# Top_Level.net
KiCad netlist of a schematic drawn in Altium Designer
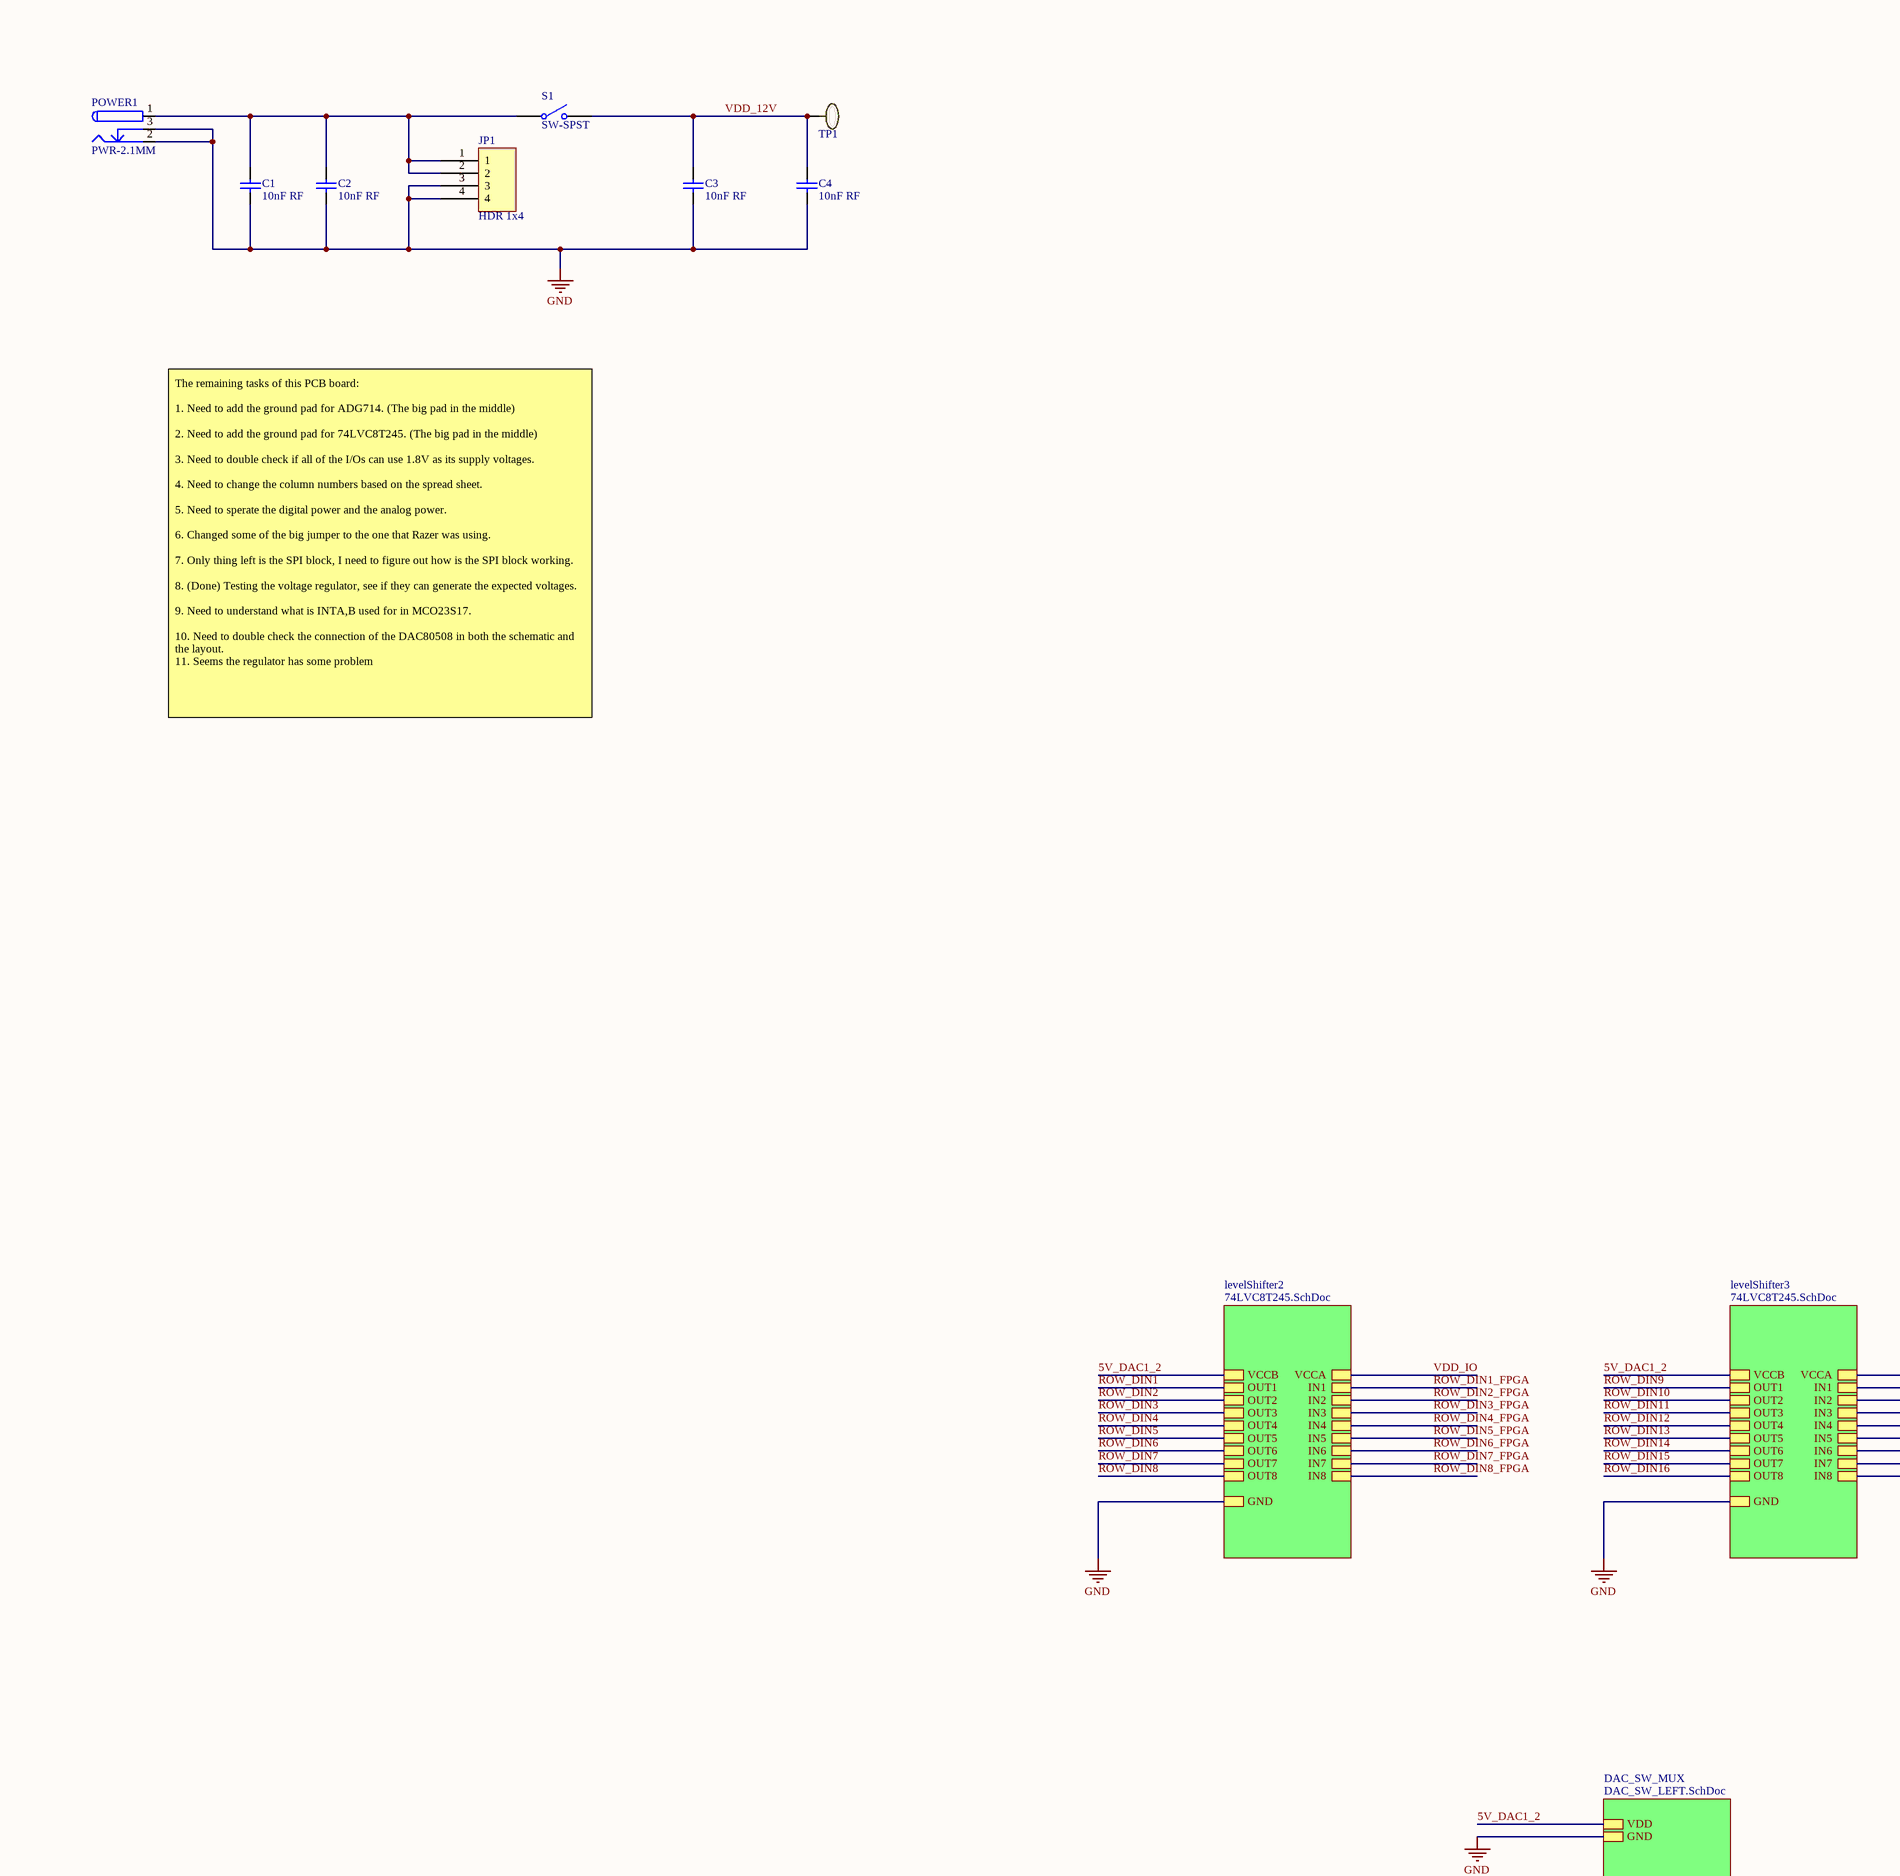
[diagram p0: Top_Level.SchDoc, top column 1 of 4]
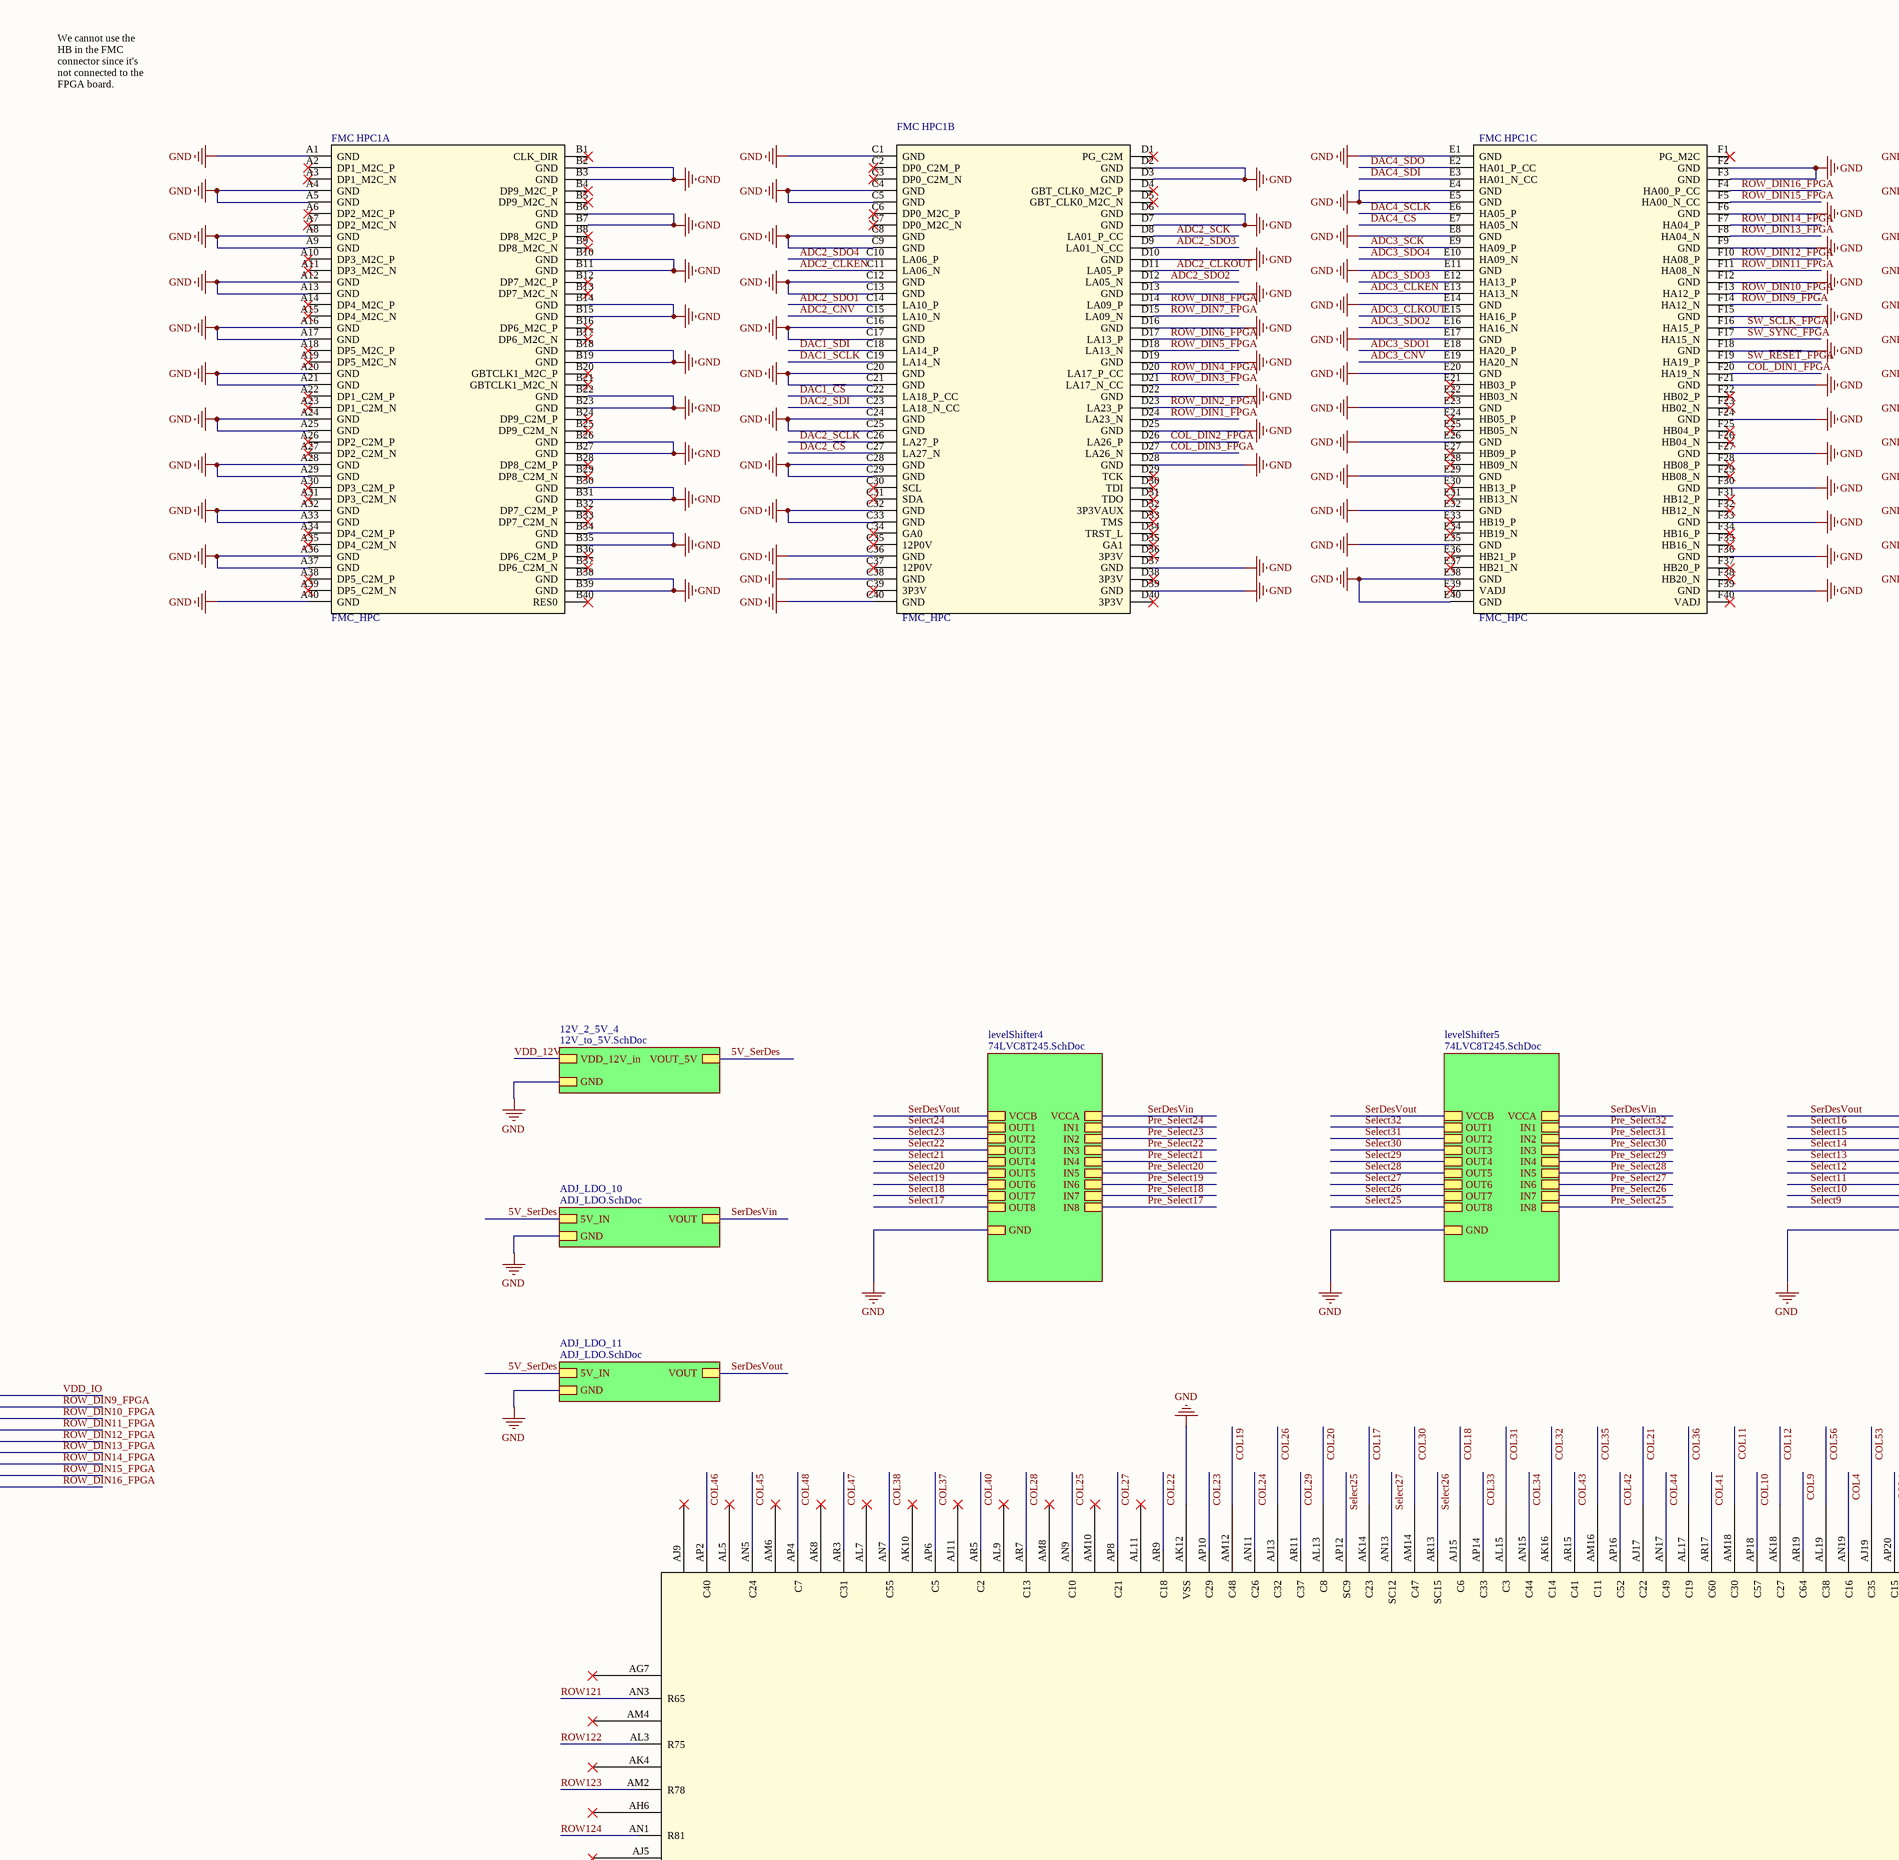
[diagram p1: Top_Level.SchDoc, top column 2 of 4]
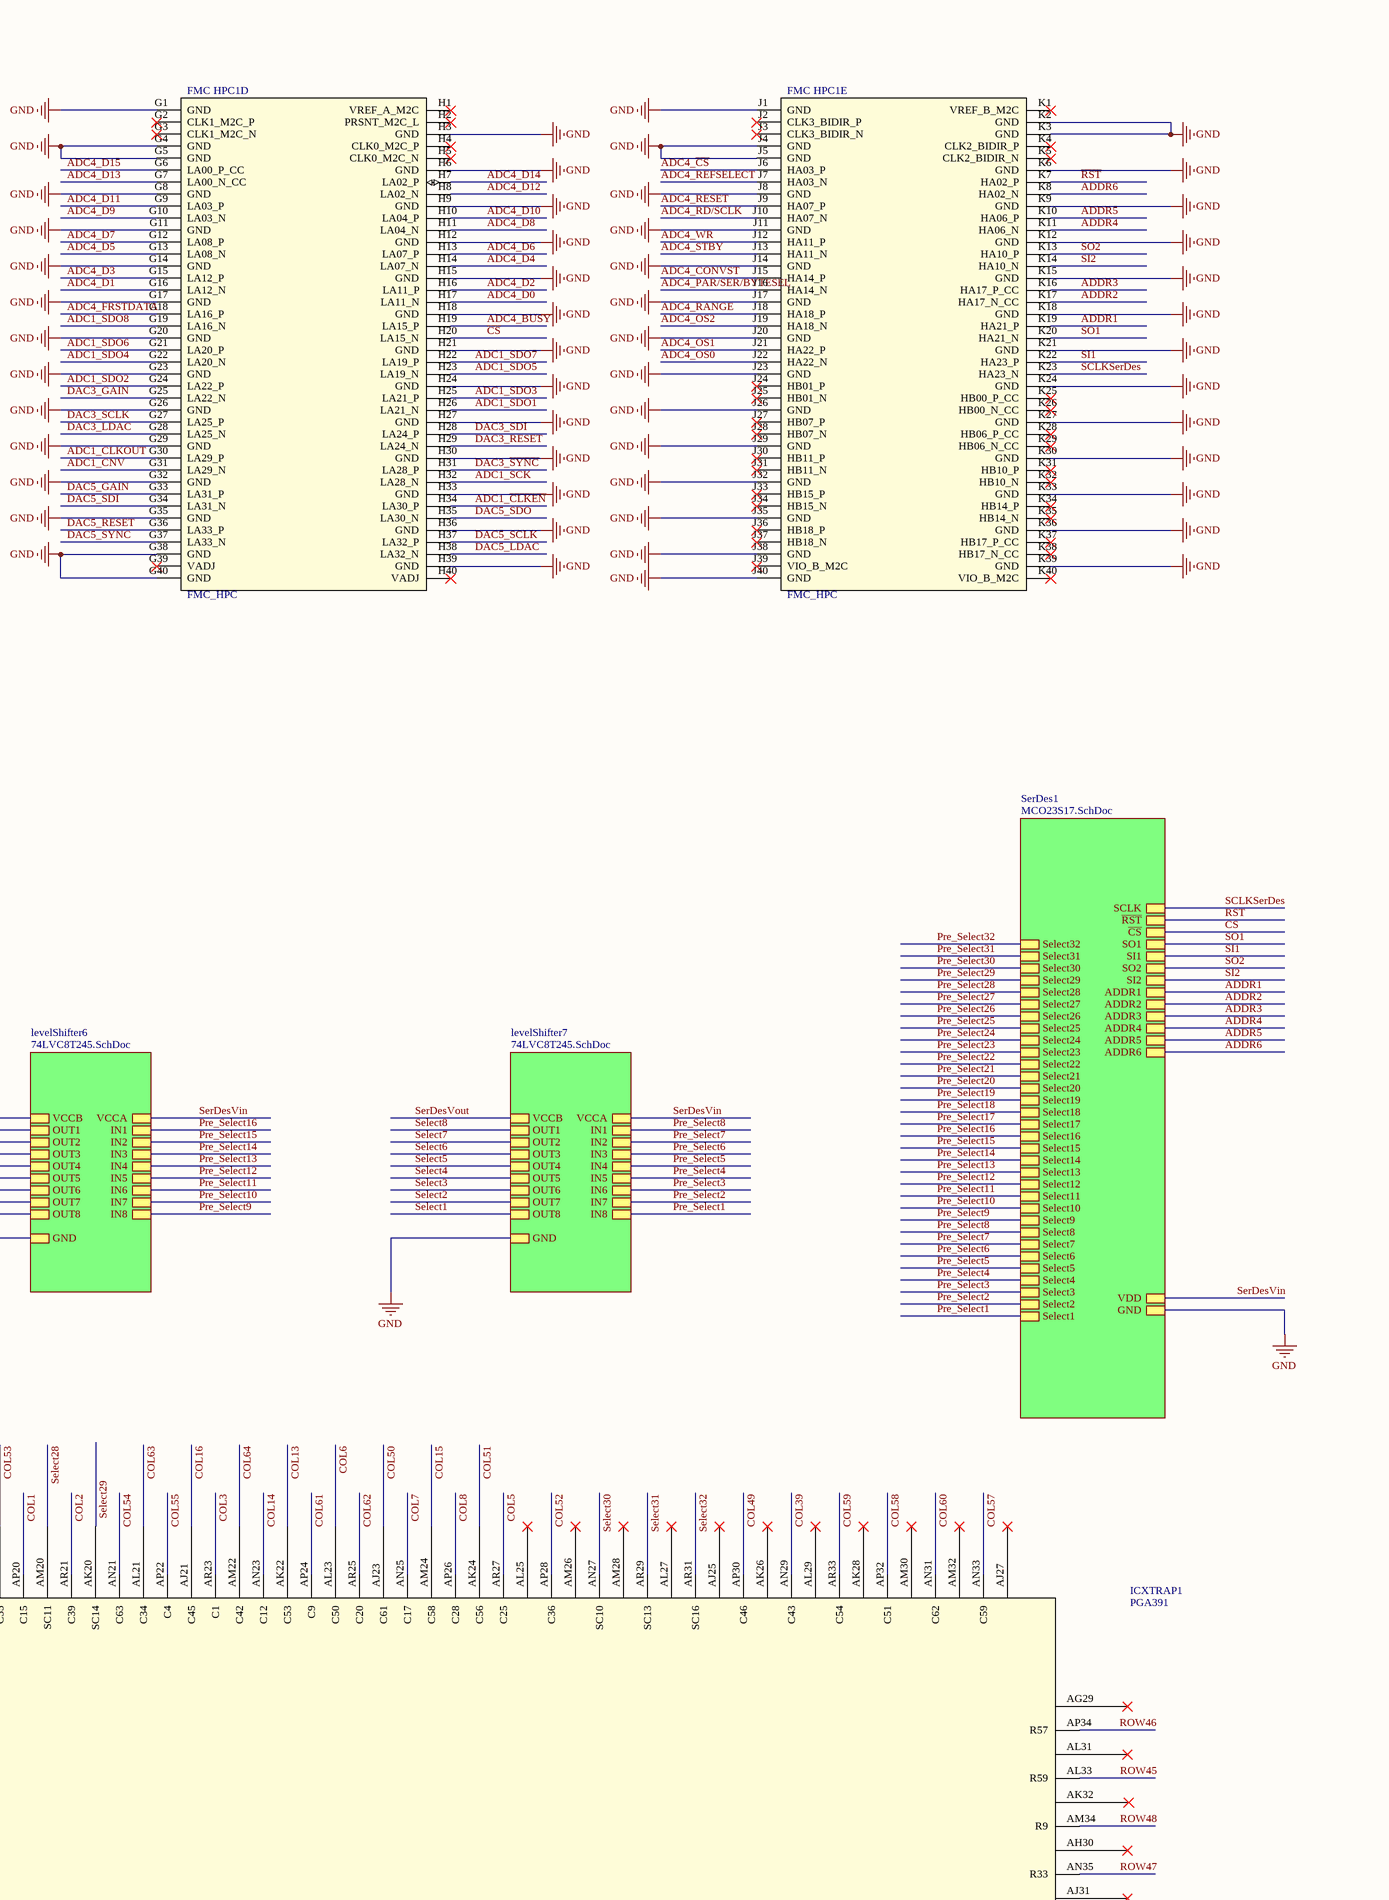
[diagram p2: Top_Level.SchDoc, top column 3 of 4]
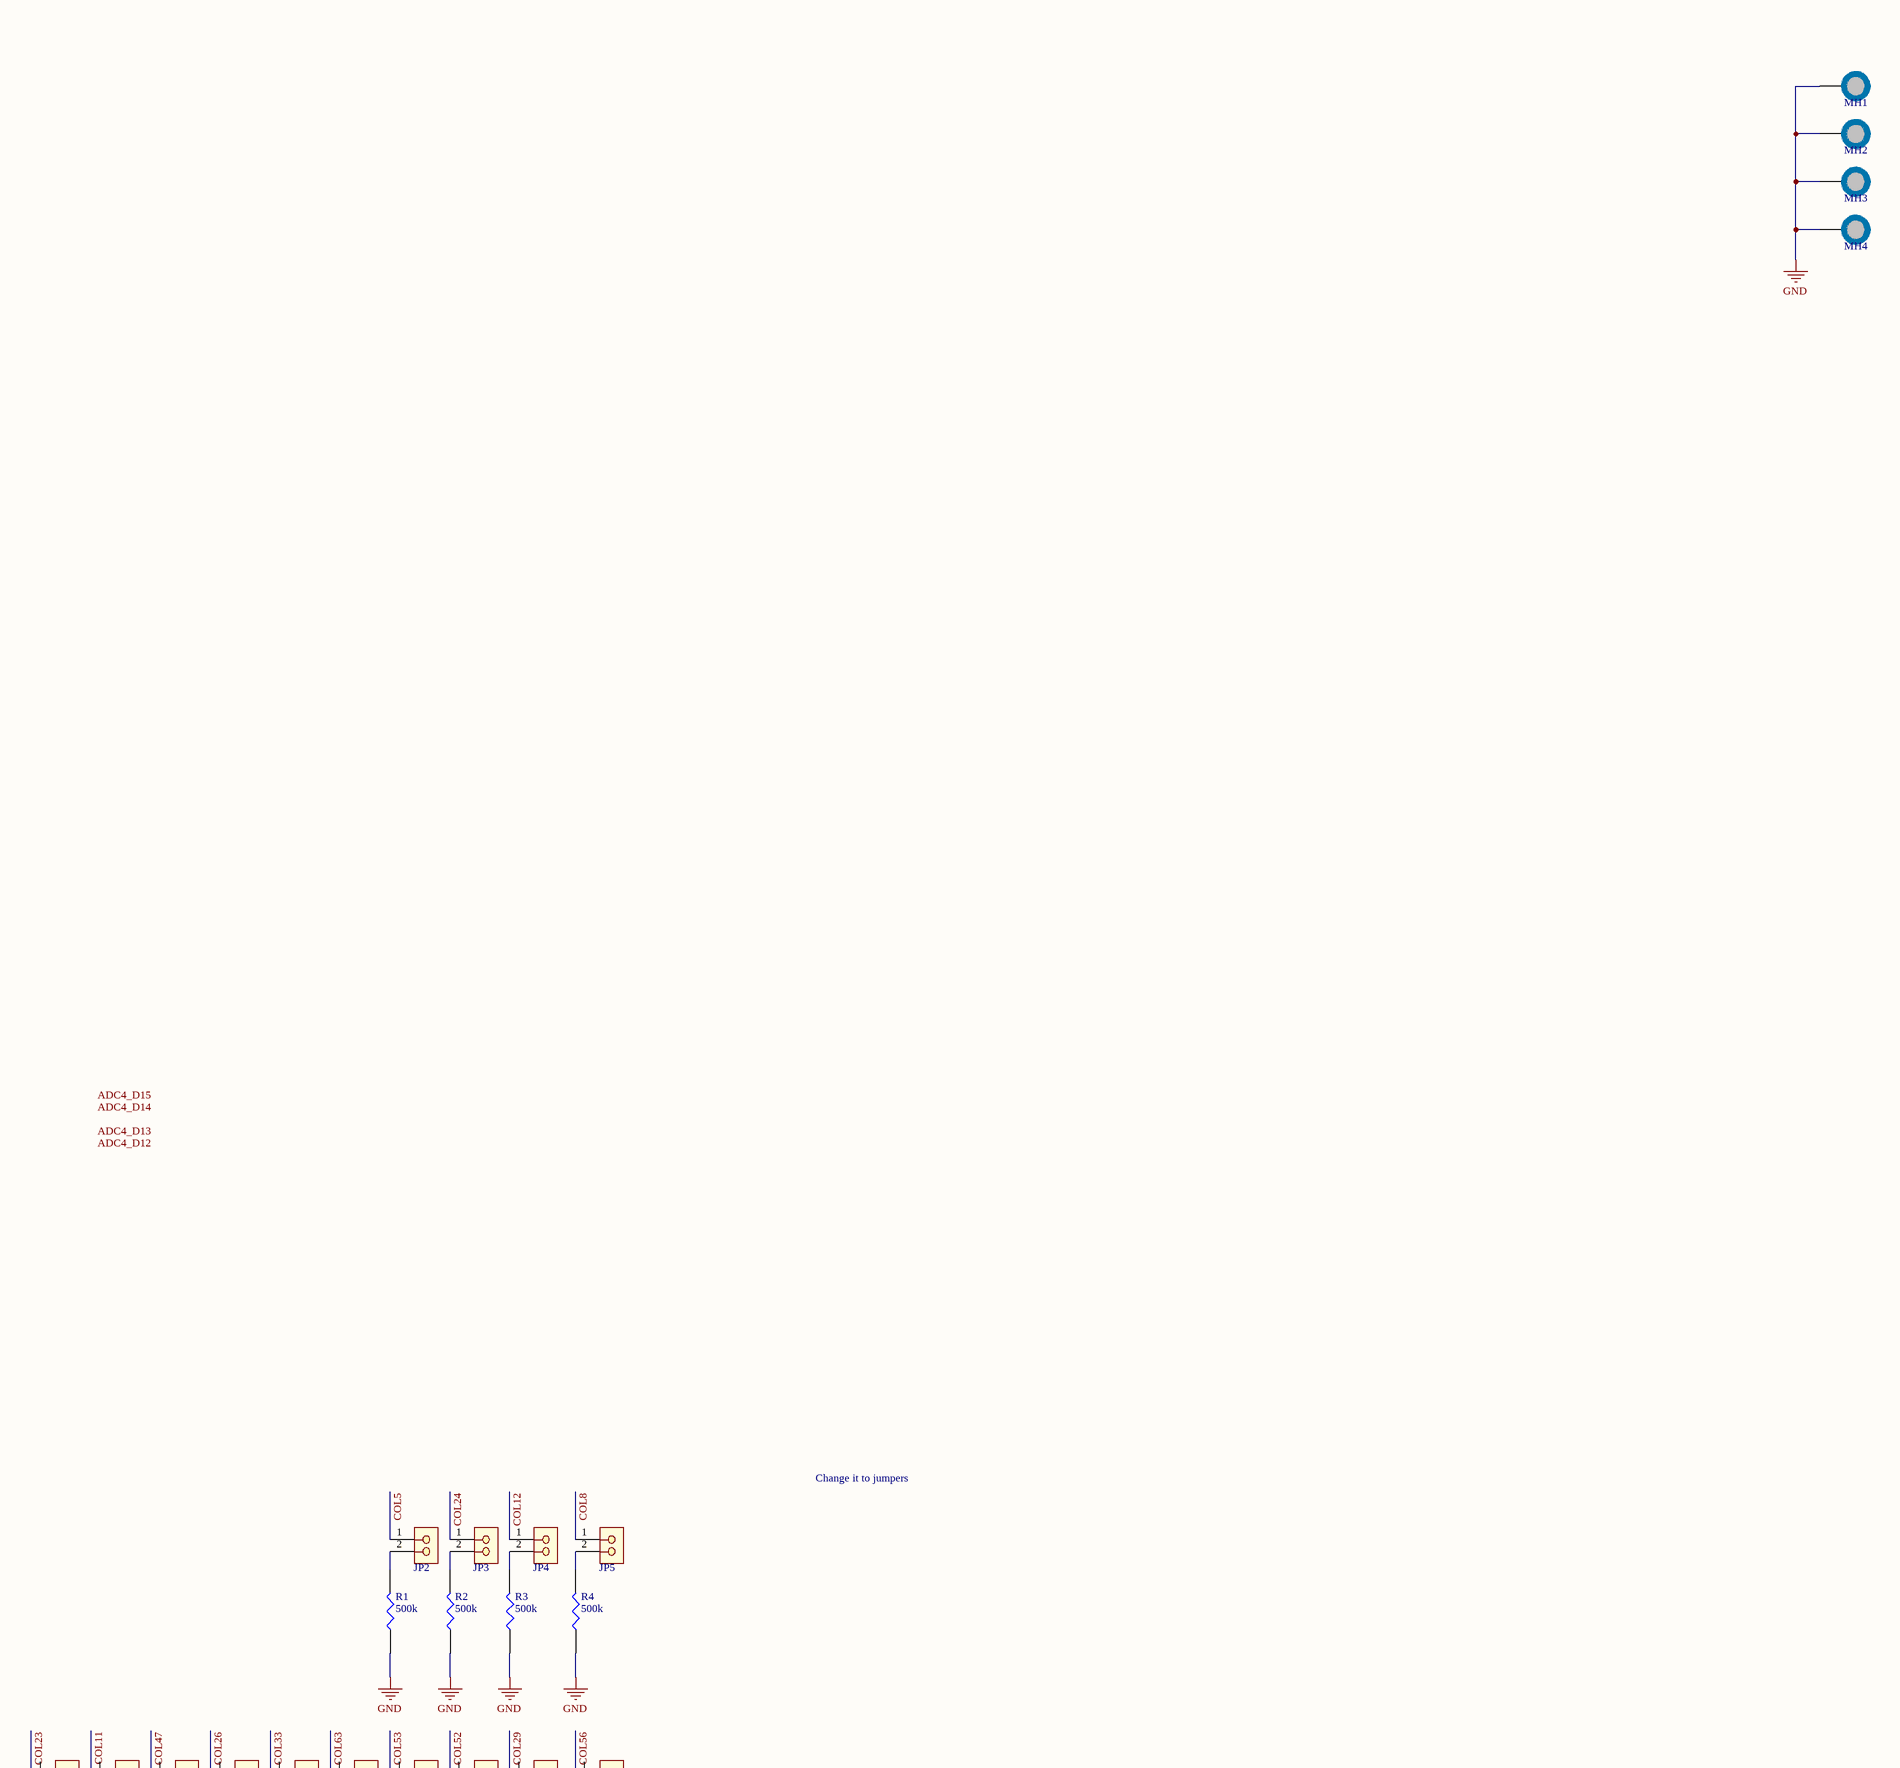
[diagram p3: Top_Level.SchDoc, top column 4 of 4]
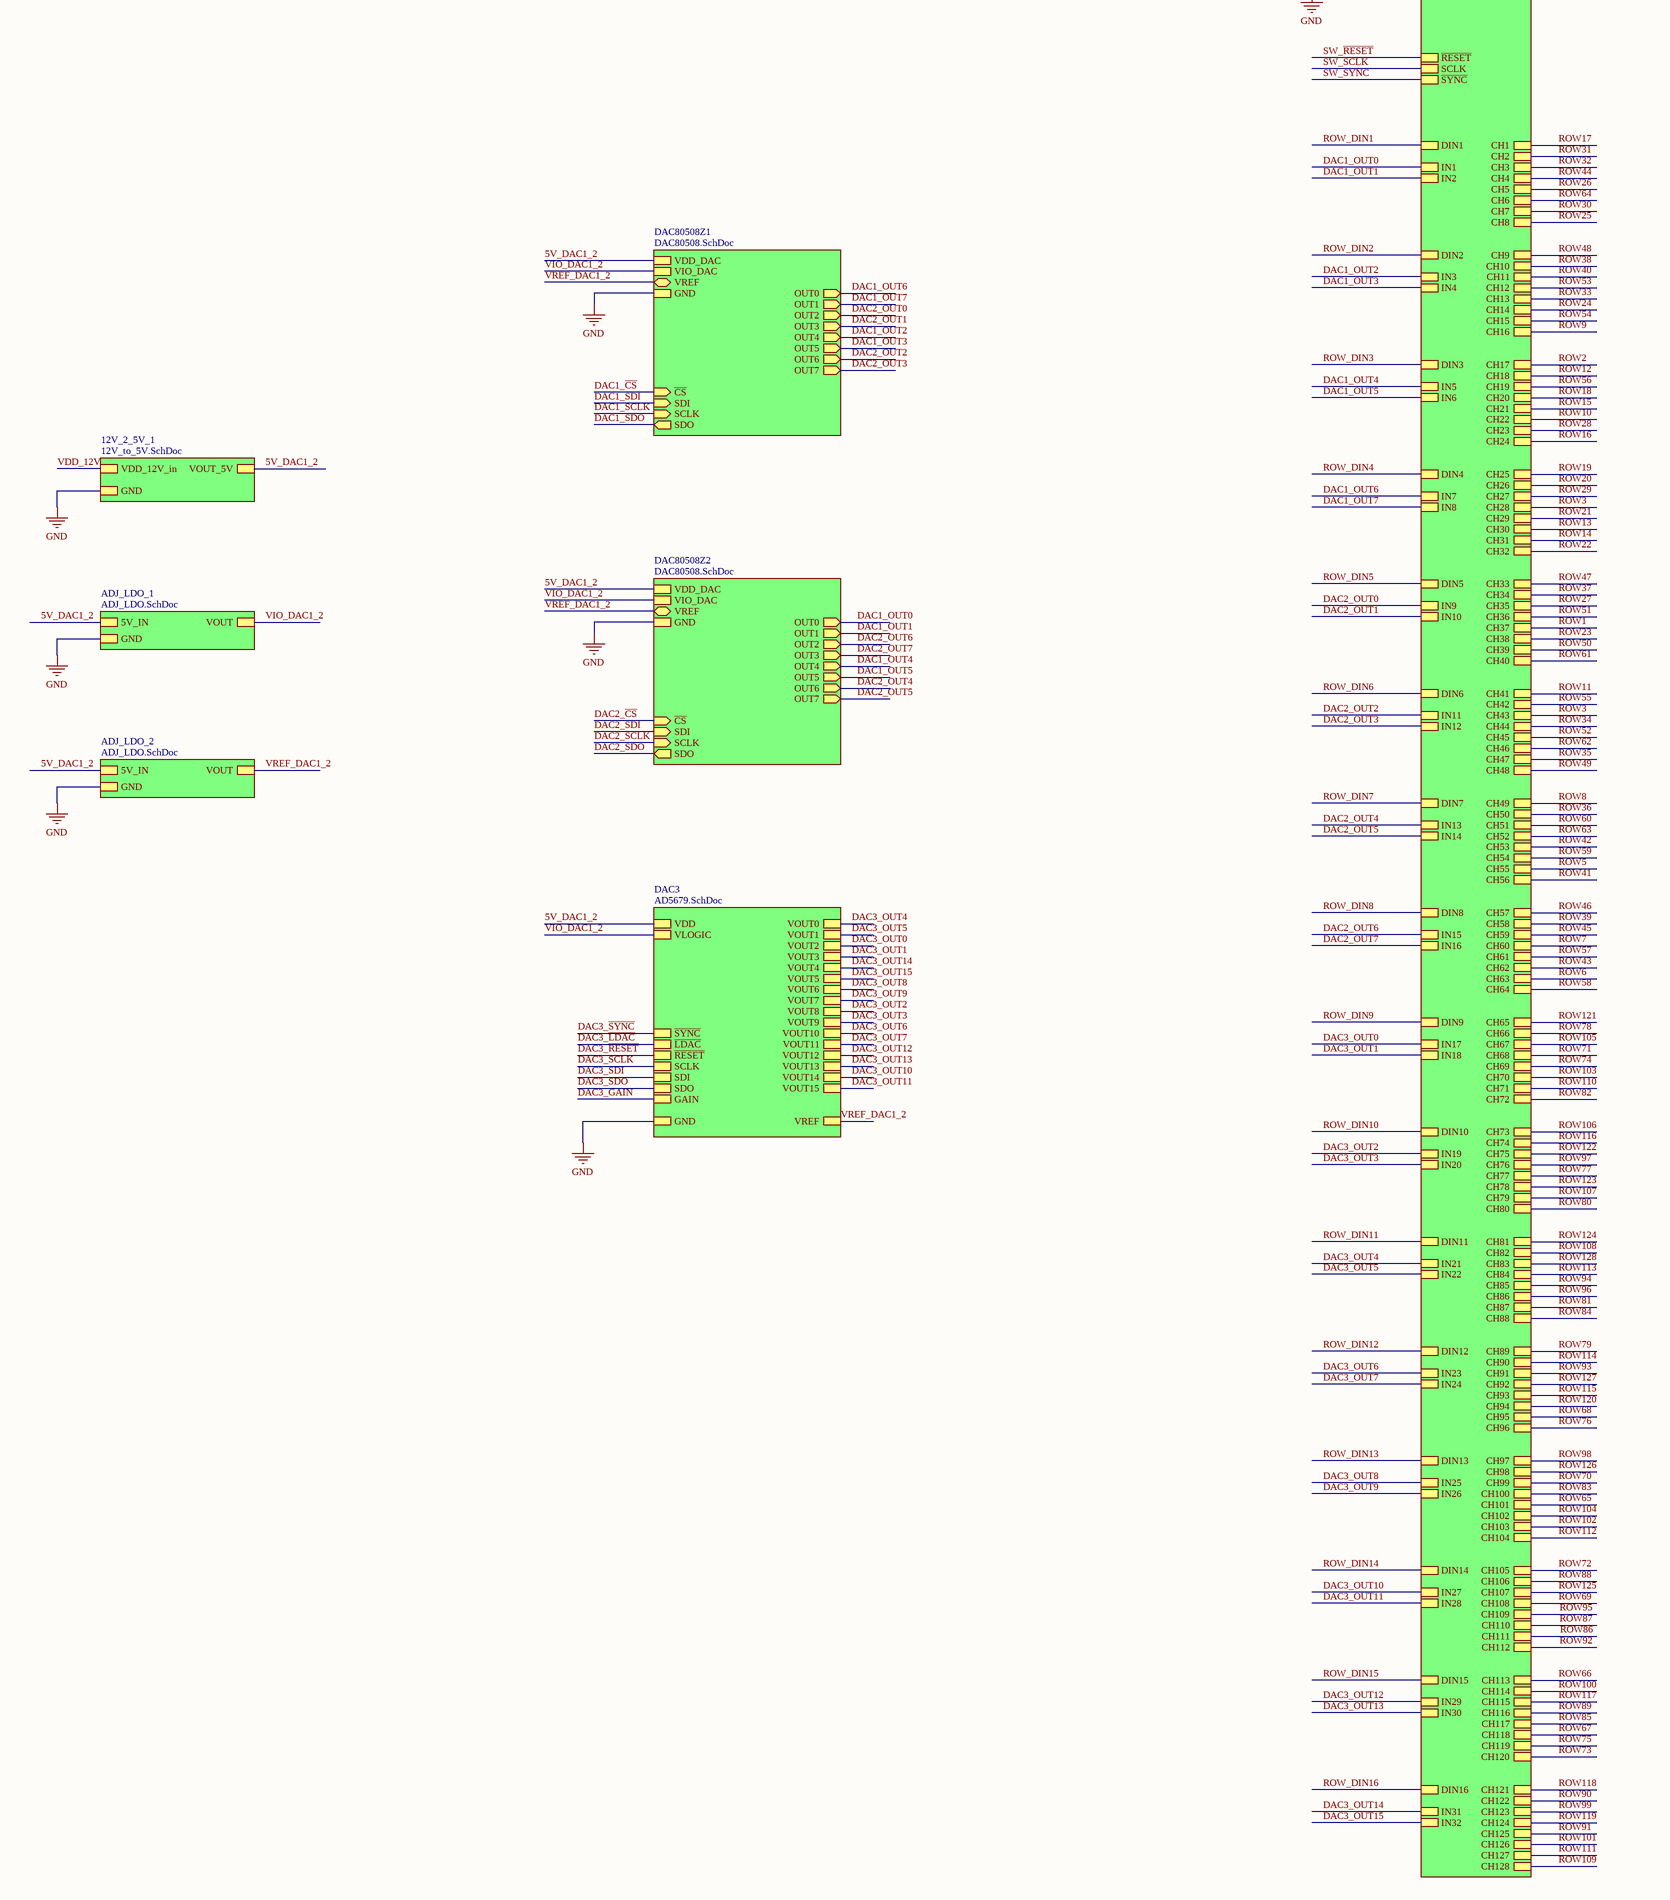
[diagram p4: Top_Level.SchDoc, centre column 1 of 4]
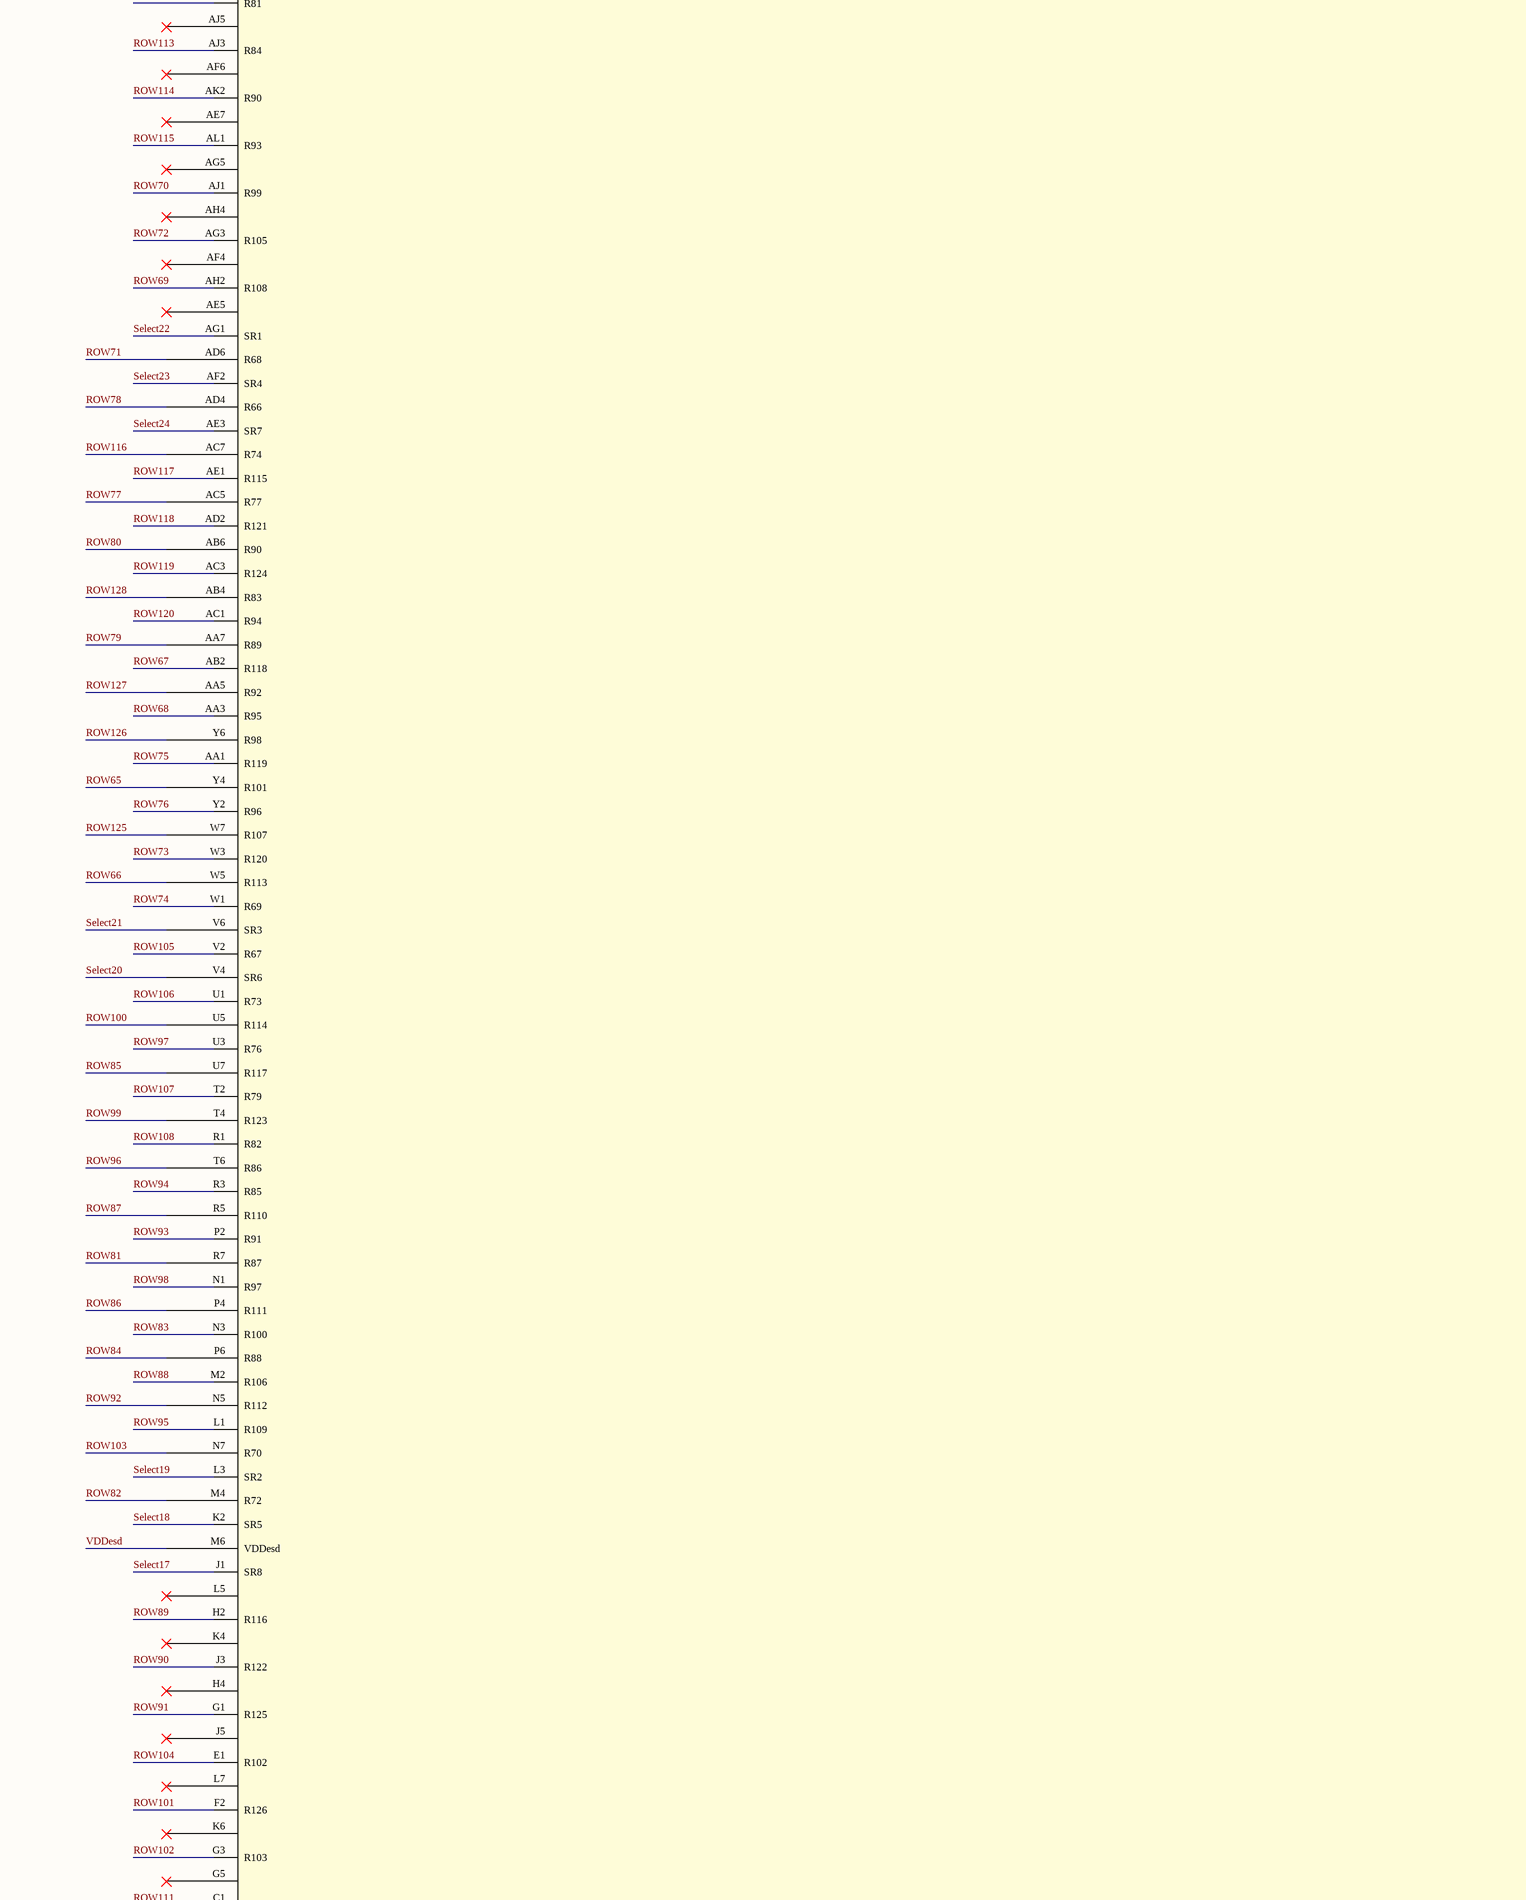
[diagram p5: Top_Level.SchDoc, centre column 2 of 4]
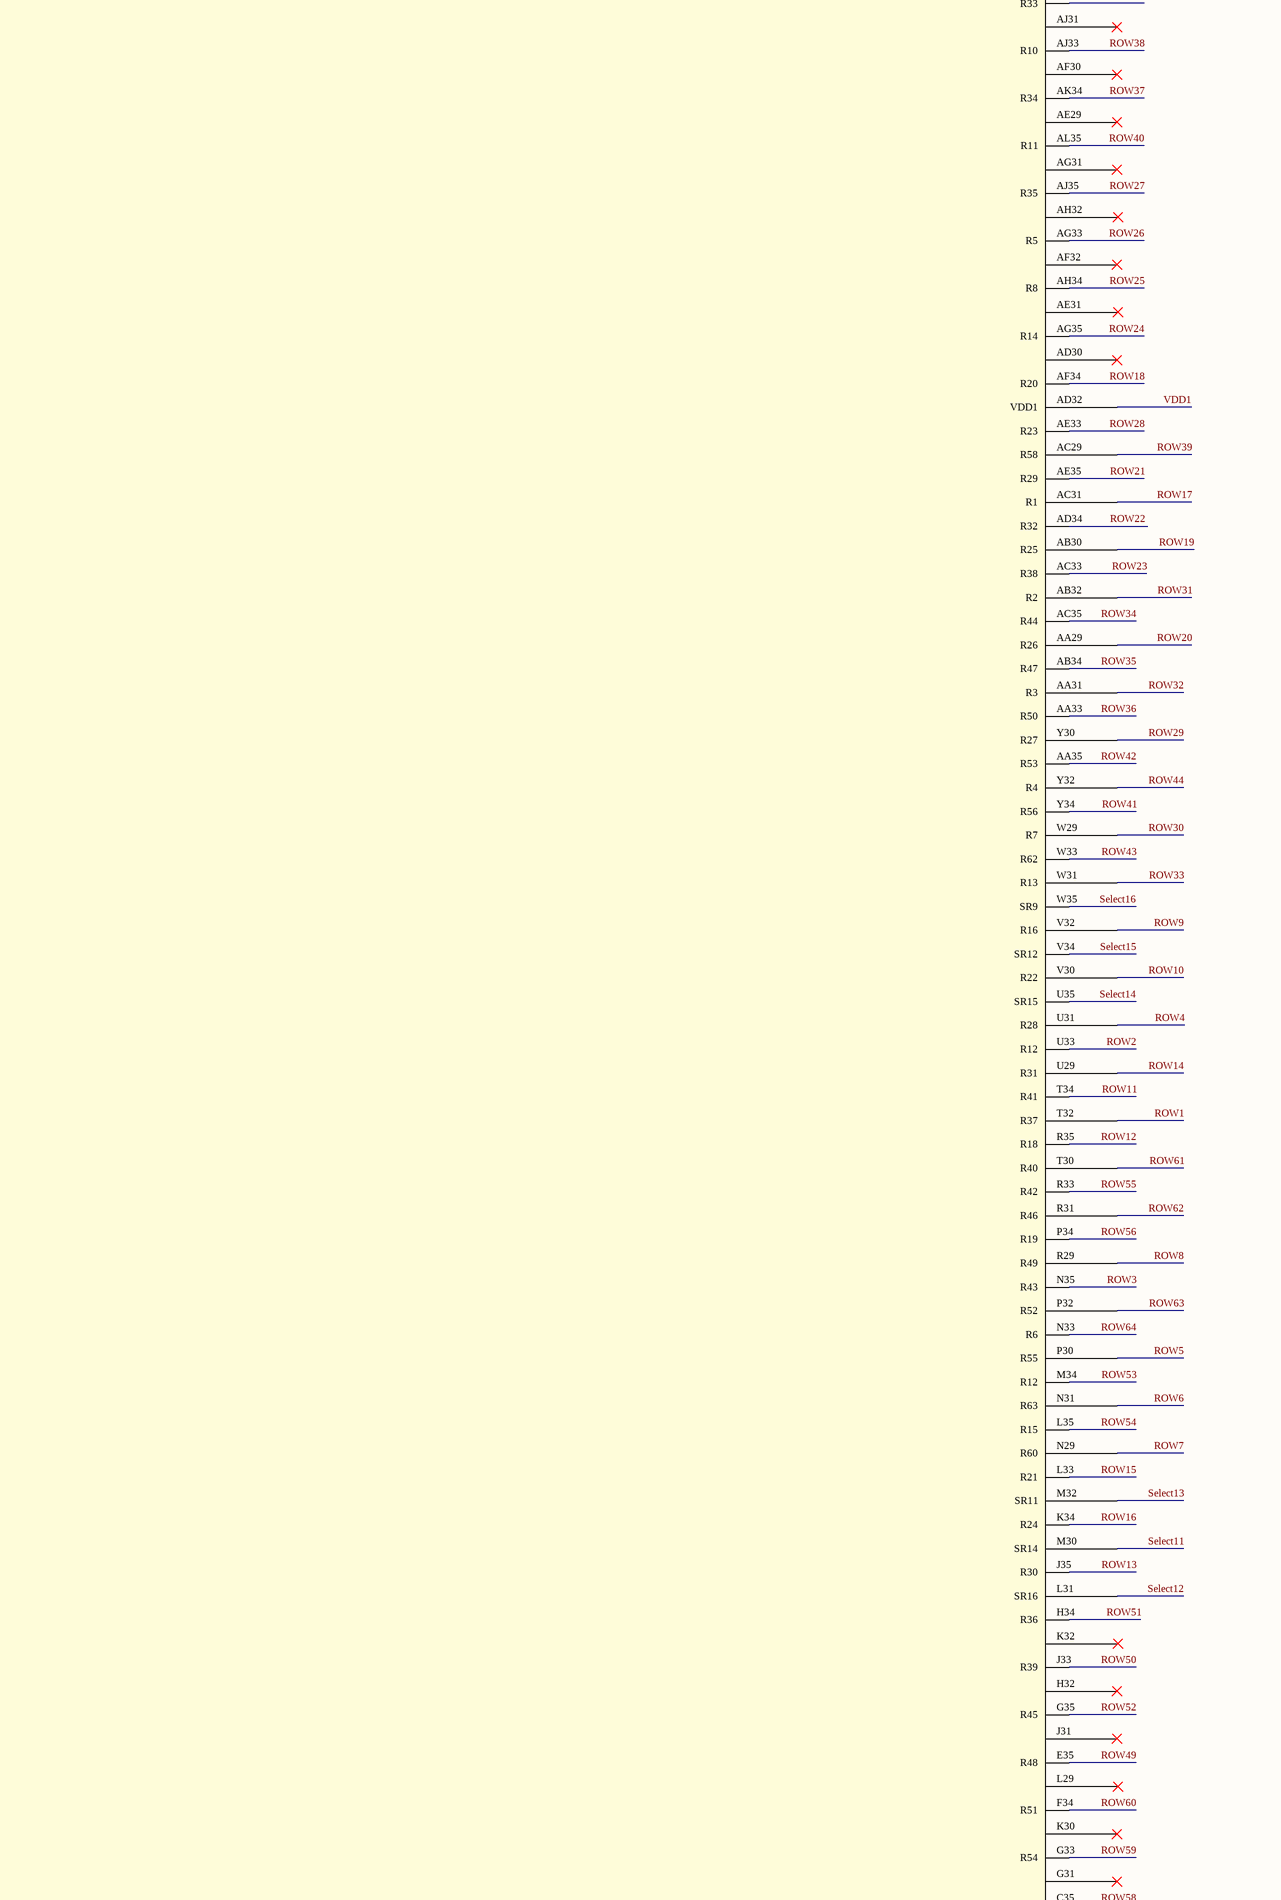
[diagram p6: Top_Level.SchDoc, centre column 3 of 4]
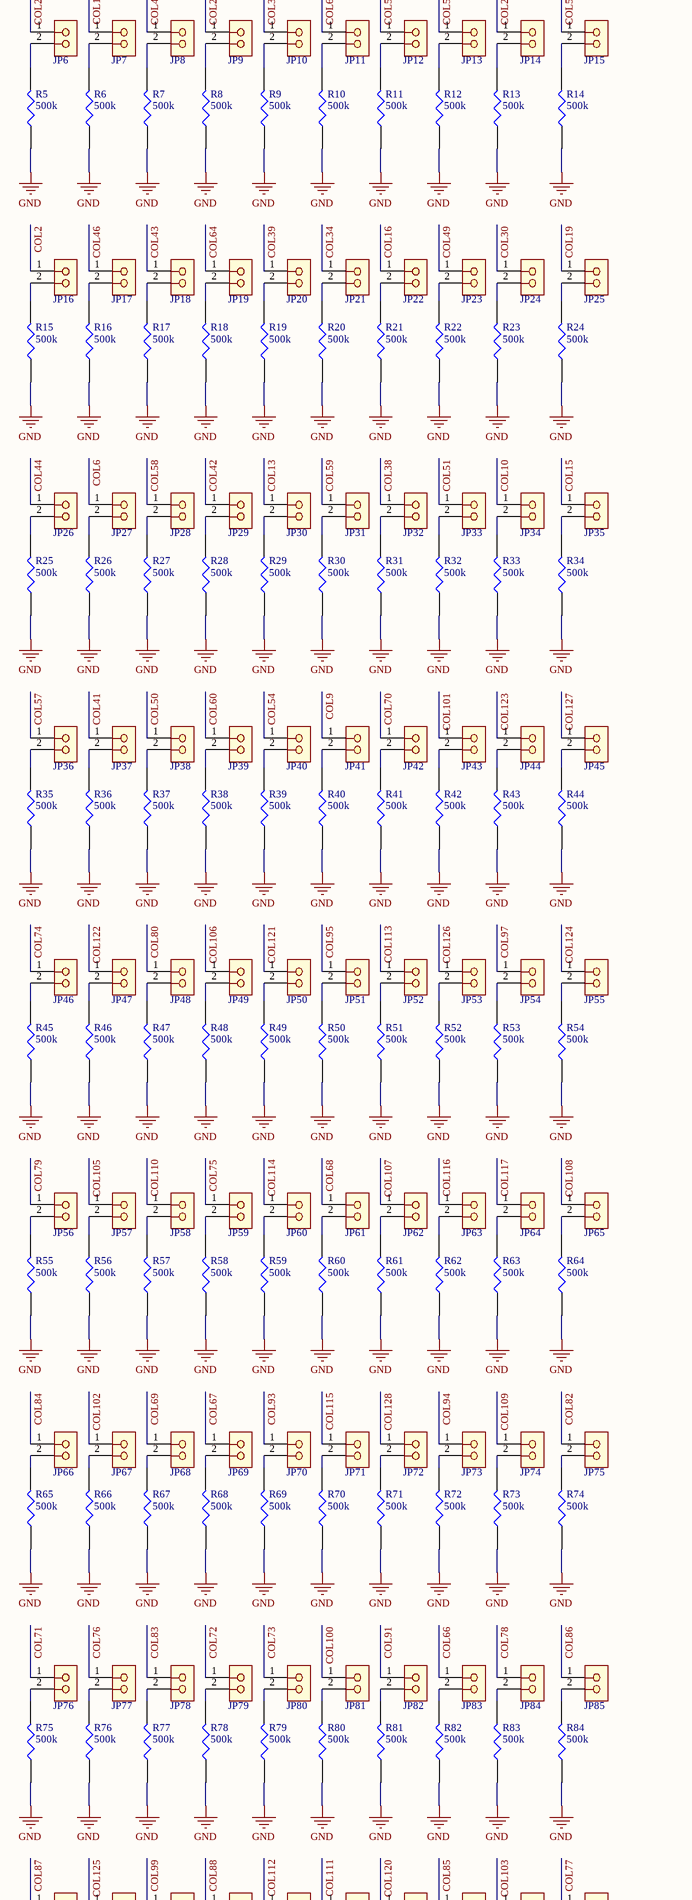
[diagram p7: Top_Level.SchDoc, centre column 4 of 4]
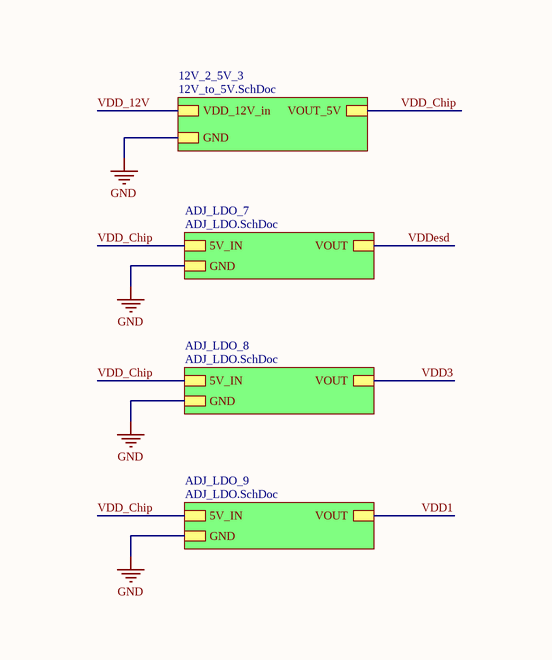
[diagram p8: Top_Level.SchDoc, bottom column 1 of 4]
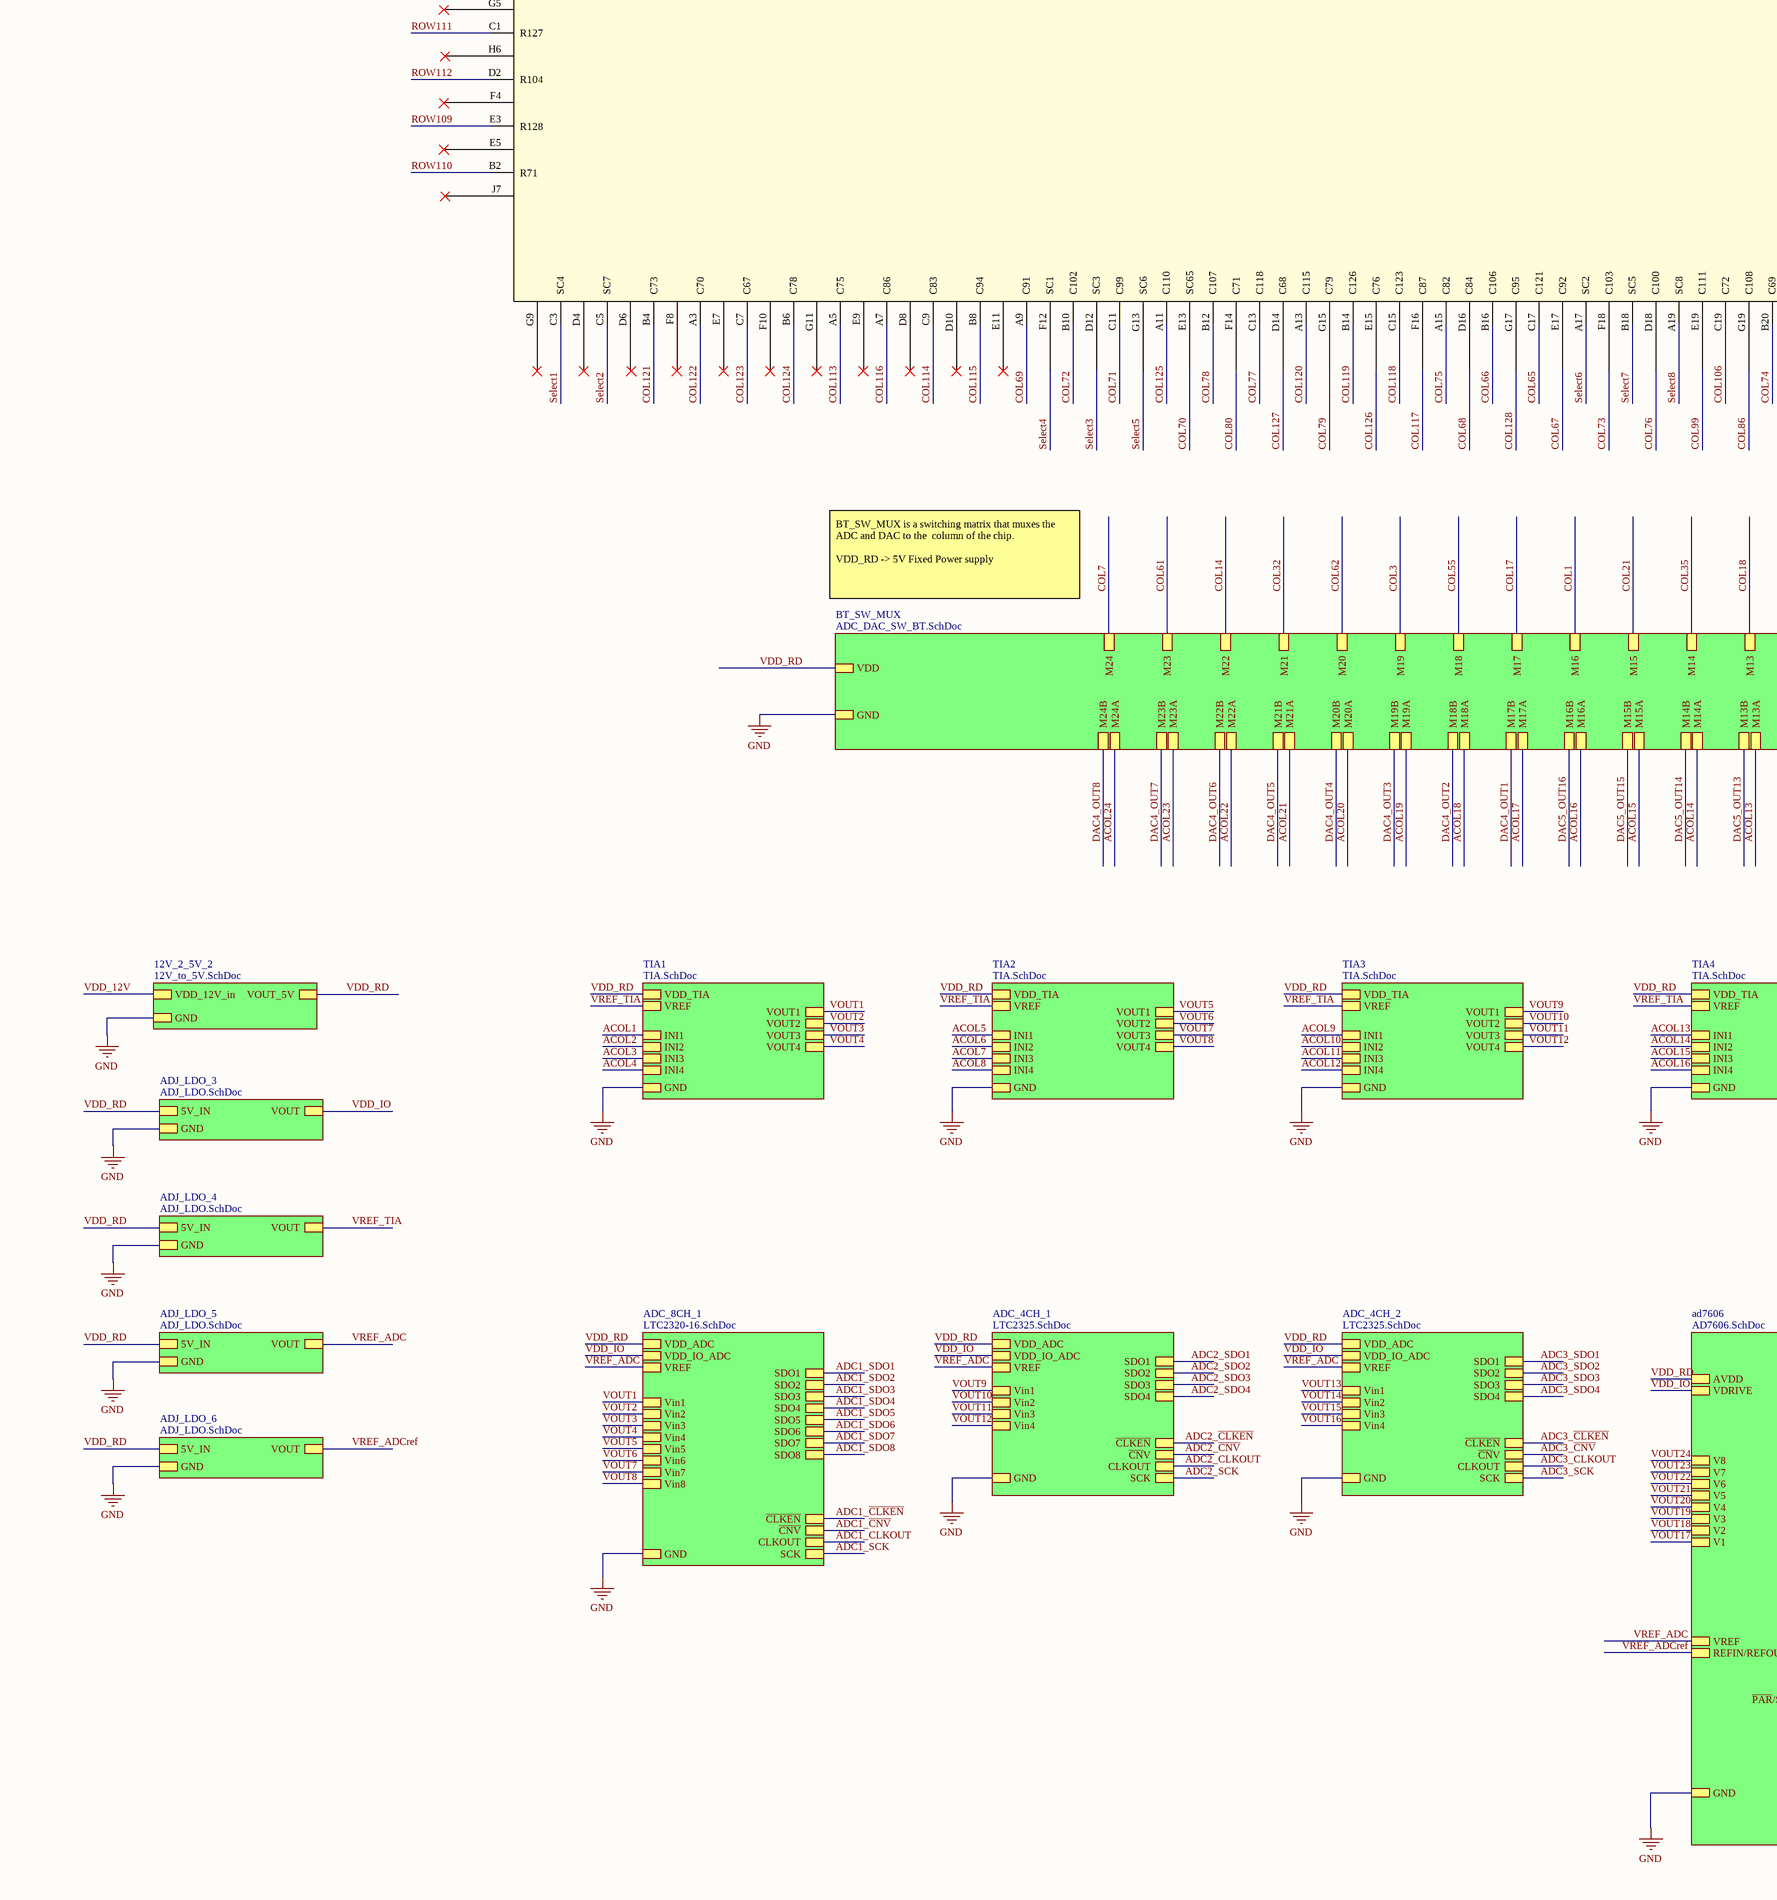
[diagram p9: Top_Level.SchDoc, bottom column 2 of 4]
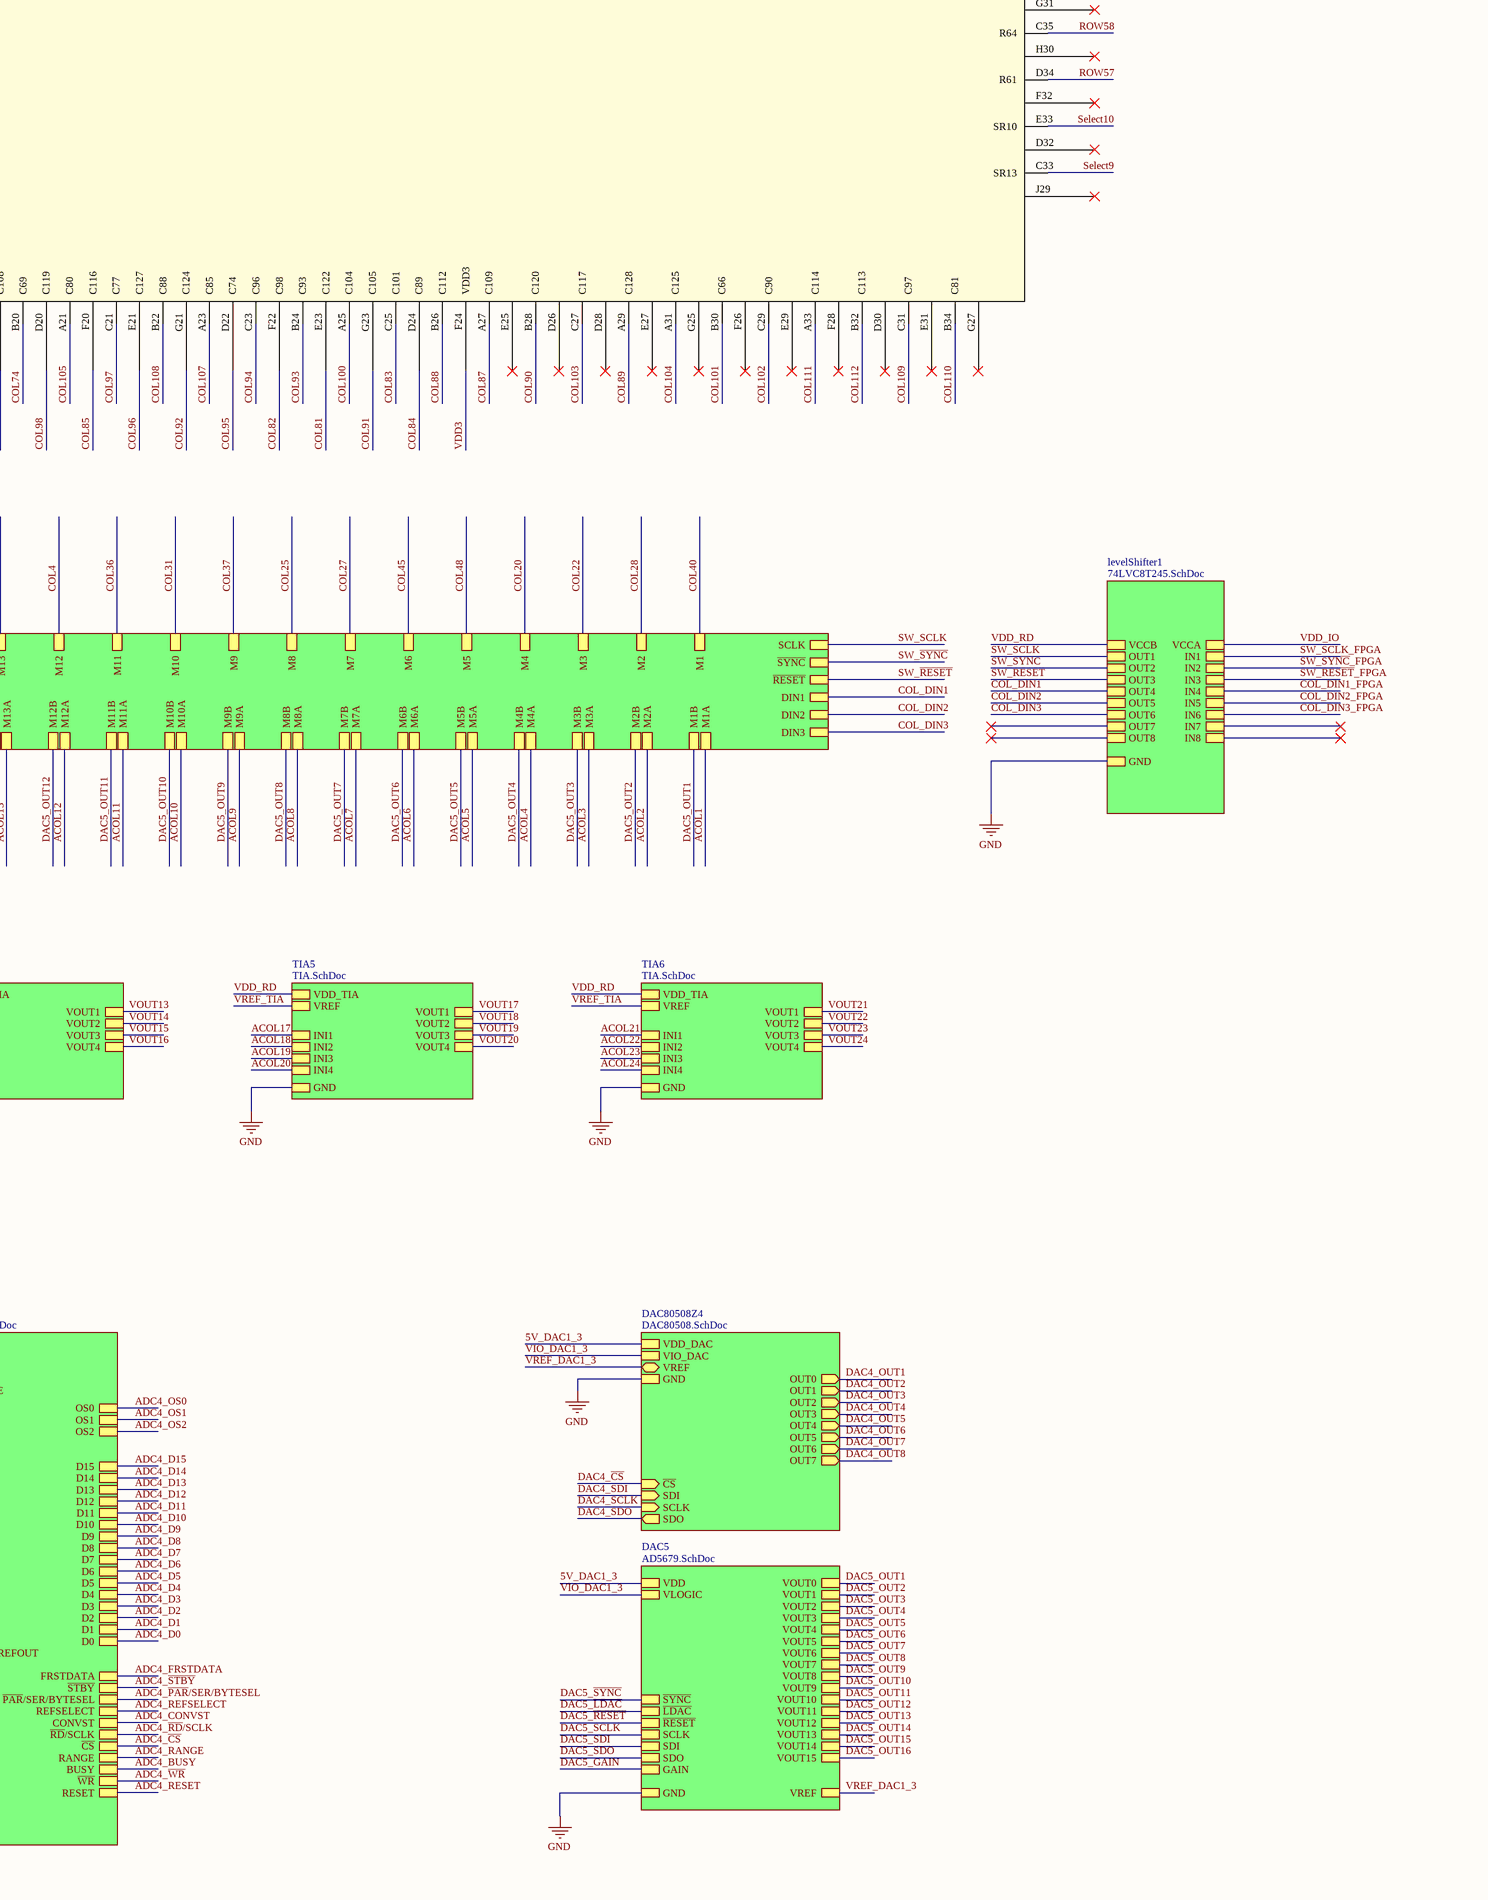
[diagram p10: Top_Level.SchDoc, bottom column 3 of 4]
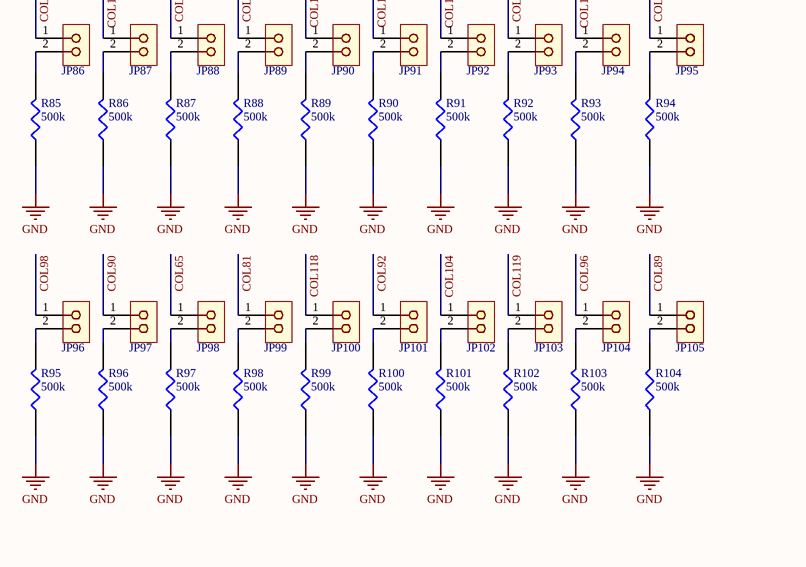
[diagram p11: Top_Level.SchDoc, bottom column 4 of 4]

(export (version "E")
  (design (tool "Eeschema 10.0.6"))
  (components
    (comp (ref "C1")
      (value "10nF RF")
      (footprint "CLS_Library:C0805")
      (description "CAP 10nF 50V RF")
      (fields
        (field (name "MANUFACTURER") "Taiyo Yuden")
        (field (name "MANUFACTURER PART NUMBER") "UMK212SD103KD-T")
      )
      (libsource (lib "CLS_Library") (part "UMK212SD103KD-T"))
    )
    (comp (ref "C2")
      (value "10nF RF")
      (footprint "CLS_Library:C0805")
      (description "CAP 10nF 50V RF")
      (fields
        (field (name "MANUFACTURER") "Taiyo Yuden")
        (field (name "MANUFACTURER PART NUMBER") "UMK212SD103KD-T")
      )
      (libsource (lib "CLS_Library") (part "UMK212SD103KD-T"))
    )
    (comp (ref "C3")
      (value "10nF RF")
      (footprint "CLS_Library:C0805")
      (description "CAP 10nF 50V RF")
      (fields
        (field (name "MANUFACTURER") "Taiyo Yuden")
        (field (name "MANUFACTURER PART NUMBER") "UMK212SD103KD-T")
      )
      (libsource (lib "CLS_Library") (part "UMK212SD103KD-T"))
    )
    (comp (ref "C4")
      (value "10nF RF")
      (footprint "CLS_Library:C0805")
      (description "CAP 10nF 50V RF")
      (fields
        (field (name "MANUFACTURER") "Taiyo Yuden")
        (field (name "MANUFACTURER PART NUMBER") "UMK212SD103KD-T")
      )
      (libsource (lib "CLS_Library") (part "UMK212SD103KD-T"))
    )
    (comp (ref "FMC HPC1")
      (value "FMC_HPC")
      (footprint "FMC_HPC")
      (libsource (lib "CLS_Library") (part "FMC_HPC"))
    )
    (comp (ref "ICXTRAP1")
      (value "PGA391")
      (footprint "PGA391")
      (description "ICXTRAP1")
      (libsource (lib "ICXTRAP1") (part "PGA391"))
    )
    (comp (ref "JP1")
      (value "HDR 1x4")
      (footprint "CLS_Library:Hdr_1x4_2.54mm")
      (description "B.II CONN HEADER 4POS .100 STR 15AU")
      (fields
        (field (name "MANUFACTURER") "Amphenol FCI")
        (field (name "MANUFACTURER PART NUMBER") "68000-204HLF")
      )
      (libsource (lib "CLS_Library") (part "68000-204HLF"))
    )
    (comp (ref "JP2")
      (value "01x02")
      (footprint "01x02_0.1in_th_straight_b_nom")
      (description "01X02 generic terminal connector")
      (libsource (lib "Chip1_TestBoard") (part "01x02"))
    )
    (comp (ref "JP3")
      (value "01x02")
      (footprint "01x02_0.1in_th_straight_b_nom")
      (description "01X02 generic terminal connector")
      (libsource (lib "Chip1_TestBoard") (part "01x02"))
    )
    (comp (ref "JP4")
      (value "01x02")
      (footprint "01x02_0.1in_th_straight_b_nom")
      (description "01X02 generic terminal connector")
      (libsource (lib "Chip1_TestBoard") (part "01x02"))
    )
    (comp (ref "JP5")
      (value "01x02")
      (footprint "01x02_0.1in_th_straight_b_nom")
      (description "01X02 generic terminal connector")
      (libsource (lib "Chip1_TestBoard") (part "01x02"))
    )
    (comp (ref "JP6")
      (value "01x02")
      (footprint "01x02_0.1in_th_straight_b_nom")
      (description "01X02 generic terminal connector")
      (libsource (lib "Chip1_TestBoard") (part "01x02"))
    )
    (comp (ref "JP7")
      (value "01x02")
      (footprint "01x02_0.1in_th_straight_b_nom")
      (description "01X02 generic terminal connector")
      (libsource (lib "Chip1_TestBoard") (part "01x02"))
    )
    (comp (ref "JP8")
      (value "01x02")
      (footprint "01x02_0.1in_th_straight_b_nom")
      (description "01X02 generic terminal connector")
      (libsource (lib "Chip1_TestBoard") (part "01x02"))
    )
    (comp (ref "JP9")
      (value "01x02")
      (footprint "01x02_0.1in_th_straight_b_nom")
      (description "01X02 generic terminal connector")
      (libsource (lib "Chip1_TestBoard") (part "01x02"))
    )
    (comp (ref "JP10")
      (value "01x02")
      (footprint "01x02_0.1in_th_straight_b_nom")
      (description "01X02 generic terminal connector")
      (libsource (lib "Chip1_TestBoard") (part "01x02"))
    )
    (comp (ref "JP11")
      (value "01x02")
      (footprint "01x02_0.1in_th_straight_b_nom")
      (description "01X02 generic terminal connector")
      (libsource (lib "Chip1_TestBoard") (part "01x02"))
    )
    (comp (ref "JP12")
      (value "01x02")
      (footprint "01x02_0.1in_th_straight_b_nom")
      (description "01X02 generic terminal connector")
      (libsource (lib "Chip1_TestBoard") (part "01x02"))
    )
    (comp (ref "JP13")
      (value "01x02")
      (footprint "01x02_0.1in_th_straight_b_nom")
      (description "01X02 generic terminal connector")
      (libsource (lib "Chip1_TestBoard") (part "01x02"))
    )
    (comp (ref "JP14")
      (value "01x02")
      (footprint "01x02_0.1in_th_straight_b_nom")
      (description "01X02 generic terminal connector")
      (libsource (lib "Chip1_TestBoard") (part "01x02"))
    )
    (comp (ref "JP15")
      (value "01x02")
      (footprint "01x02_0.1in_th_straight_b_nom")
      (description "01X02 generic terminal connector")
      (libsource (lib "Chip1_TestBoard") (part "01x02"))
    )
    (comp (ref "JP16")
      (value "01x02")
      (footprint "01x02_0.1in_th_straight_b_nom")
      (description "01X02 generic terminal connector")
      (libsource (lib "Chip1_TestBoard") (part "01x02"))
    )
    (comp (ref "JP17")
      (value "01x02")
      (footprint "01x02_0.1in_th_straight_b_nom")
      (description "01X02 generic terminal connector")
      (libsource (lib "Chip1_TestBoard") (part "01x02"))
    )
    (comp (ref "JP18")
      (value "01x02")
      (footprint "01x02_0.1in_th_straight_b_nom")
      (description "01X02 generic terminal connector")
      (libsource (lib "Chip1_TestBoard") (part "01x02"))
    )
    (comp (ref "JP19")
      (value "01x02")
      (footprint "01x02_0.1in_th_straight_b_nom")
      (description "01X02 generic terminal connector")
      (libsource (lib "Chip1_TestBoard") (part "01x02"))
    )
    (comp (ref "JP20")
      (value "01x02")
      (footprint "01x02_0.1in_th_straight_b_nom")
      (description "01X02 generic terminal connector")
      (libsource (lib "Chip1_TestBoard") (part "01x02"))
    )
    (comp (ref "JP21")
      (value "01x02")
      (footprint "01x02_0.1in_th_straight_b_nom")
      (description "01X02 generic terminal connector")
      (libsource (lib "Chip1_TestBoard") (part "01x02"))
    )
    (comp (ref "JP22")
      (value "01x02")
      (footprint "01x02_0.1in_th_straight_b_nom")
      (description "01X02 generic terminal connector")
      (libsource (lib "Chip1_TestBoard") (part "01x02"))
    )
    (comp (ref "JP23")
      (value "01x02")
      (footprint "01x02_0.1in_th_straight_b_nom")
      (description "01X02 generic terminal connector")
      (libsource (lib "Chip1_TestBoard") (part "01x02"))
    )
    (comp (ref "JP24")
      (value "01x02")
      (footprint "01x02_0.1in_th_straight_b_nom")
      (description "01X02 generic terminal connector")
      (libsource (lib "Chip1_TestBoard") (part "01x02"))
    )
    (comp (ref "JP25")
      (value "01x02")
      (footprint "01x02_0.1in_th_straight_b_nom")
      (description "01X02 generic terminal connector")
      (libsource (lib "Chip1_TestBoard") (part "01x02"))
    )
    (comp (ref "JP26")
      (value "01x02")
      (footprint "01x02_0.1in_th_straight_b_nom")
      (description "01X02 generic terminal connector")
      (libsource (lib "Chip1_TestBoard") (part "01x02"))
    )
    (comp (ref "JP27")
      (value "01x02")
      (footprint "01x02_0.1in_th_straight_b_nom")
      (description "01X02 generic terminal connector")
      (libsource (lib "Chip1_TestBoard") (part "01x02"))
    )
    (comp (ref "JP28")
      (value "01x02")
      (footprint "01x02_0.1in_th_straight_b_nom")
      (description "01X02 generic terminal connector")
      (libsource (lib "Chip1_TestBoard") (part "01x02"))
    )
    (comp (ref "JP29")
      (value "01x02")
      (footprint "01x02_0.1in_th_straight_b_nom")
      (description "01X02 generic terminal connector")
      (libsource (lib "Chip1_TestBoard") (part "01x02"))
    )
    (comp (ref "JP30")
      (value "01x02")
      (footprint "01x02_0.1in_th_straight_b_nom")
      (description "01X02 generic terminal connector")
      (libsource (lib "Chip1_TestBoard") (part "01x02"))
    )
    (comp (ref "JP31")
      (value "01x02")
      (footprint "01x02_0.1in_th_straight_b_nom")
      (description "01X02 generic terminal connector")
      (libsource (lib "Chip1_TestBoard") (part "01x02"))
    )
    (comp (ref "JP32")
      (value "01x02")
      (footprint "01x02_0.1in_th_straight_b_nom")
      (description "01X02 generic terminal connector")
      (libsource (lib "Chip1_TestBoard") (part "01x02"))
    )
    (comp (ref "JP33")
      (value "01x02")
      (footprint "01x02_0.1in_th_straight_b_nom")
      (description "01X02 generic terminal connector")
      (libsource (lib "Chip1_TestBoard") (part "01x02"))
    )
    (comp (ref "JP34")
      (value "01x02")
      (footprint "01x02_0.1in_th_straight_b_nom")
      (description "01X02 generic terminal connector")
      (libsource (lib "Chip1_TestBoard") (part "01x02"))
    )
    (comp (ref "JP35")
      (value "01x02")
      (footprint "01x02_0.1in_th_straight_b_nom")
      (description "01X02 generic terminal connector")
      (libsource (lib "Chip1_TestBoard") (part "01x02"))
    )
    (comp (ref "JP36")
      (value "01x02")
      (footprint "01x02_0.1in_th_straight_b_nom")
      (description "01X02 generic terminal connector")
      (libsource (lib "Chip1_TestBoard") (part "01x02"))
    )
    (comp (ref "JP37")
      (value "01x02")
      (footprint "01x02_0.1in_th_straight_b_nom")
      (description "01X02 generic terminal connector")
      (libsource (lib "Chip1_TestBoard") (part "01x02"))
    )
    (comp (ref "JP38")
      (value "01x02")
      (footprint "01x02_0.1in_th_straight_b_nom")
      (description "01X02 generic terminal connector")
      (libsource (lib "Chip1_TestBoard") (part "01x02"))
    )
    (comp (ref "JP39")
      (value "01x02")
      (footprint "01x02_0.1in_th_straight_b_nom")
      (description "01X02 generic terminal connector")
      (libsource (lib "Chip1_TestBoard") (part "01x02"))
    )
    (comp (ref "JP40")
      (value "01x02")
      (footprint "01x02_0.1in_th_straight_b_nom")
      (description "01X02 generic terminal connector")
      (libsource (lib "Chip1_TestBoard") (part "01x02"))
    )
    (comp (ref "JP41")
      (value "01x02")
      (footprint "01x02_0.1in_th_straight_b_nom")
      (description "01X02 generic terminal connector")
      (libsource (lib "Chip1_TestBoard") (part "01x02"))
    )
    (comp (ref "JP42")
      (value "01x02")
      (footprint "01x02_0.1in_th_straight_b_nom")
      (description "01X02 generic terminal connector")
      (libsource (lib "Chip1_TestBoard") (part "01x02"))
    )
    (comp (ref "JP43")
      (value "01x02")
      (footprint "01x02_0.1in_th_straight_b_nom")
      (description "01X02 generic terminal connector")
      (libsource (lib "Chip1_TestBoard") (part "01x02"))
    )
    (comp (ref "JP44")
      (value "01x02")
      (footprint "01x02_0.1in_th_straight_b_nom")
      (description "01X02 generic terminal connector")
      (libsource (lib "Chip1_TestBoard") (part "01x02"))
    )
    (comp (ref "JP45")
      (value "01x02")
      (footprint "01x02_0.1in_th_straight_b_nom")
      (description "01X02 generic terminal connector")
      (libsource (lib "Chip1_TestBoard") (part "01x02"))
    )
    (comp (ref "JP46")
      (value "01x02")
      (footprint "01x02_0.1in_th_straight_b_nom")
      (description "01X02 generic terminal connector")
      (libsource (lib "Chip1_TestBoard") (part "01x02"))
    )
    (comp (ref "JP47")
      (value "01x02")
      (footprint "01x02_0.1in_th_straight_b_nom")
      (description "01X02 generic terminal connector")
      (libsource (lib "Chip1_TestBoard") (part "01x02"))
    )
    (comp (ref "JP48")
      (value "01x02")
      (footprint "01x02_0.1in_th_straight_b_nom")
      (description "01X02 generic terminal connector")
      (libsource (lib "Chip1_TestBoard") (part "01x02"))
    )
    (comp (ref "JP49")
      (value "01x02")
      (footprint "01x02_0.1in_th_straight_b_nom")
      (description "01X02 generic terminal connector")
      (libsource (lib "Chip1_TestBoard") (part "01x02"))
    )
    (comp (ref "JP50")
      (value "01x02")
      (footprint "01x02_0.1in_th_straight_b_nom")
      (description "01X02 generic terminal connector")
      (libsource (lib "Chip1_TestBoard") (part "01x02"))
    )
    (comp (ref "JP51")
      (value "01x02")
      (footprint "01x02_0.1in_th_straight_b_nom")
      (description "01X02 generic terminal connector")
      (libsource (lib "Chip1_TestBoard") (part "01x02"))
    )
    (comp (ref "JP52")
      (value "01x02")
      (footprint "01x02_0.1in_th_straight_b_nom")
      (description "01X02 generic terminal connector")
      (libsource (lib "Chip1_TestBoard") (part "01x02"))
    )
    (comp (ref "JP53")
      (value "01x02")
      (footprint "01x02_0.1in_th_straight_b_nom")
      (description "01X02 generic terminal connector")
      (libsource (lib "Chip1_TestBoard") (part "01x02"))
    )
    (comp (ref "JP54")
      (value "01x02")
      (footprint "01x02_0.1in_th_straight_b_nom")
      (description "01X02 generic terminal connector")
      (libsource (lib "Chip1_TestBoard") (part "01x02"))
    )
    (comp (ref "JP55")
      (value "01x02")
      (footprint "01x02_0.1in_th_straight_b_nom")
      (description "01X02 generic terminal connector")
      (libsource (lib "Chip1_TestBoard") (part "01x02"))
    )
    (comp (ref "JP56")
      (value "01x02")
      (footprint "01x02_0.1in_th_straight_b_nom")
      (description "01X02 generic terminal connector")
      (libsource (lib "Chip1_TestBoard") (part "01x02"))
    )
    (comp (ref "JP57")
      (value "01x02")
      (footprint "01x02_0.1in_th_straight_b_nom")
      (description "01X02 generic terminal connector")
      (libsource (lib "Chip1_TestBoard") (part "01x02"))
    )
    (comp (ref "JP58")
      (value "01x02")
      (footprint "01x02_0.1in_th_straight_b_nom")
      (description "01X02 generic terminal connector")
      (libsource (lib "Chip1_TestBoard") (part "01x02"))
    )
    (comp (ref "JP59")
      (value "01x02")
      (footprint "01x02_0.1in_th_straight_b_nom")
      (description "01X02 generic terminal connector")
      (libsource (lib "Chip1_TestBoard") (part "01x02"))
    )
    (comp (ref "JP60")
      (value "01x02")
      (footprint "01x02_0.1in_th_straight_b_nom")
      (description "01X02 generic terminal connector")
      (libsource (lib "Chip1_TestBoard") (part "01x02"))
    )
    (comp (ref "JP61")
      (value "01x02")
      (footprint "01x02_0.1in_th_straight_b_nom")
      (description "01X02 generic terminal connector")
      (libsource (lib "Chip1_TestBoard") (part "01x02"))
    )
    (comp (ref "JP62")
      (value "01x02")
      (footprint "01x02_0.1in_th_straight_b_nom")
      (description "01X02 generic terminal connector")
      (libsource (lib "Chip1_TestBoard") (part "01x02"))
    )
    (comp (ref "JP63")
      (value "01x02")
      (footprint "01x02_0.1in_th_straight_b_nom")
      (description "01X02 generic terminal connector")
      (libsource (lib "Chip1_TestBoard") (part "01x02"))
    )
    (comp (ref "JP64")
      (value "01x02")
      (footprint "01x02_0.1in_th_straight_b_nom")
      (description "01X02 generic terminal connector")
      (libsource (lib "Chip1_TestBoard") (part "01x02"))
    )
    (comp (ref "JP65")
      (value "01x02")
      (footprint "01x02_0.1in_th_straight_b_nom")
      (description "01X02 generic terminal connector")
      (libsource (lib "Chip1_TestBoard") (part "01x02"))
    )
    (comp (ref "JP66")
      (value "01x02")
      (footprint "01x02_0.1in_th_straight_b_nom")
      (description "01X02 generic terminal connector")
      (libsource (lib "Chip1_TestBoard") (part "01x02"))
    )
    (comp (ref "JP67")
      (value "01x02")
      (footprint "01x02_0.1in_th_straight_b_nom")
      (description "01X02 generic terminal connector")
      (libsource (lib "Chip1_TestBoard") (part "01x02"))
    )
    (comp (ref "JP68")
      (value "01x02")
      (footprint "01x02_0.1in_th_straight_b_nom")
      (description "01X02 generic terminal connector")
      (libsource (lib "Chip1_TestBoard") (part "01x02"))
    )
    (comp (ref "JP69")
      (value "01x02")
      (footprint "01x02_0.1in_th_straight_b_nom")
      (description "01X02 generic terminal connector")
      (libsource (lib "Chip1_TestBoard") (part "01x02"))
    )
    (comp (ref "JP70")
      (value "01x02")
      (footprint "01x02_0.1in_th_straight_b_nom")
      (description "01X02 generic terminal connector")
      (libsource (lib "Chip1_TestBoard") (part "01x02"))
    )
    (comp (ref "JP71")
      (value "01x02")
      (footprint "01x02_0.1in_th_straight_b_nom")
      (description "01X02 generic terminal connector")
      (libsource (lib "Chip1_TestBoard") (part "01x02"))
    )
    (comp (ref "JP72")
      (value "01x02")
      (footprint "01x02_0.1in_th_straight_b_nom")
      (description "01X02 generic terminal connector")
      (libsource (lib "Chip1_TestBoard") (part "01x02"))
    )
    (comp (ref "JP73")
      (value "01x02")
      (footprint "01x02_0.1in_th_straight_b_nom")
      (description "01X02 generic terminal connector")
      (libsource (lib "Chip1_TestBoard") (part "01x02"))
    )
    (comp (ref "JP74")
      (value "01x02")
      (footprint "01x02_0.1in_th_straight_b_nom")
      (description "01X02 generic terminal connector")
      (libsource (lib "Chip1_TestBoard") (part "01x02"))
    )
    (comp (ref "JP75")
      (value "01x02")
      (footprint "01x02_0.1in_th_straight_b_nom")
      (description "01X02 generic terminal connector")
      (libsource (lib "Chip1_TestBoard") (part "01x02"))
    )
    (comp (ref "JP76")
      (value "01x02")
      (footprint "01x02_0.1in_th_straight_b_nom")
      (description "01X02 generic terminal connector")
      (libsource (lib "Chip1_TestBoard") (part "01x02"))
    )
    (comp (ref "JP77")
      (value "01x02")
      (footprint "01x02_0.1in_th_straight_b_nom")
      (description "01X02 generic terminal connector")
      (libsource (lib "Chip1_TestBoard") (part "01x02"))
    )
    (comp (ref "JP78")
      (value "01x02")
      (footprint "01x02_0.1in_th_straight_b_nom")
      (description "01X02 generic terminal connector")
      (libsource (lib "Chip1_TestBoard") (part "01x02"))
    )
    (comp (ref "JP79")
      (value "01x02")
      (footprint "01x02_0.1in_th_straight_b_nom")
      (description "01X02 generic terminal connector")
      (libsource (lib "Chip1_TestBoard") (part "01x02"))
    )
    (comp (ref "JP80")
      (value "01x02")
      (footprint "01x02_0.1in_th_straight_b_nom")
      (description "01X02 generic terminal connector")
      (libsource (lib "Chip1_TestBoard") (part "01x02"))
    )
    (comp (ref "JP81")
      (value "01x02")
      (footprint "01x02_0.1in_th_straight_b_nom")
      (description "01X02 generic terminal connector")
      (libsource (lib "Chip1_TestBoard") (part "01x02"))
    )
    (comp (ref "JP82")
      (value "01x02")
      (footprint "01x02_0.1in_th_straight_b_nom")
      (description "01X02 generic terminal connector")
      (libsource (lib "Chip1_TestBoard") (part "01x02"))
    )
    (comp (ref "JP83")
      (value "01x02")
      (footprint "01x02_0.1in_th_straight_b_nom")
      (description "01X02 generic terminal connector")
      (libsource (lib "Chip1_TestBoard") (part "01x02"))
    )
    (comp (ref "JP84")
      (value "01x02")
      (footprint "01x02_0.1in_th_straight_b_nom")
      (description "01X02 generic terminal connector")
      (libsource (lib "Chip1_TestBoard") (part "01x02"))
    )
    (comp (ref "JP85")
      (value "01x02")
      (footprint "01x02_0.1in_th_straight_b_nom")
      (description "01X02 generic terminal connector")
      (libsource (lib "Chip1_TestBoard") (part "01x02"))
    )
    (comp (ref "JP86")
      (value "01x02")
      (footprint "01x02_0.1in_th_straight_b_nom")
      (description "01X02 generic terminal connector")
      (libsource (lib "Chip1_TestBoard") (part "01x02"))
    )
    (comp (ref "JP87")
      (value "01x02")
      (footprint "01x02_0.1in_th_straight_b_nom")
      (description "01X02 generic terminal connector")
      (libsource (lib "Chip1_TestBoard") (part "01x02"))
    )
    (comp (ref "JP88")
      (value "01x02")
      (footprint "01x02_0.1in_th_straight_b_nom")
      (description "01X02 generic terminal connector")
      (libsource (lib "Chip1_TestBoard") (part "01x02"))
    )
    (comp (ref "JP89")
      (value "01x02")
      (footprint "01x02_0.1in_th_straight_b_nom")
      (description "01X02 generic terminal connector")
      (libsource (lib "Chip1_TestBoard") (part "01x02"))
    )
    (comp (ref "JP90")
      (value "01x02")
      (footprint "01x02_0.1in_th_straight_b_nom")
      (description "01X02 generic terminal connector")
      (libsource (lib "Chip1_TestBoard") (part "01x02"))
    )
    (comp (ref "JP91")
      (value "01x02")
      (footprint "01x02_0.1in_th_straight_b_nom")
      (description "01X02 generic terminal connector")
      (libsource (lib "Chip1_TestBoard") (part "01x02"))
    )
    (comp (ref "JP92")
      (value "01x02")
      (footprint "01x02_0.1in_th_straight_b_nom")
      (description "01X02 generic terminal connector")
      (libsource (lib "Chip1_TestBoard") (part "01x02"))
    )
    (comp (ref "JP93")
      (value "01x02")
      (footprint "01x02_0.1in_th_straight_b_nom")
      (description "01X02 generic terminal connector")
      (libsource (lib "Chip1_TestBoard") (part "01x02"))
    )
    (comp (ref "JP94")
      (value "01x02")
      (footprint "01x02_0.1in_th_straight_b_nom")
      (description "01X02 generic terminal connector")
      (libsource (lib "Chip1_TestBoard") (part "01x02"))
    )
    (comp (ref "JP95")
      (value "01x02")
      (footprint "01x02_0.1in_th_straight_b_nom")
      (description "01X02 generic terminal connector")
      (libsource (lib "Chip1_TestBoard") (part "01x02"))
    )
    (comp (ref "JP96")
      (value "01x02")
      (footprint "01x02_0.1in_th_straight_b_nom")
      (description "01X02 generic terminal connector")
      (libsource (lib "Chip1_TestBoard") (part "01x02"))
    )
    (comp (ref "JP97")
      (value "01x02")
      (footprint "01x02_0.1in_th_straight_b_nom")
      (description "01X02 generic terminal connector")
      (libsource (lib "Chip1_TestBoard") (part "01x02"))
    )
    (comp (ref "JP98")
      (value "01x02")
      (footprint "01x02_0.1in_th_straight_b_nom")
      (description "01X02 generic terminal connector")
      (libsource (lib "Chip1_TestBoard") (part "01x02"))
    )
    (comp (ref "JP99")
      (value "01x02")
      (footprint "01x02_0.1in_th_straight_b_nom")
      (description "01X02 generic terminal connector")
      (libsource (lib "Chip1_TestBoard") (part "01x02"))
    )
    (comp (ref "JP100")
      (value "01x02")
      (footprint "01x02_0.1in_th_straight_b_nom")
      (description "01X02 generic terminal connector")
      (libsource (lib "Chip1_TestBoard") (part "01x02"))
    )
    (comp (ref "JP101")
      (value "01x02")
      (footprint "01x02_0.1in_th_straight_b_nom")
      (description "01X02 generic terminal connector")
      (libsource (lib "Chip1_TestBoard") (part "01x02"))
    )
    (comp (ref "JP102")
      (value "01x02")
      (footprint "01x02_0.1in_th_straight_b_nom")
      (description "01X02 generic terminal connector")
      (libsource (lib "Chip1_TestBoard") (part "01x02"))
    )
    (comp (ref "JP103")
      (value "01x02")
      (footprint "01x02_0.1in_th_straight_b_nom")
      (description "01X02 generic terminal connector")
      (libsource (lib "Chip1_TestBoard") (part "01x02"))
    )
    (comp (ref "JP104")
      (value "01x02")
      (footprint "01x02_0.1in_th_straight_b_nom")
      (description "01X02 generic terminal connector")
      (libsource (lib "Chip1_TestBoard") (part "01x02"))
    )
    (comp (ref "JP105")
      (value "01x02")
      (footprint "01x02_0.1in_th_straight_b_nom")
      (description "01X02 generic terminal connector")
      (libsource (lib "Chip1_TestBoard") (part "01x02"))
    )
    (comp (ref "MH1")
      (value "MH_7.4MMC_3.2MMD")
      (footprint "CLS_Library:MH_7.4MMD_3.2MMD")
      (description "Mounting Hole 7.4mm Diameter, 3.2mm Drill")
      (libsource (lib "CLS_Library") (part "MH_7.4MMC_3.2MMC"))
    )
    (comp (ref "MH2")
      (value "MH_7.4MMC_3.2MMD")
      (footprint "CLS_Library:MH_7.4MMD_3.2MMD")
      (description "Mounting Hole 7.4mm Diameter, 3.2mm Drill")
      (libsource (lib "CLS_Library") (part "MH_7.4MMC_3.2MMC"))
    )
    (comp (ref "MH3")
      (value "MH_7.4MMC_3.2MMD")
      (footprint "CLS_Library:MH_7.4MMD_3.2MMD")
      (description "Mounting Hole 7.4mm Diameter, 3.2mm Drill")
      (libsource (lib "CLS_Library") (part "MH_7.4MMC_3.2MMC"))
    )
    (comp (ref "MH4")
      (value "MH_7.4MMC_3.2MMD")
      (footprint "CLS_Library:MH_7.4MMD_3.2MMD")
      (description "Mounting Hole 7.4mm Diameter, 3.2mm Drill")
      (libsource (lib "CLS_Library") (part "MH_7.4MMC_3.2MMC"))
    )
    (comp (ref "POWER1")
      (value "PWR-2.1MM")
      (footprint "CLS_Library:POWER2.1MM")
      (description "PJ-002AH")
      (fields (field (name "MANUFACTURER") "CUI"))
      (libsource (lib "CLS_Library") (part "PWR-2.1MM"))
    )
    (comp (ref "R1") (value "500k") (footprint "R0805") (libsource (lib "CLS_Library") (part "RES")))
    (comp (ref "R2") (value "500k") (footprint "R0805") (libsource (lib "CLS_Library") (part "RES")))
    (comp (ref "R3") (value "500k") (footprint "R0805") (libsource (lib "CLS_Library") (part "RES")))
    (comp (ref "R4") (value "500k") (footprint "R0805") (libsource (lib "CLS_Library") (part "RES")))
    (comp (ref "R5") (value "500k") (footprint "R0805") (libsource (lib "CLS_Library") (part "RES")))
    (comp (ref "R6") (value "500k") (footprint "R0805") (libsource (lib "CLS_Library") (part "RES")))
    (comp (ref "R7") (value "500k") (footprint "R0805") (libsource (lib "CLS_Library") (part "RES")))
    (comp (ref "R8") (value "500k") (footprint "R0805") (libsource (lib "CLS_Library") (part "RES")))
    (comp (ref "R9") (value "500k") (footprint "R0805") (libsource (lib "CLS_Library") (part "RES")))
    (comp (ref "R10") (value "500k") (footprint "R0805") (libsource (lib "CLS_Library") (part "RES")))
    (comp (ref "R11") (value "500k") (footprint "R0805") (libsource (lib "CLS_Library") (part "RES")))
    (comp (ref "R12") (value "500k") (footprint "R0805") (libsource (lib "CLS_Library") (part "RES")))
    (comp (ref "R13") (value "500k") (footprint "R0805") (libsource (lib "CLS_Library") (part "RES")))
    (comp (ref "R14") (value "500k") (footprint "R0805") (libsource (lib "CLS_Library") (part "RES")))
    (comp (ref "R15") (value "500k") (footprint "R0805") (libsource (lib "CLS_Library") (part "RES")))
    (comp (ref "R16") (value "500k") (footprint "R0805") (libsource (lib "CLS_Library") (part "RES")))
    (comp (ref "R17") (value "500k") (footprint "R0805") (libsource (lib "CLS_Library") (part "RES")))
    (comp (ref "R18") (value "500k") (footprint "R0805") (libsource (lib "CLS_Library") (part "RES")))
    (comp (ref "R19") (value "500k") (footprint "R0805") (libsource (lib "CLS_Library") (part "RES")))
    (comp (ref "R20") (value "500k") (footprint "R0805") (libsource (lib "CLS_Library") (part "RES")))
    (comp (ref "R21") (value "500k") (footprint "R0805") (libsource (lib "CLS_Library") (part "RES")))
    (comp (ref "R22") (value "500k") (footprint "R0805") (libsource (lib "CLS_Library") (part "RES")))
    (comp (ref "R23") (value "500k") (footprint "R0805") (libsource (lib "CLS_Library") (part "RES")))
    (comp (ref "R24") (value "500k") (footprint "R0805") (libsource (lib "CLS_Library") (part "RES")))
    (comp (ref "R25") (value "500k") (footprint "R0805") (libsource (lib "CLS_Library") (part "RES")))
    (comp (ref "R26") (value "500k") (footprint "R0805") (libsource (lib "CLS_Library") (part "RES")))
    (comp (ref "R27") (value "500k") (footprint "R0805") (libsource (lib "CLS_Library") (part "RES")))
    (comp (ref "R28") (value "500k") (footprint "R0805") (libsource (lib "CLS_Library") (part "RES")))
    (comp (ref "R29") (value "500k") (footprint "R0805") (libsource (lib "CLS_Library") (part "RES")))
    (comp (ref "R30") (value "500k") (footprint "R0805") (libsource (lib "CLS_Library") (part "RES")))
    (comp (ref "R31") (value "500k") (footprint "R0805") (libsource (lib "CLS_Library") (part "RES")))
    (comp (ref "R32") (value "500k") (footprint "R0805") (libsource (lib "CLS_Library") (part "RES")))
    (comp (ref "R33") (value "500k") (footprint "R0805") (libsource (lib "CLS_Library") (part "RES")))
    (comp (ref "R34") (value "500k") (footprint "R0805") (libsource (lib "CLS_Library") (part "RES")))
    (comp (ref "R35") (value "500k") (footprint "R0805") (libsource (lib "CLS_Library") (part "RES")))
    (comp (ref "R36") (value "500k") (footprint "R0805") (libsource (lib "CLS_Library") (part "RES")))
    (comp (ref "R37") (value "500k") (footprint "R0805") (libsource (lib "CLS_Library") (part "RES")))
    (comp (ref "R38") (value "500k") (footprint "R0805") (libsource (lib "CLS_Library") (part "RES")))
    (comp (ref "R39") (value "500k") (footprint "R0805") (libsource (lib "CLS_Library") (part "RES")))
    (comp (ref "R40") (value "500k") (footprint "R0805") (libsource (lib "CLS_Library") (part "RES")))
    (comp (ref "R41") (value "500k") (footprint "R0805") (libsource (lib "CLS_Library") (part "RES")))
    (comp (ref "R42") (value "500k") (footprint "R0805") (libsource (lib "CLS_Library") (part "RES")))
    (comp (ref "R43") (value "500k") (footprint "R0805") (libsource (lib "CLS_Library") (part "RES")))
    (comp (ref "R44") (value "500k") (footprint "R0805") (libsource (lib "CLS_Library") (part "RES")))
    (comp (ref "R45") (value "500k") (footprint "R0805") (libsource (lib "CLS_Library") (part "RES")))
    (comp (ref "R46") (value "500k") (footprint "R0805") (libsource (lib "CLS_Library") (part "RES")))
    (comp (ref "R47") (value "500k") (footprint "R0805") (libsource (lib "CLS_Library") (part "RES")))
    (comp (ref "R48") (value "500k") (footprint "R0805") (libsource (lib "CLS_Library") (part "RES")))
    (comp (ref "R49") (value "500k") (footprint "R0805") (libsource (lib "CLS_Library") (part "RES")))
    (comp (ref "R50") (value "500k") (footprint "R0805") (libsource (lib "CLS_Library") (part "RES")))
    (comp (ref "R51") (value "500k") (footprint "R0805") (libsource (lib "CLS_Library") (part "RES")))
    (comp (ref "R52") (value "500k") (footprint "R0805") (libsource (lib "CLS_Library") (part "RES")))
    (comp (ref "R53") (value "500k") (footprint "R0805") (libsource (lib "CLS_Library") (part "RES")))
    (comp (ref "R54") (value "500k") (footprint "R0805") (libsource (lib "CLS_Library") (part "RES")))
    (comp (ref "R55") (value "500k") (footprint "R0805") (libsource (lib "CLS_Library") (part "RES")))
    (comp (ref "R56") (value "500k") (footprint "R0805") (libsource (lib "CLS_Library") (part "RES")))
    (comp (ref "R57") (value "500k") (footprint "R0805") (libsource (lib "CLS_Library") (part "RES")))
    (comp (ref "R58") (value "500k") (footprint "R0805") (libsource (lib "CLS_Library") (part "RES")))
    (comp (ref "R59") (value "500k") (footprint "R0805") (libsource (lib "CLS_Library") (part "RES")))
    (comp (ref "R60") (value "500k") (footprint "R0805") (libsource (lib "CLS_Library") (part "RES")))
    (comp (ref "R61") (value "500k") (footprint "R0805") (libsource (lib "CLS_Library") (part "RES")))
    (comp (ref "R62") (value "500k") (footprint "R0805") (libsource (lib "CLS_Library") (part "RES")))
    (comp (ref "R63") (value "500k") (footprint "R0805") (libsource (lib "CLS_Library") (part "RES")))
    (comp (ref "R64") (value "500k") (footprint "R0805") (libsource (lib "CLS_Library") (part "RES")))
    (comp (ref "R65") (value "500k") (footprint "R0805") (libsource (lib "CLS_Library") (part "RES")))
    (comp (ref "R66") (value "500k") (footprint "R0805") (libsource (lib "CLS_Library") (part "RES")))
    (comp (ref "R67") (value "500k") (footprint "R0805") (libsource (lib "CLS_Library") (part "RES")))
    (comp (ref "R68") (value "500k") (footprint "R0805") (libsource (lib "CLS_Library") (part "RES")))
    (comp (ref "R69") (value "500k") (footprint "R0805") (libsource (lib "CLS_Library") (part "RES")))
    (comp (ref "R70") (value "500k") (footprint "R0805") (libsource (lib "CLS_Library") (part "RES")))
    (comp (ref "R71") (value "500k") (footprint "R0805") (libsource (lib "CLS_Library") (part "RES")))
    (comp (ref "R72") (value "500k") (footprint "R0805") (libsource (lib "CLS_Library") (part "RES")))
    (comp (ref "R73") (value "500k") (footprint "R0805") (libsource (lib "CLS_Library") (part "RES")))
    (comp (ref "R74") (value "500k") (footprint "R0805") (libsource (lib "CLS_Library") (part "RES")))
    (comp (ref "R75") (value "500k") (footprint "R0805") (libsource (lib "CLS_Library") (part "RES")))
    (comp (ref "R76") (value "500k") (footprint "R0805") (libsource (lib "CLS_Library") (part "RES")))
    (comp (ref "R77") (value "500k") (footprint "R0805") (libsource (lib "CLS_Library") (part "RES")))
    (comp (ref "R78") (value "500k") (footprint "R0805") (libsource (lib "CLS_Library") (part "RES")))
    (comp (ref "R79") (value "500k") (footprint "R0805") (libsource (lib "CLS_Library") (part "RES")))
    (comp (ref "R80") (value "500k") (footprint "R0805") (libsource (lib "CLS_Library") (part "RES")))
    (comp (ref "R81") (value "500k") (footprint "R0805") (libsource (lib "CLS_Library") (part "RES")))
    (comp (ref "R82") (value "500k") (footprint "R0805") (libsource (lib "CLS_Library") (part "RES")))
    (comp (ref "R83") (value "500k") (footprint "R0805") (libsource (lib "CLS_Library") (part "RES")))
    (comp (ref "R84") (value "500k") (footprint "R0805") (libsource (lib "CLS_Library") (part "RES")))
    (comp (ref "R85") (value "500k") (footprint "R0805") (libsource (lib "CLS_Library") (part "RES")))
    (comp (ref "R86") (value "500k") (footprint "R0805") (libsource (lib "CLS_Library") (part "RES")))
    (comp (ref "R87") (value "500k") (footprint "R0805") (libsource (lib "CLS_Library") (part "RES")))
    (comp (ref "R88") (value "500k") (footprint "R0805") (libsource (lib "CLS_Library") (part "RES")))
    (comp (ref "R89") (value "500k") (footprint "R0805") (libsource (lib "CLS_Library") (part "RES")))
    (comp (ref "R90") (value "500k") (footprint "R0805") (libsource (lib "CLS_Library") (part "RES")))
    (comp (ref "R91") (value "500k") (footprint "R0805") (libsource (lib "CLS_Library") (part "RES")))
    (comp (ref "R92") (value "500k") (footprint "R0805") (libsource (lib "CLS_Library") (part "RES")))
    (comp (ref "R93") (value "500k") (footprint "R0805") (libsource (lib "CLS_Library") (part "RES")))
    (comp (ref "R94") (value "500k") (footprint "R0805") (libsource (lib "CLS_Library") (part "RES")))
    (comp (ref "R95") (value "500k") (footprint "R0805") (libsource (lib "CLS_Library") (part "RES")))
    (comp (ref "R96") (value "500k") (footprint "R0805") (libsource (lib "CLS_Library") (part "RES")))
    (comp (ref "R97") (value "500k") (footprint "R0805") (libsource (lib "CLS_Library") (part "RES")))
    (comp (ref "R98") (value "500k") (footprint "R0805") (libsource (lib "CLS_Library") (part "RES")))
    (comp (ref "R99") (value "500k") (footprint "R0805") (libsource (lib "CLS_Library") (part "RES")))
    (comp (ref "R100") (value "500k") (footprint "R0805") (libsource (lib "CLS_Library") (part "RES")))
    (comp (ref "R101") (value "500k") (footprint "R0805") (libsource (lib "CLS_Library") (part "RES")))
    (comp (ref "R102") (value "500k") (footprint "R0805") (libsource (lib "CLS_Library") (part "RES")))
    (comp (ref "R103") (value "500k") (footprint "R0805") (libsource (lib "CLS_Library") (part "RES")))
    (comp (ref "R104") (value "500k") (footprint "R0805") (libsource (lib "CLS_Library") (part "RES")))
    (comp (ref "S1")
      (value "SW-SPST")
      (footprint "CLS_Library:SPST-2")
      (description "L101011MS02Q")
      (fields (field (name "MANUFACTURER") "ITT C&K"))
      (libsource (lib "CLS_Library") (part "SW-SPST"))
    )
    (comp (ref "TP1")
      (value "Testing_Port")
      (footprint "Testing_point")
      (description "01X01 generic terminal connector")
      (libsource (lib "CLS_Library") (part "Testing_Port"))
    )
  )
  (nets
    (net (code "28") (name "/ADC1_CLKOUT") (class "Default")
      (node (ref "FMC HPC1") (pin "G30") (pinfunction "LA29_P_G30") (pintype "passive"))
    )
    (net (code "29") (name "/ADC1_SCK") (class "Default")
      (node (ref "FMC HPC1") (pin "H32") (pinfunction "LA28_N_H32") (pintype "passive"))
    )
    (net (code "30") (name "/ADC1_SDO1") (class "Default")
      (node (ref "FMC HPC1") (pin "H26") (pinfunction "LA21_N_H26") (pintype "passive"))
    )
    (net (code "31") (name "/ADC1_SDO2") (class "Default")
      (node (ref "FMC HPC1") (pin "G24") (pinfunction "LA22_P_G24") (pintype "passive"))
    )
    (net (code "32") (name "/ADC1_SDO3") (class "Default")
      (node (ref "FMC HPC1") (pin "H25") (pinfunction "LA21_P_H25") (pintype "passive"))
    )
    (net (code "33") (name "/ADC1_SDO4") (class "Default")
      (node (ref "FMC HPC1") (pin "G22") (pinfunction "LA20_N_G22") (pintype "passive"))
    )
    (net (code "34") (name "/ADC1_SDO5") (class "Default")
      (node (ref "FMC HPC1") (pin "H23") (pinfunction "LA19_N_H23") (pintype "passive"))
    )
    (net (code "35") (name "/ADC1_SDO6") (class "Default")
      (node (ref "FMC HPC1") (pin "G21") (pinfunction "LA20_P_G21") (pintype "passive"))
    )
    (net (code "36") (name "/ADC1_SDO7") (class "Default")
      (node (ref "FMC HPC1") (pin "H22") (pinfunction "LA19_P_H22") (pintype "passive"))
    )
    (net (code "37") (name "/ADC1_SDO8") (class "Default")
      (node (ref "FMC HPC1") (pin "G19") (pinfunction "LA16_N_G19") (pintype "passive"))
    )
    (net (code "38") (name "/ADC1_~{CLKEN}") (class "Default")
      (node (ref "FMC HPC1") (pin "H34") (pinfunction "LA30_P_H34") (pintype "passive"))
    )
    (net (code "39") (name "/ADC1_~{CNV}") (class "Default")
      (node (ref "FMC HPC1") (pin "G31") (pinfunction "LA29_N_G31") (pintype "passive"))
    )
    (net (code "40") (name "/ADC2_CLKOUT") (class "Default")
      (node (ref "FMC HPC1") (pin "D11") (pinfunction "LA05_P_D11") (pintype "passive"))
    )
    (net (code "41") (name "/ADC2_SCK") (class "Default")
      (node (ref "FMC HPC1") (pin "D8") (pinfunction "LA01_P_CC_D8") (pintype "passive"))
    )
    (net (code "42") (name "/ADC2_SDO1") (class "Default")
      (node (ref "FMC HPC1") (pin "C14") (pinfunction "LA10_P_C14") (pintype "passive"))
    )
    (net (code "43") (name "/ADC2_SDO2") (class "Default")
      (node (ref "FMC HPC1") (pin "D12") (pinfunction "LA05_N_D12") (pintype "passive"))
    )
    (net (code "44") (name "/ADC2_SDO3") (class "Default")
      (node (ref "FMC HPC1") (pin "D9") (pinfunction "LA01_N_CC_D9") (pintype "passive"))
    )
    (net (code "45") (name "/ADC2_SDO4") (class "Default")
      (node (ref "FMC HPC1") (pin "C10") (pinfunction "LA06_P_C10") (pintype "passive"))
    )
    (net (code "46") (name "/ADC2_~{CLKEN}") (class "Default")
      (node (ref "FMC HPC1") (pin "C11") (pinfunction "LA06_N_C11") (pintype "passive"))
    )
    (net (code "47") (name "/ADC2_~{CNV}") (class "Default")
      (node (ref "FMC HPC1") (pin "C15") (pinfunction "LA10_N_C15") (pintype "passive"))
    )
    (net (code "48") (name "/ADC3_CLKOUT") (class "Default")
      (node (ref "FMC HPC1") (pin "E15") (pinfunction "HA16_P_E15") (pintype "passive"))
    )
    (net (code "49") (name "/ADC3_SCK") (class "Default")
      (node (ref "FMC HPC1") (pin "E9") (pinfunction "HA09_P_E9") (pintype "passive"))
    )
    (net (code "50") (name "/ADC3_SDO1") (class "Default")
      (node (ref "FMC HPC1") (pin "E18") (pinfunction "HA20_P_E18") (pintype "passive"))
    )
    (net (code "51") (name "/ADC3_SDO2") (class "Default")
      (node (ref "FMC HPC1") (pin "E16") (pinfunction "HA16_N_E16") (pintype "passive"))
    )
    (net (code "52") (name "/ADC3_SDO3") (class "Default")
      (node (ref "FMC HPC1") (pin "E12") (pinfunction "HA13_P_E12") (pintype "passive"))
    )
    (net (code "53") (name "/ADC3_SDO4") (class "Default")
      (node (ref "FMC HPC1") (pin "E10") (pinfunction "HA09_N_E10") (pintype "passive"))
    )
    (net (code "54") (name "/ADC3_~{CLKEN}") (class "Default")
      (node (ref "FMC HPC1") (pin "E13") (pinfunction "HA13_N_E13") (pintype "passive"))
    )
    (net (code "55") (name "/ADC3_~{CNV}") (class "Default")
      (node (ref "FMC HPC1") (pin "E19") (pinfunction "HA20_N_E19") (pintype "passive"))
    )
    (net (code "56") (name "/ADC4_BUSY") (class "Default")
      (node (ref "FMC HPC1") (pin "H19") (pinfunction "LA15_P_H19") (pintype "passive"))
    )
    (net (code "57") (name "/ADC4_CONVST") (class "Default")
      (node (ref "FMC HPC1") (pin "J15") (pinfunction "HA14_P_J15") (pintype "passive"))
    )
    (net (code "58") (name "/ADC4_D0") (class "Default")
      (node (ref "FMC HPC1") (pin "H17") (pinfunction "LA11_N_H17") (pintype "passive"))
    )
    (net (code "59") (name "/ADC4_D1") (class "Default")
      (node (ref "FMC HPC1") (pin "G16") (pinfunction "LA12_N_G16") (pintype "passive"))
    )
    (net (code "60") (name "/ADC4_D2") (class "Default")
      (node (ref "FMC HPC1") (pin "H16") (pinfunction "LA11_P_H16") (pintype "passive"))
    )
    (net (code "61") (name "/ADC4_D3") (class "Default")
      (node (ref "FMC HPC1") (pin "G15") (pinfunction "LA12_P_G15") (pintype "passive"))
    )
    (net (code "62") (name "/ADC4_D4") (class "Default")
      (node (ref "FMC HPC1") (pin "H14") (pinfunction "LA07_N_H14") (pintype "passive"))
    )
    (net (code "63") (name "/ADC4_D5") (class "Default")
      (node (ref "FMC HPC1") (pin "G13") (pinfunction "LA08_N_G13") (pintype "passive"))
    )
    (net (code "64") (name "/ADC4_D6") (class "Default")
      (node (ref "FMC HPC1") (pin "H13") (pinfunction "LA07_P_H13") (pintype "passive"))
    )
    (net (code "65") (name "/ADC4_D7") (class "Default")
      (node (ref "FMC HPC1") (pin "G12") (pinfunction "LA08_P_G12") (pintype "passive"))
    )
    (net (code "66") (name "/ADC4_D8") (class "Default")
      (node (ref "FMC HPC1") (pin "H11") (pinfunction "LA04_N_H11") (pintype "passive"))
    )
    (net (code "67") (name "/ADC4_D9") (class "Default")
      (node (ref "FMC HPC1") (pin "G10") (pinfunction "LA03_N_G10") (pintype "passive"))
    )
    (net (code "68") (name "/ADC4_D10") (class "Default")
      (node (ref "FMC HPC1") (pin "H10") (pinfunction "LA04_P_H10") (pintype "passive"))
    )
    (net (code "69") (name "/ADC4_D11") (class "Default")
      (node (ref "FMC HPC1") (pin "G9") (pinfunction "LA03_P_G9") (pintype "passive"))
    )
    (net (code "70") (name "/ADC4_D12") (class "Default")
      (node (ref "FMC HPC1") (pin "H8") (pinfunction "LA02_N_H8") (pintype "passive"))
    )
    (net (code "71") (name "/ADC4_D13") (class "Default")
      (node (ref "FMC HPC1") (pin "G7") (pinfunction "LA00_N_CC_G7") (pintype "passive"))
    )
    (net (code "72") (name "/ADC4_D14") (class "Default")
      (node (ref "FMC HPC1") (pin "H7") (pinfunction "LA02_P_H7") (pintype "bidirectional"))
    )
    (net (code "73") (name "/ADC4_D15") (class "Default")
      (node (ref "FMC HPC1") (pin "G6") (pinfunction "LA00_P_CC_G6") (pintype "passive"))
    )
    (net (code "74") (name "/ADC4_FRSTDATA") (class "Default")
      (node (ref "FMC HPC1") (pin "G18") (pinfunction "LA16_P_G18") (pintype "passive"))
    )
    (net (code "75") (name "/ADC4_OS0") (class "Default")
      (node (ref "FMC HPC1") (pin "J22") (pinfunction "HA22_N_J22") (pintype "passive"))
    )
    (net (code "76") (name "/ADC4_OS1") (class "Default")
      (node (ref "FMC HPC1") (pin "J21") (pinfunction "HA22_P_J21") (pintype "passive"))
    )
    (net (code "77") (name "/ADC4_OS2") (class "Default")
      (node (ref "FMC HPC1") (pin "J19") (pinfunction "HA18_N_J19") (pintype "passive"))
    )
    (net (code "78") (name "/ADC4_RANGE") (class "Default")
      (node (ref "FMC HPC1") (pin "J18") (pinfunction "HA18_P_J18") (pintype "passive"))
    )
    (net (code "79") (name "/ADC4_REFSELECT") (class "Default")
      (node (ref "FMC HPC1") (pin "J7") (pinfunction "HA03_N_J7") (pintype "passive"))
    )
    (net (code "80") (name "/ADC4_RESET") (class "Default")
      (node (ref "FMC HPC1") (pin "J9") (pinfunction "HA07_P_J9") (pintype "passive"))
    )
    (net (code "81") (name "/ADC4_~{CS}") (class "Default")
      (node (ref "FMC HPC1") (pin "J6") (pinfunction "HA03_P_J6") (pintype "passive"))
    )
    (net (code "82") (name "/ADC4_~{PAR}{slash}SER{slash}BYTESEL") (class "Default")
      (node (ref "FMC HPC1") (pin "J16") (pinfunction "HA14_N_J16") (pintype "passive"))
    )
    (net (code "83") (name "/ADC4_~{RD}{slash}SCLK") (class "Default")
      (node (ref "FMC HPC1") (pin "J10") (pinfunction "HA07_N_J10") (pintype "passive"))
    )
    (net (code "84") (name "/ADC4_~{STBY}") (class "Default")
      (node (ref "FMC HPC1") (pin "J13") (pinfunction "HA11_N_J13") (pintype "passive"))
    )
    (net (code "85") (name "/ADC4_~{WR}") (class "Default")
      (node (ref "FMC HPC1") (pin "J12") (pinfunction "HA11_P_J12") (pintype "passive"))
    )
    (net (code "86") (name "/ADDR1") (class "Default")
      (node (ref "FMC HPC1") (pin "K19") (pinfunction "HA21_P_K19") (pintype "passive"))
    )
    (net (code "87") (name "/ADDR2") (class "Default")
      (node (ref "FMC HPC1") (pin "K17") (pinfunction "HA17_N_CC_K17") (pintype "passive"))
    )
    (net (code "88") (name "/ADDR3") (class "Default")
      (node (ref "FMC HPC1") (pin "K16") (pinfunction "HA17_P_CC_K16") (pintype "passive"))
    )
    (net (code "89") (name "/ADDR4") (class "Default")
      (node (ref "FMC HPC1") (pin "K11") (pinfunction "HA06_N_K11") (pintype "passive"))
    )
    (net (code "90") (name "/ADDR5") (class "Default")
      (node (ref "FMC HPC1") (pin "K10") (pinfunction "HA06_P_K10") (pintype "passive"))
    )
    (net (code "91") (name "/ADDR6") (class "Default")
      (node (ref "FMC HPC1") (pin "K8") (pinfunction "HA02_N_K8") (pintype "passive"))
    )
    (net (code "92") (name "/COL1") (class "Default")
      (node (ref "ICXTRAP1") (pin "AP20") (pinfunction "C15_AP20") (pintype "passive"))
    )
    (net (code "93") (name "/COL2") (class "Default")
      (node (ref "ICXTRAP1") (pin "AR21") (pinfunction "C39_AR21") (pintype "passive"))
      (node (ref "JP16") (pin "1") (pinfunction "1_1") (pintype "passive"))
    )
    (net (code "94") (name "/COL3") (class "Default")
      (node (ref "ICXTRAP1") (pin "AR23") (pinfunction "C1_AR23") (pintype "passive"))
    )
    (net (code "95") (name "/COL4") (class "Default")
      (node (ref "ICXTRAP1") (pin "AN19") (pinfunction "C16_AN19") (pintype "passive"))
    )
    (net (code "96") (name "/COL5") (class "Default")
      (node (ref "ICXTRAP1") (pin "AR27") (pinfunction "C25_AR27") (pintype "passive"))
      (node (ref "JP2") (pin "1") (pinfunction "1_1") (pintype "passive"))
    )
    (net (code "97") (name "/COL6") (class "Default")
      (node (ref "ICXTRAP1") (pin "AL23") (pinfunction "C50_AL23") (pintype "passive"))
      (node (ref "JP27") (pin "1") (pinfunction "1_1") (pintype "passive"))
    )
    (net (code "98") (name "/COL7") (class "Default")
      (node (ref "ICXTRAP1") (pin "AN25") (pinfunction "C17_AN25") (pintype "passive"))
    )
    (net (code "99") (name "/COL8") (class "Default")
      (node (ref "ICXTRAP1") (pin "AP26") (pinfunction "C28_AP26") (pintype "passive"))
      (node (ref "JP5") (pin "1") (pinfunction "1_1") (pintype "passive"))
    )
    (net (code "100") (name "/COL9") (class "Default")
      (node (ref "ICXTRAP1") (pin "AR19") (pinfunction "C64_AR19") (pintype "passive"))
      (node (ref "JP41") (pin "1") (pinfunction "1_1") (pintype "passive"))
    )
    (net (code "101") (name "/COL10") (class "Default")
      (node (ref "ICXTRAP1") (pin "AP18") (pinfunction "C57_AP18") (pintype "passive"))
      (node (ref "JP34") (pin "1") (pinfunction "1_1") (pintype "passive"))
    )
    (net (code "102") (name "/COL11") (class "Default")
      (node (ref "ICXTRAP1") (pin "AM18") (pinfunction "C30_AM18") (pintype "passive"))
      (node (ref "JP7") (pin "1") (pinfunction "1_1") (pintype "passive"))
    )
    (net (code "103") (name "/COL12") (class "Default")
      (node (ref "ICXTRAP1") (pin "AK18") (pinfunction "C27_AK18") (pintype "passive"))
      (node (ref "JP4") (pin "1") (pinfunction "1_1") (pintype "passive"))
    )
    (net (code "104") (name "/COL13") (class "Default")
      (node (ref "ICXTRAP1") (pin "AK22") (pinfunction "C53_AK22") (pintype "passive"))
      (node (ref "JP30") (pin "1") (pinfunction "1_1") (pintype "passive"))
    )
    (net (code "105") (name "/COL14") (class "Default")
      (node (ref "ICXTRAP1") (pin "AN23") (pinfunction "C12_AN23") (pintype "passive"))
    )
    (net (code "106") (name "/COL15") (class "Default")
      (node (ref "ICXTRAP1") (pin "AM24") (pinfunction "C58_AM24") (pintype "passive"))
      (node (ref "JP35") (pin "1") (pinfunction "1_1") (pintype "passive"))
    )
    (net (code "107") (name "/COL16") (class "Default")
      (node (ref "ICXTRAP1") (pin "AJ21") (pinfunction "C45_AJ21") (pintype "passive"))
      (node (ref "JP22") (pin "1") (pinfunction "1_1") (pintype "passive"))
    )
    (net (code "108") (name "/COL17") (class "Default")
      (node (ref "ICXTRAP1") (pin "AK14") (pinfunction "C23_AK14") (pintype "passive"))
    )
    (net (code "109") (name "/COL18") (class "Default")
      (node (ref "ICXTRAP1") (pin "AJ15") (pinfunction "C6_AJ15") (pintype "passive"))
    )
    (net (code "110") (name "/COL19") (class "Default")
      (node (ref "ICXTRAP1") (pin "AM12") (pinfunction "C48_AM12") (pintype "passive"))
      (node (ref "JP25") (pin "1") (pinfunction "1_1") (pintype "passive"))
    )
    (net (code "111") (name "/COL20") (class "Default")
      (node (ref "ICXTRAP1") (pin "AL13") (pinfunction "C8_AL13") (pintype "passive"))
    )
    (net (code "112") (name "/COL21") (class "Default")
      (node (ref "ICXTRAP1") (pin "AJ17") (pinfunction "C22_AJ17") (pintype "passive"))
    )
    (net (code "113") (name "/COL22") (class "Default")
      (node (ref "ICXTRAP1") (pin "AR9") (pinfunction "C18_AR9") (pintype "passive"))
    )
    (net (code "114") (name "/COL23") (class "Default")
      (node (ref "ICXTRAP1") (pin "AP10") (pinfunction "C29_AP10") (pintype "passive"))
      (node (ref "JP6") (pin "1") (pinfunction "1_1") (pintype "passive"))
    )
    (net (code "115") (name "/COL24") (class "Default")
      (node (ref "ICXTRAP1") (pin "AN11") (pinfunction "C26_AN11") (pintype "passive"))
      (node (ref "JP3") (pin "1") (pinfunction "1_1") (pintype "passive"))
    )
    (net (code "116") (name "/COL25") (class "Default")
      (node (ref "ICXTRAP1") (pin "AN9") (pinfunction "C10_AN9") (pintype "passive"))
    )
    (net (code "117") (name "/COL26") (class "Default")
      (node (ref "ICXTRAP1") (pin "AJ13") (pinfunction "C32_AJ13") (pintype "passive"))
      (node (ref "JP9") (pin "1") (pinfunction "1_1") (pintype "passive"))
    )
    (net (code "118") (name "/COL27") (class "Default")
      (node (ref "ICXTRAP1") (pin "AP8") (pinfunction "C21_AP8") (pintype "passive"))
    )
    (net (code "119") (name "/COL28") (class "Default")
      (node (ref "ICXTRAP1") (pin "AR7") (pinfunction "C13_AR7") (pintype "passive"))
    )
    (net (code "120") (name "/COL29") (class "Default")
      (node (ref "ICXTRAP1") (pin "AR11") (pinfunction "C37_AR11") (pintype "passive"))
      (node (ref "JP14") (pin "1") (pinfunction "1_1") (pintype "passive"))
    )
    (net (code "121") (name "/COL30") (class "Default")
      (node (ref "ICXTRAP1") (pin "AM14") (pinfunction "C47_AM14") (pintype "passive"))
      (node (ref "JP24") (pin "1") (pinfunction "1_1") (pintype "passive"))
    )
    (net (code "122") (name "/COL31") (class "Default")
      (node (ref "ICXTRAP1") (pin "AL15") (pinfunction "C3_AL15") (pintype "passive"))
    )
    (net (code "123") (name "/COL32") (class "Default")
      (node (ref "ICXTRAP1") (pin "AK16") (pinfunction "C14_AK16") (pintype "passive"))
    )
    (net (code "124") (name "/COL33") (class "Default")
      (node (ref "ICXTRAP1") (pin "AP14") (pinfunction "C33_AP14") (pintype "passive"))
      (node (ref "JP10") (pin "1") (pinfunction "1_1") (pintype "passive"))
    )
    (net (code "125") (name "/COL34") (class "Default")
      (node (ref "ICXTRAP1") (pin "AN15") (pinfunction "C44_AN15") (pintype "passive"))
      (node (ref "JP21") (pin "1") (pinfunction "1_1") (pintype "passive"))
    )
    (net (code "126") (name "/COL35") (class "Default")
      (node (ref "ICXTRAP1") (pin "AM16") (pinfunction "C11_AM16") (pintype "passive"))
    )
    (net (code "127") (name "/COL36") (class "Default")
      (node (ref "ICXTRAP1") (pin "AL17") (pinfunction "C19_AL17") (pintype "passive"))
    )
    (net (code "128") (name "/COL37") (class "Default")
      (node (ref "ICXTRAP1") (pin "AP6") (pinfunction "C5_AP6") (pintype "passive"))
    )
    (net (code "129") (name "/COL38") (class "Default")
      (node (ref "ICXTRAP1") (pin "AN7") (pinfunction "C55_AN7") (pintype "passive"))
      (node (ref "JP32") (pin "1") (pinfunction "1_1") (pintype "passive"))
    )
    (net (code "130") (name "/COL39") (class "Default")
      (node (ref "ICXTRAP1") (pin "AN29") (pinfunction "C43_AN29") (pintype "passive"))
      (node (ref "JP20") (pin "1") (pinfunction "1_1") (pintype "passive"))
    )
    (net (code "131") (name "/COL40") (class "Default")
      (node (ref "ICXTRAP1") (pin "AR5") (pinfunction "C2_AR5") (pintype "passive"))
    )
    (net (code "132") (name "/COL41") (class "Default")
      (node (ref "ICXTRAP1") (pin "AR17") (pinfunction "C60_AR17") (pintype "passive"))
      (node (ref "JP37") (pin "1") (pinfunction "1_1") (pintype "passive"))
    )
    (net (code "133") (name "/COL42") (class "Default")
      (node (ref "ICXTRAP1") (pin "AP16") (pinfunction "C52_AP16") (pintype "passive"))
      (node (ref "JP29") (pin "1") (pinfunction "1_1") (pintype "passive"))
    )
    (net (code "134") (name "/COL43") (class "Default")
      (node (ref "ICXTRAP1") (pin "AR15") (pinfunction "C41_AR15") (pintype "passive"))
      (node (ref "JP18") (pin "1") (pinfunction "1_1") (pintype "passive"))
    )
    (net (code "135") (name "/COL44") (class "Default")
      (node (ref "ICXTRAP1") (pin "AN17") (pinfunction "C49_AN17") (pintype "passive"))
      (node (ref "JP26") (pin "1") (pinfunction "1_1") (pintype "passive"))
    )
    (net (code "136") (name "/COL45") (class "Default")
      (node (ref "ICXTRAP1") (pin "AN5") (pinfunction "C24_AN5") (pintype "passive"))
    )
    (net (code "137") (name "/COL46") (class "Default")
      (node (ref "ICXTRAP1") (pin "AP2") (pinfunction "C40_AP2") (pintype "passive"))
      (node (ref "JP17") (pin "1") (pinfunction "1_1") (pintype "passive"))
    )
    (net (code "138") (name "/COL47") (class "Default")
      (node (ref "ICXTRAP1") (pin "AR3") (pinfunction "C31_AR3") (pintype "passive"))
      (node (ref "JP8") (pin "1") (pinfunction "1_1") (pintype "passive"))
    )
    (net (code "139") (name "/COL48") (class "Default")
      (node (ref "ICXTRAP1") (pin "AP4") (pinfunction "C7_AP4") (pintype "passive"))
    )
    (net (code "140") (name "/COL49") (class "Default")
      (node (ref "ICXTRAP1") (pin "AP30") (pinfunction "C46_AP30") (pintype "passive"))
      (node (ref "JP23") (pin "1") (pinfunction "1_1") (pintype "passive"))
    )
    (net (code "141") (name "/COL50") (class "Default")
      (node (ref "ICXTRAP1") (pin "AJ23") (pinfunction "C61_AJ23") (pintype "passive"))
      (node (ref "JP38") (pin "1") (pinfunction "1_1") (pintype "passive"))
    )
    (net (code "142") (name "/COL51") (class "Default")
      (node (ref "ICXTRAP1") (pin "AK24") (pinfunction "C56_AK24") (pintype "passive"))
      (node (ref "JP33") (pin "1") (pinfunction "1_1") (pintype "passive"))
    )
    (net (code "143") (name "/COL52") (class "Default")
      (node (ref "ICXTRAP1") (pin "AP28") (pinfunction "C36_AP28") (pintype "passive"))
      (node (ref "JP13") (pin "1") (pinfunction "1_1") (pintype "passive"))
    )
    (net (code "144") (name "/COL53") (class "Default")
      (node (ref "ICXTRAP1") (pin "AJ19") (pinfunction "C35_AJ19") (pintype "passive"))
      (node (ref "JP12") (pin "1") (pinfunction "1_1") (pintype "passive"))
    )
    (net (code "145") (name "/COL54") (class "Default")
      (node (ref "ICXTRAP1") (pin "AN21") (pinfunction "C63_AN21") (pintype "passive"))
      (node (ref "JP40") (pin "1") (pinfunction "1_1") (pintype "passive"))
    )
    (net (code "146") (name "/COL55") (class "Default")
      (node (ref "ICXTRAP1") (pin "AP22") (pinfunction "C4_AP22") (pintype "passive"))
    )
    (net (code "147") (name "/COL56") (class "Default")
      (node (ref "ICXTRAP1") (pin "AL19") (pinfunction "C38_AL19") (pintype "passive"))
      (node (ref "JP15") (pin "1") (pinfunction "1_1") (pintype "passive"))
    )
    (net (code "148") (name "/COL57") (class "Default")
      (node (ref "ICXTRAP1") (pin "AN33") (pinfunction "C59_AN33") (pintype "passive"))
      (node (ref "JP36") (pin "1") (pinfunction "1_1") (pintype "passive"))
    )
    (net (code "149") (name "/COL58") (class "Default")
      (node (ref "ICXTRAP1") (pin "AP32") (pinfunction "C51_AP32") (pintype "passive"))
      (node (ref "JP28") (pin "1") (pinfunction "1_1") (pintype "passive"))
    )
    (net (code "150") (name "/COL59") (class "Default")
      (node (ref "ICXTRAP1") (pin "AR33") (pinfunction "C54_AR33") (pintype "passive"))
      (node (ref "JP31") (pin "1") (pinfunction "1_1") (pintype "passive"))
    )
    (net (code "151") (name "/COL60") (class "Default")
      (node (ref "ICXTRAP1") (pin "AN31") (pinfunction "C62_AN31") (pintype "passive"))
      (node (ref "JP39") (pin "1") (pinfunction "1_1") (pintype "passive"))
    )
    (net (code "152") (name "/COL61") (class "Default")
      (node (ref "ICXTRAP1") (pin "AP24") (pinfunction "C9_AP24") (pintype "passive"))
    )
    (net (code "153") (name "/COL62") (class "Default")
      (node (ref "ICXTRAP1") (pin "AR25") (pinfunction "C20_AR25") (pintype "passive"))
    )
    (net (code "154") (name "/COL63") (class "Default")
      (node (ref "ICXTRAP1") (pin "AL21") (pinfunction "C34_AL21") (pintype "passive"))
      (node (ref "JP11") (pin "1") (pinfunction "1_1") (pintype "passive"))
    )
    (net (code "155") (name "/COL64") (class "Default")
      (node (ref "ICXTRAP1") (pin "AM22") (pinfunction "C42_AM22") (pintype "passive"))
      (node (ref "JP19") (pin "1") (pinfunction "1_1") (pintype "passive"))
    )
    (net (code "156") (name "/COL65") (class "Default")
      (node (ref "ICXTRAP1") (pin "C17") (pinfunction "C121_C17") (pintype "passive"))
      (node (ref "JP98") (pin "1") (pinfunction "1_1") (pintype "passive"))
    )
    (net (code "157") (name "/COL66") (class "Default")
      (node (ref "ICXTRAP1") (pin "B16") (pinfunction "C106_B16") (pintype "passive"))
      (node (ref "JP83") (pin "1") (pinfunction "1_1") (pintype "passive"))
    )
    (net (code "158") (name "/COL67") (class "Default")
      (node (ref "ICXTRAP1") (pin "E17") (pinfunction "C92_E17") (pintype "passive"))
      (node (ref "JP69") (pin "1") (pinfunction "1_1") (pintype "passive"))
    )
    (net (code "159") (name "/COL68") (class "Default")
      (node (ref "ICXTRAP1") (pin "D16") (pinfunction "C84_D16") (pintype "passive"))
      (node (ref "JP61") (pin "1") (pinfunction "1_1") (pintype "passive"))
    )
    (net (code "160") (name "/COL69") (class "Default")
      (node (ref "ICXTRAP1") (pin "A9") (pinfunction "C91_A9") (pintype "passive"))
      (node (ref "JP68") (pin "1") (pinfunction "1_1") (pintype "passive"))
    )
    (net (code "161") (name "/COL70") (class "Default")
      (node (ref "ICXTRAP1") (pin "E13") (pinfunction "SC65_E13") (pintype "passive"))
      (node (ref "JP42") (pin "1") (pinfunction "1_1") (pintype "passive"))
    )
    (net (code "162") (name "/COL71") (class "Default")
      (node (ref "ICXTRAP1") (pin "C11") (pinfunction "C99_C11") (pintype "passive"))
      (node (ref "JP76") (pin "1") (pinfunction "1_1") (pintype "passive"))
    )
    (net (code "163") (name "/COL72") (class "Default")
      (node (ref "ICXTRAP1") (pin "B10") (pinfunction "C102_B10") (pintype "passive"))
      (node (ref "JP79") (pin "1") (pinfunction "1_1") (pintype "passive"))
    )
    (net (code "164") (name "/COL73") (class "Default")
      (node (ref "ICXTRAP1") (pin "F18") (pinfunction "C103_F18") (pintype "passive"))
      (node (ref "JP80") (pin "1") (pinfunction "1_1") (pintype "passive"))
    )
    (net (code "165") (name "/COL74") (class "Default")
      (node (ref "ICXTRAP1") (pin "B20") (pinfunction "C69_B20") (pintype "passive"))
      (node (ref "JP46") (pin "1") (pinfunction "1_1") (pintype "passive"))
    )
    (net (code "166") (name "/COL75") (class "Default")
      (node (ref "ICXTRAP1") (pin "A15") (pinfunction "C82_A15") (pintype "passive"))
      (node (ref "JP59") (pin "1") (pinfunction "1_1") (pintype "passive"))
    )
    (net (code "167") (name "/COL76") (class "Default")
      (node (ref "ICXTRAP1") (pin "D18") (pinfunction "C100_D18") (pintype "passive"))
      (node (ref "JP77") (pin "1") (pinfunction "1_1") (pintype "passive"))
    )
    (net (code "168") (name "/COL77") (class "Default")
      (node (ref "ICXTRAP1") (pin "C13") (pinfunction "C118_C13") (pintype "passive"))
      (node (ref "JP95") (pin "1") (pinfunction "1_1") (pintype "passive"))
    )
    (net (code "169") (name "/COL78") (class "Default")
      (node (ref "ICXTRAP1") (pin "B12") (pinfunction "C107_B12") (pintype "passive"))
      (node (ref "JP84") (pin "1") (pinfunction "1_1") (pintype "passive"))
    )
    (net (code "170") (name "/COL79") (class "Default")
      (node (ref "ICXTRAP1") (pin "G15") (pinfunction "C79_G15") (pintype "passive"))
      (node (ref "JP56") (pin "1") (pinfunction "1_1") (pintype "passive"))
    )
    (net (code "171") (name "/COL80") (class "Default")
      (node (ref "ICXTRAP1") (pin "F14") (pinfunction "C71_F14") (pintype "passive"))
      (node (ref "JP48") (pin "1") (pinfunction "1_1") (pintype "passive"))
    )
    (net (code "172") (name "/COL81") (class "Default")
      (node (ref "ICXTRAP1") (pin "E23") (pinfunction "C122_E23") (pintype "passive"))
      (node (ref "JP99") (pin "1") (pinfunction "1_1") (pintype "passive"))
    )
    (net (code "173") (name "/COL82") (class "Default")
      (node (ref "ICXTRAP1") (pin "F22") (pinfunction "C98_F22") (pintype "passive"))
      (node (ref "JP75") (pin "1") (pinfunction "1_1") (pintype "passive"))
    )
    (net (code "174") (name "/COL83") (class "Default")
      (node (ref "ICXTRAP1") (pin "C25") (pinfunction "C101_C25") (pintype "passive"))
      (node (ref "JP78") (pin "1") (pinfunction "1_1") (pintype "passive"))
    )
    (net (code "175") (name "/COL84") (class "Default")
      (node (ref "ICXTRAP1") (pin "D24") (pinfunction "C89_D24") (pintype "passive"))
      (node (ref "JP66") (pin "1") (pinfunction "1_1") (pintype "passive"))
    )
    (net (code "176") (name "/COL85") (class "Default")
      (node (ref "ICXTRAP1") (pin "F20") (pinfunction "C116_F20") (pintype "passive"))
      (node (ref "JP93") (pin "1") (pinfunction "1_1") (pintype "passive"))
    )
    (net (code "177") (name "/COL86") (class "Default")
      (node (ref "ICXTRAP1") (pin "G19") (pinfunction "C108_G19") (pintype "passive"))
      (node (ref "JP85") (pin "1") (pinfunction "1_1") (pintype "passive"))
    )
    (net (code "178") (name "/COL87") (class "Default")
      (node (ref "ICXTRAP1") (pin "A27") (pinfunction "C109_A27") (pintype "passive"))
      (node (ref "JP86") (pin "1") (pinfunction "1_1") (pintype "passive"))
    )
    (net (code "179") (name "/COL88") (class "Default")
      (node (ref "ICXTRAP1") (pin "B26") (pinfunction "C112_B26") (pintype "passive"))
      (node (ref "JP89") (pin "1") (pinfunction "1_1") (pintype "passive"))
    )
    (net (code "180") (name "/COL89") (class "Default")
      (node (ref "ICXTRAP1") (pin "A29") (pinfunction "C128_A29") (pintype "passive"))
      (node (ref "JP105") (pin "1") (pinfunction "1_1") (pintype "passive"))
    )
    (net (code "181") (name "/COL90") (class "Default")
      (node (ref "ICXTRAP1") (pin "B28") (pinfunction "C120_B28") (pintype "passive"))
      (node (ref "JP97") (pin "1") (pinfunction "1_1") (pintype "passive"))
    )
    (net (code "182") (name "/COL91") (class "Default")
      (node (ref "ICXTRAP1") (pin "G23") (pinfunction "C105_G23") (pintype "passive"))
      (node (ref "JP82") (pin "1") (pinfunction "1_1") (pintype "passive"))
    )
    (net (code "183") (name "/COL92") (class "Default")
      (node (ref "ICXTRAP1") (pin "G21") (pinfunction "C124_G21") (pintype "passive"))
      (node (ref "JP101") (pin "1") (pinfunction "1_1") (pintype "passive"))
    )
    (net (code "184") (name "/COL93") (class "Default")
      (node (ref "ICXTRAP1") (pin "B24") (pinfunction "C93_B24") (pintype "passive"))
      (node (ref "JP70") (pin "1") (pinfunction "1_1") (pintype "passive"))
    )
    (net (code "185") (name "/COL94") (class "Default")
      (node (ref "ICXTRAP1") (pin "C23") (pinfunction "C96_C23") (pintype "passive"))
      (node (ref "JP73") (pin "1") (pinfunction "1_1") (pintype "passive"))
    )
    (net (code "186") (name "/COL95") (class "Default")
      (node (ref "ICXTRAP1") (pin "D22") (pinfunction "C74_D22") (pintype "passive"))
      (node (ref "JP51") (pin "1") (pinfunction "1_1") (pintype "passive"))
    )
    (net (code "187") (name "/COL96") (class "Default")
      (node (ref "ICXTRAP1") (pin "E21") (pinfunction "C127_E21") (pintype "passive"))
      (node (ref "JP104") (pin "1") (pinfunction "1_1") (pintype "passive"))
    )
    (net (code "188") (name "/COL97") (class "Default")
      (node (ref "ICXTRAP1") (pin "C21") (pinfunction "C77_C21") (pintype "passive"))
      (node (ref "JP54") (pin "1") (pinfunction "1_1") (pintype "passive"))
    )
    (net (code "189") (name "/COL98") (class "Default")
      (node (ref "ICXTRAP1") (pin "D20") (pinfunction "C119_D20") (pintype "passive"))
      (node (ref "JP96") (pin "1") (pinfunction "1_1") (pintype "passive"))
    )
    (net (code "190") (name "/COL99") (class "Default")
      (node (ref "ICXTRAP1") (pin "E19") (pinfunction "C111_E19") (pintype "passive"))
      (node (ref "JP88") (pin "1") (pinfunction "1_1") (pintype "passive"))
    )
    (net (code "191") (name "/COL100") (class "Default")
      (node (ref "ICXTRAP1") (pin "A25") (pinfunction "C104_A25") (pintype "passive"))
      (node (ref "JP81") (pin "1") (pinfunction "1_1") (pintype "passive"))
    )
    (net (code "192") (name "/COL101") (class "Default")
      (node (ref "ICXTRAP1") (pin "B30") (pinfunction "C66_B30") (pintype "passive"))
      (node (ref "JP43") (pin "1") (pinfunction "1_1") (pintype "passive"))
    )
    (net (code "193") (name "/COL102") (class "Default")
      (node (ref "ICXTRAP1") (pin "C29") (pinfunction "C90_C29") (pintype "passive"))
      (node (ref "JP67") (pin "1") (pinfunction "1_1") (pintype "passive"))
    )
    (net (code "194") (name "/COL103") (class "Default")
      (node (ref "ICXTRAP1") (pin "C27") (pinfunction "C117_C27") (pintype "passive"))
      (node (ref "JP94") (pin "1") (pinfunction "1_1") (pintype "passive"))
    )
    (net (code "195") (name "/COL104") (class "Default")
      (node (ref "ICXTRAP1") (pin "A31") (pinfunction "C125_A31") (pintype "passive"))
      (node (ref "JP102") (pin "1") (pinfunction "1_1") (pintype "passive"))
    )
    (net (code "196") (name "/COL105") (class "Default")
      (node (ref "ICXTRAP1") (pin "A21") (pinfunction "C80_A21") (pintype "passive"))
      (node (ref "JP57") (pin "1") (pinfunction "1_1") (pintype "passive"))
    )
    (net (code "197") (name "/COL106") (class "Default")
      (node (ref "ICXTRAP1") (pin "C19") (pinfunction "C72_C19") (pintype "passive"))
      (node (ref "JP49") (pin "1") (pinfunction "1_1") (pintype "passive"))
    )
    (net (code "198") (name "/COL107") (class "Default")
      (node (ref "ICXTRAP1") (pin "A23") (pinfunction "C85_A23") (pintype "passive"))
      (node (ref "JP62") (pin "1") (pinfunction "1_1") (pintype "passive"))
    )
    (net (code "199") (name "/COL108") (class "Default")
      (node (ref "ICXTRAP1") (pin "B22") (pinfunction "C88_B22") (pintype "passive"))
      (node (ref "JP65") (pin "1") (pinfunction "1_1") (pintype "passive"))
    )
    (net (code "200") (name "/COL109") (class "Default")
      (node (ref "ICXTRAP1") (pin "C31") (pinfunction "C97_C31") (pintype "passive"))
      (node (ref "JP74") (pin "1") (pinfunction "1_1") (pintype "passive"))
    )
    (net (code "201") (name "/COL110") (class "Default")
      (node (ref "ICXTRAP1") (pin "B34") (pinfunction "C81_B34") (pintype "passive"))
      (node (ref "JP58") (pin "1") (pinfunction "1_1") (pintype "passive"))
    )
    (net (code "202") (name "/COL111") (class "Default")
      (node (ref "ICXTRAP1") (pin "A33") (pinfunction "C114_A33") (pintype "passive"))
      (node (ref "JP91") (pin "1") (pinfunction "1_1") (pintype "passive"))
    )
    (net (code "203") (name "/COL112") (class "Default")
      (node (ref "ICXTRAP1") (pin "B32") (pinfunction "C113_B32") (pintype "passive"))
      (node (ref "JP90") (pin "1") (pinfunction "1_1") (pintype "passive"))
    )
    (net (code "204") (name "/COL113") (class "Default")
      (node (ref "ICXTRAP1") (pin "A5") (pinfunction "C75_A5") (pintype "passive"))
      (node (ref "JP52") (pin "1") (pinfunction "1_1") (pintype "passive"))
    )
    (net (code "205") (name "/COL114") (class "Default")
      (node (ref "ICXTRAP1") (pin "C9") (pinfunction "C83_C9") (pintype "passive"))
      (node (ref "JP60") (pin "1") (pinfunction "1_1") (pintype "passive"))
    )
    (net (code "206") (name "/COL115") (class "Default")
      (node (ref "ICXTRAP1") (pin "B8") (pinfunction "C94_B8") (pintype "passive"))
      (node (ref "JP71") (pin "1") (pinfunction "1_1") (pintype "passive"))
    )
    (net (code "207") (name "/COL116") (class "Default")
      (node (ref "ICXTRAP1") (pin "A7") (pinfunction "C86_A7") (pintype "passive"))
      (node (ref "JP63") (pin "1") (pinfunction "1_1") (pintype "passive"))
    )
    (net (code "208") (name "/COL117") (class "Default")
      (node (ref "ICXTRAP1") (pin "F16") (pinfunction "C87_F16") (pintype "passive"))
      (node (ref "JP64") (pin "1") (pinfunction "1_1") (pintype "passive"))
    )
    (net (code "209") (name "/COL118") (class "Default")
      (node (ref "ICXTRAP1") (pin "C15") (pinfunction "C123_C15") (pintype "passive"))
      (node (ref "JP100") (pin "1") (pinfunction "1_1") (pintype "passive"))
    )
    (net (code "210") (name "/COL119") (class "Default")
      (node (ref "ICXTRAP1") (pin "B14") (pinfunction "C126_B14") (pintype "passive"))
      (node (ref "JP103") (pin "1") (pinfunction "1_1") (pintype "passive"))
    )
    (net (code "211") (name "/COL120") (class "Default")
      (node (ref "ICXTRAP1") (pin "A13") (pinfunction "C115_A13") (pintype "passive"))
      (node (ref "JP92") (pin "1") (pinfunction "1_1") (pintype "passive"))
    )
    (net (code "212") (name "/COL121") (class "Default")
      (node (ref "ICXTRAP1") (pin "B4") (pinfunction "C73_B4") (pintype "passive"))
      (node (ref "JP50") (pin "1") (pinfunction "1_1") (pintype "passive"))
    )
    (net (code "213") (name "/COL122") (class "Default")
      (node (ref "ICXTRAP1") (pin "A3") (pinfunction "C70_A3") (pintype "passive"))
      (node (ref "JP47") (pin "1") (pinfunction "1_1") (pintype "passive"))
    )
    (net (code "214") (name "/COL123") (class "Default")
      (node (ref "ICXTRAP1") (pin "C7") (pinfunction "C67_C7") (pintype "passive"))
      (node (ref "JP44") (pin "1") (pinfunction "1_1") (pintype "passive"))
    )
    (net (code "215") (name "/COL124") (class "Default")
      (node (ref "ICXTRAP1") (pin "B6") (pinfunction "C78_B6") (pintype "passive"))
      (node (ref "JP55") (pin "1") (pinfunction "1_1") (pintype "passive"))
    )
    (net (code "216") (name "/COL125") (class "Default")
      (node (ref "ICXTRAP1") (pin "A11") (pinfunction "C110_A11") (pintype "passive"))
      (node (ref "JP87") (pin "1") (pinfunction "1_1") (pintype "passive"))
    )
    (net (code "217") (name "/COL126") (class "Default")
      (node (ref "ICXTRAP1") (pin "E15") (pinfunction "C76_E15") (pintype "passive"))
      (node (ref "JP53") (pin "1") (pinfunction "1_1") (pintype "passive"))
    )
    (net (code "218") (name "/COL127") (class "Default")
      (node (ref "ICXTRAP1") (pin "D14") (pinfunction "C68_D14") (pintype "passive"))
      (node (ref "JP45") (pin "1") (pinfunction "1_1") (pintype "passive"))
    )
    (net (code "219") (name "/COL128") (class "Default")
      (node (ref "ICXTRAP1") (pin "G17") (pinfunction "C95_G17") (pintype "passive"))
      (node (ref "JP72") (pin "1") (pinfunction "1_1") (pintype "passive"))
    )
    (net (code "221") (name "/COL_DIN1_FPGA") (class "Default")
      (node (ref "FMC HPC1") (pin "F20") (pinfunction "HA19_N_F20") (pintype "passive"))
    )
    (net (code "223") (name "/COL_DIN2_FPGA") (class "Default")
      (node (ref "FMC HPC1") (pin "D26") (pinfunction "LA26_P_D26") (pintype "passive"))
    )
    (net (code "225") (name "/COL_DIN3_FPGA") (class "Default")
      (node (ref "FMC HPC1") (pin "D27") (pinfunction "LA26_N_D27") (pintype "passive"))
    )
    (net (code "234") (name "/DAC1_SCLK") (class "Default")
      (node (ref "FMC HPC1") (pin "C19") (pinfunction "LA14_N_C19") (pintype "passive"))
    )
    (net (code "235") (name "/DAC1_SDI") (class "Default")
      (node (ref "FMC HPC1") (pin "C18") (pinfunction "LA14_P_C18") (pintype "passive"))
    )
    (net (code "237") (name "/DAC1_~{CS}") (class "Default")
      (node (ref "FMC HPC1") (pin "C22") (pinfunction "LA18_P_CC_C22") (pintype "passive"))
    )
    (net (code "246") (name "/DAC2_SCLK") (class "Default")
      (node (ref "FMC HPC1") (pin "C26") (pinfunction "LA27_P_C26") (pintype "passive"))
    )
    (net (code "247") (name "/DAC2_SDI") (class "Default")
      (node (ref "FMC HPC1") (pin "C23") (pinfunction "LA18_N_CC_C23") (pintype "passive"))
    )
    (net (code "249") (name "/DAC2_~{CS}") (class "Default")
      (node (ref "FMC HPC1") (pin "C27") (pinfunction "LA27_N_C27") (pintype "passive"))
    )
    (net (code "250") (name "/DAC3_GAIN") (class "Default")
      (node (ref "FMC HPC1") (pin "G25") (pinfunction "LA22_N_G25") (pintype "passive"))
    )
    (net (code "267") (name "/DAC3_SCLK") (class "Default")
      (node (ref "FMC HPC1") (pin "G27") (pinfunction "LA25_P_G27") (pintype "passive"))
    )
    (net (code "268") (name "/DAC3_SDI") (class "Default")
      (node (ref "FMC HPC1") (pin "H28") (pinfunction "LA24_P_H28") (pintype "passive"))
    )
    (net (code "270") (name "/DAC3_~{LDAC}") (class "Default")
      (node (ref "FMC HPC1") (pin "G28") (pinfunction "LA25_N_G28") (pintype "passive"))
    )
    (net (code "271") (name "/DAC3_~{RESET}") (class "Default")
      (node (ref "FMC HPC1") (pin "H29") (pinfunction "LA24_N_H29") (pintype "passive"))
    )
    (net (code "272") (name "/DAC3_~{SYNC}") (class "Default")
      (node (ref "FMC HPC1") (pin "H31") (pinfunction "LA28_P_H31") (pintype "passive"))
    )
    (net (code "281") (name "/DAC4_SCLK") (class "Default")
      (node (ref "FMC HPC1") (pin "E6") (pinfunction "HA05_P_E6") (pintype "passive"))
    )
    (net (code "282") (name "/DAC4_SDI") (class "Default")
      (node (ref "FMC HPC1") (pin "E3") (pinfunction "HA01_N_CC_E3") (pintype "passive"))
    )
    (net (code "283") (name "/DAC4_SDO") (class "Default")
      (node (ref "FMC HPC1") (pin "E2") (pinfunction "HA01_P_CC_E2") (pintype "passive"))
    )
    (net (code "284") (name "/DAC4_~{CS}") (class "Default")
      (node (ref "FMC HPC1") (pin "E7") (pinfunction "HA05_N_E7") (pintype "passive"))
    )
    (net (code "285") (name "/DAC5_GAIN") (class "Default")
      (node (ref "FMC HPC1") (pin "G33") (pinfunction "LA31_P_G33") (pintype "passive"))
    )
    (net (code "302") (name "/DAC5_SCLK") (class "Default")
      (node (ref "FMC HPC1") (pin "H37") (pinfunction "LA32_P_H37") (pintype "passive"))
    )
    (net (code "303") (name "/DAC5_SDI") (class "Default")
      (node (ref "FMC HPC1") (pin "G34") (pinfunction "LA31_N_G34") (pintype "passive"))
    )
    (net (code "304") (name "/DAC5_SDO") (class "Default")
      (node (ref "FMC HPC1") (pin "H35") (pinfunction "LA30_N_H35") (pintype "passive"))
    )
    (net (code "305") (name "/DAC5_~{LDAC}") (class "Default")
      (node (ref "FMC HPC1") (pin "H38") (pinfunction "LA32_N_H38") (pintype "passive"))
    )
    (net (code "306") (name "/DAC5_~{RESET}") (class "Default")
      (node (ref "FMC HPC1") (pin "G36") (pinfunction "LA33_P_G36") (pintype "passive"))
    )
    (net (code "307") (name "/DAC5_~{SYNC}") (class "Default")
      (node (ref "FMC HPC1") (pin "G37") (pinfunction "LA33_N_G37") (pintype "passive"))
    )
    (net (code "344") (name "/ROW1") (class "Default")
      (node (ref "ICXTRAP1") (pin "T32") (pinfunction "R37_T32") (pintype "passive"))
    )
    (net (code "345") (name "/ROW2") (class "Default")
      (node (ref "ICXTRAP1") (pin "U33") (pinfunction "R12_U33") (pintype "passive"))
    )
    (net (code "346") (name "/ROW3") (class "Default")
      (node (ref "ICXTRAP1") (pin "N35") (pinfunction "R43_N35") (pintype "passive"))
    )
    (net (code "347") (name "/ROW4") (class "Default")
      (node (ref "ICXTRAP1") (pin "U31") (pinfunction "R28_U31") (pintype "passive"))
    )
    (net (code "348") (name "/ROW5") (class "Default")
      (node (ref "ICXTRAP1") (pin "P30") (pinfunction "R55_P30") (pintype "passive"))
    )
    (net (code "349") (name "/ROW6") (class "Default")
      (node (ref "ICXTRAP1") (pin "N31") (pinfunction "R63_N31") (pintype "passive"))
    )
    (net (code "350") (name "/ROW7") (class "Default")
      (node (ref "ICXTRAP1") (pin "N29") (pinfunction "R60_N29") (pintype "passive"))
    )
    (net (code "351") (name "/ROW8") (class "Default")
      (node (ref "ICXTRAP1") (pin "R29") (pinfunction "R49_R29") (pintype "passive"))
    )
    (net (code "352") (name "/ROW9") (class "Default")
      (node (ref "ICXTRAP1") (pin "V32") (pinfunction "R16_V32") (pintype "passive"))
    )
    (net (code "353") (name "/ROW10") (class "Default")
      (node (ref "ICXTRAP1") (pin "V30") (pinfunction "R22_V30") (pintype "passive"))
    )
    (net (code "354") (name "/ROW11") (class "Default")
      (node (ref "ICXTRAP1") (pin "T34") (pinfunction "R41_T34") (pintype "passive"))
    )
    (net (code "355") (name "/ROW12") (class "Default")
      (node (ref "ICXTRAP1") (pin "R35") (pinfunction "R18_R35") (pintype "passive"))
    )
    (net (code "356") (name "/ROW13") (class "Default")
      (node (ref "ICXTRAP1") (pin "J35") (pinfunction "R30_J35") (pintype "passive"))
    )
    (net (code "357") (name "/ROW14") (class "Default")
      (node (ref "ICXTRAP1") (pin "U29") (pinfunction "R31_U29") (pintype "passive"))
    )
    (net (code "358") (name "/ROW15") (class "Default")
      (node (ref "ICXTRAP1") (pin "L33") (pinfunction "R21_L33") (pintype "passive"))
    )
    (net (code "359") (name "/ROW16") (class "Default")
      (node (ref "ICXTRAP1") (pin "K34") (pinfunction "R24_K34") (pintype "passive"))
    )
    (net (code "360") (name "/ROW17") (class "Default")
      (node (ref "ICXTRAP1") (pin "AC31") (pinfunction "R1_AC31") (pintype "passive"))
    )
    (net (code "361") (name "/ROW18") (class "Default")
      (node (ref "ICXTRAP1") (pin "AF34") (pinfunction "R20_AF34") (pintype "passive"))
    )
    (net (code "362") (name "/ROW19") (class "Default")
      (node (ref "ICXTRAP1") (pin "AB30") (pinfunction "R25_AB30") (pintype "passive"))
    )
    (net (code "363") (name "/ROW20") (class "Default")
      (node (ref "ICXTRAP1") (pin "AA29") (pinfunction "R26_AA29") (pintype "passive"))
    )
    (net (code "364") (name "/ROW21") (class "Default")
      (node (ref "ICXTRAP1") (pin "AE35") (pinfunction "R29_AE35") (pintype "passive"))
    )
    (net (code "365") (name "/ROW22") (class "Default")
      (node (ref "ICXTRAP1") (pin "AD34") (pinfunction "R32_AD34") (pintype "passive"))
    )
    (net (code "366") (name "/ROW23") (class "Default")
      (node (ref "ICXTRAP1") (pin "AC33") (pinfunction "R38_AC33") (pintype "passive"))
    )
    (net (code "367") (name "/ROW24") (class "Default")
      (node (ref "ICXTRAP1") (pin "AG35") (pinfunction "R14_AG35") (pintype "passive"))
    )
    (net (code "368") (name "/ROW25") (class "Default")
      (node (ref "ICXTRAP1") (pin "AH34") (pinfunction "R8_AH34") (pintype "passive"))
    )
    (net (code "369") (name "/ROW26") (class "Default")
      (node (ref "ICXTRAP1") (pin "AG33") (pinfunction "R5_AG33") (pintype "passive"))
    )
    (net (code "370") (name "/ROW27") (class "Default")
      (node (ref "ICXTRAP1") (pin "AJ35") (pinfunction "R35_AJ35") (pintype "passive"))
    )
    (net (code "371") (name "/ROW28") (class "Default")
      (node (ref "ICXTRAP1") (pin "AE33") (pinfunction "R23_AE33") (pintype "passive"))
    )
    (net (code "372") (name "/ROW29") (class "Default")
      (node (ref "ICXTRAP1") (pin "Y30") (pinfunction "R27_Y30") (pintype "passive"))
    )
    (net (code "373") (name "/ROW30") (class "Default")
      (node (ref "ICXTRAP1") (pin "W29") (pinfunction "R7_W29") (pintype "passive"))
    )
    (net (code "374") (name "/ROW31") (class "Default")
      (node (ref "ICXTRAP1") (pin "AB32") (pinfunction "R2_AB32") (pintype "passive"))
    )
    (net (code "375") (name "/ROW32") (class "Default")
      (node (ref "ICXTRAP1") (pin "AA31") (pinfunction "R3_AA31") (pintype "passive"))
    )
    (net (code "376") (name "/ROW33") (class "Default")
      (node (ref "ICXTRAP1") (pin "W31") (pinfunction "R13_W31") (pintype "passive"))
    )
    (net (code "377") (name "/ROW34") (class "Default")
      (node (ref "ICXTRAP1") (pin "AC35") (pinfunction "R44_AC35") (pintype "passive"))
    )
    (net (code "378") (name "/ROW35") (class "Default")
      (node (ref "ICXTRAP1") (pin "AB34") (pinfunction "R47_AB34") (pintype "passive"))
    )
    (net (code "379") (name "/ROW36") (class "Default")
      (node (ref "ICXTRAP1") (pin "AA33") (pinfunction "R50_AA33") (pintype "passive"))
    )
    (net (code "380") (name "/ROW37") (class "Default")
      (node (ref "ICXTRAP1") (pin "AK34") (pinfunction "R34_AK34") (pintype "passive"))
    )
    (net (code "381") (name "/ROW38") (class "Default")
      (node (ref "ICXTRAP1") (pin "AJ33") (pinfunction "R10_AJ33") (pintype "passive"))
    )
    (net (code "382") (name "/ROW39") (class "Default")
      (node (ref "ICXTRAP1") (pin "AC29") (pinfunction "R58_AC29") (pintype "passive"))
    )
    (net (code "383") (name "/ROW40") (class "Default")
      (node (ref "ICXTRAP1") (pin "AL35") (pinfunction "R11_AL35") (pintype "passive"))
    )
    (net (code "384") (name "/ROW41") (class "Default")
      (node (ref "ICXTRAP1") (pin "Y34") (pinfunction "R56_Y34") (pintype "passive"))
    )
    (net (code "385") (name "/ROW42") (class "Default")
      (node (ref "ICXTRAP1") (pin "AA35") (pinfunction "R53_AA35") (pintype "passive"))
    )
    (net (code "386") (name "/ROW43") (class "Default")
      (node (ref "ICXTRAP1") (pin "W33") (pinfunction "R62_W33") (pintype "passive"))
    )
    (net (code "387") (name "/ROW44") (class "Default")
      (node (ref "ICXTRAP1") (pin "Y32") (pinfunction "R4_Y32") (pintype "passive"))
    )
    (net (code "388") (name "/ROW45") (class "Default")
      (node (ref "ICXTRAP1") (pin "AL33") (pinfunction "R59_AL33") (pintype "passive"))
    )
    (net (code "389") (name "/ROW46") (class "Default")
      (node (ref "ICXTRAP1") (pin "AP34") (pinfunction "R57_AP34") (pintype "passive"))
    )
    (net (code "390") (name "/ROW47") (class "Default")
      (node (ref "ICXTRAP1") (pin "AN35") (pinfunction "R33_AN35") (pintype "passive"))
    )
    (net (code "391") (name "/ROW48") (class "Default")
      (node (ref "ICXTRAP1") (pin "AM34") (pinfunction "R9_AM34") (pintype "passive"))
    )
    (net (code "392") (name "/ROW49") (class "Default")
      (node (ref "ICXTRAP1") (pin "E35") (pinfunction "R48_E35") (pintype "passive"))
    )
    (net (code "393") (name "/ROW50") (class "Default")
      (node (ref "ICXTRAP1") (pin "J33") (pinfunction "R39_J33") (pintype "passive"))
    )
    (net (code "394") (name "/ROW51") (class "Default")
      (node (ref "ICXTRAP1") (pin "H34") (pinfunction "R36_H34") (pintype "passive"))
    )
    (net (code "395") (name "/ROW52") (class "Default")
      (node (ref "ICXTRAP1") (pin "G35") (pinfunction "R45_G35") (pintype "passive"))
    )
    (net (code "396") (name "/ROW53") (class "Default")
      (node (ref "ICXTRAP1") (pin "M34") (pinfunction "R12_M34") (pintype "passive"))
    )
    (net (code "397") (name "/ROW54") (class "Default")
      (node (ref "ICXTRAP1") (pin "L35") (pinfunction "R15_L35") (pintype "passive"))
    )
    (net (code "398") (name "/ROW55") (class "Default")
      (node (ref "ICXTRAP1") (pin "R33") (pinfunction "R42_R33") (pintype "passive"))
    )
    (net (code "399") (name "/ROW56") (class "Default")
      (node (ref "ICXTRAP1") (pin "P34") (pinfunction "R19_P34") (pintype "passive"))
    )
    (net (code "400") (name "/ROW57") (class "Default")
      (node (ref "ICXTRAP1") (pin "D34") (pinfunction "R61_D34") (pintype "passive"))
    )
    (net (code "401") (name "/ROW58") (class "Default")
      (node (ref "ICXTRAP1") (pin "C35") (pinfunction "R64_C35") (pintype "passive"))
    )
    (net (code "402") (name "/ROW59") (class "Default")
      (node (ref "ICXTRAP1") (pin "G33") (pinfunction "R54_G33") (pintype "passive"))
    )
    (net (code "403") (name "/ROW60") (class "Default")
      (node (ref "ICXTRAP1") (pin "F34") (pinfunction "R51_F34") (pintype "passive"))
    )
    (net (code "404") (name "/ROW61") (class "Default")
      (node (ref "ICXTRAP1") (pin "T30") (pinfunction "R40_T30") (pintype "passive"))
    )
    (net (code "405") (name "/ROW62") (class "Default")
      (node (ref "ICXTRAP1") (pin "R31") (pinfunction "R46_R31") (pintype "passive"))
    )
    (net (code "406") (name "/ROW63") (class "Default")
      (node (ref "ICXTRAP1") (pin "P32") (pinfunction "R52_P32") (pintype "passive"))
    )
    (net (code "407") (name "/ROW64") (class "Default")
      (node (ref "ICXTRAP1") (pin "N33") (pinfunction "R6_N33") (pintype "passive"))
    )
    (net (code "408") (name "/ROW65") (class "Default")
      (node (ref "ICXTRAP1") (pin "Y4") (pinfunction "R101_Y4") (pintype "passive"))
    )
    (net (code "409") (name "/ROW66") (class "Default")
      (node (ref "ICXTRAP1") (pin "W5") (pinfunction "R113_W5") (pintype "passive"))
    )
    (net (code "410") (name "/ROW67") (class "Default")
      (node (ref "ICXTRAP1") (pin "AB2") (pinfunction "R118_AB2") (pintype "passive"))
    )
    (net (code "411") (name "/ROW68") (class "Default")
      (node (ref "ICXTRAP1") (pin "AA3") (pinfunction "R95_AA3") (pintype "passive"))
    )
    (net (code "412") (name "/ROW69") (class "Default")
      (node (ref "ICXTRAP1") (pin "AH2") (pinfunction "R108_AH2") (pintype "passive"))
    )
    (net (code "413") (name "/ROW70") (class "Default")
      (node (ref "ICXTRAP1") (pin "AJ1") (pinfunction "R99_AJ1") (pintype "passive"))
    )
    (net (code "414") (name "/ROW71") (class "Default")
      (node (ref "ICXTRAP1") (pin "AD6") (pinfunction "R68_AD6") (pintype "passive"))
    )
    (net (code "415") (name "/ROW72") (class "Default")
      (node (ref "ICXTRAP1") (pin "AG3") (pinfunction "R105_AG3") (pintype "passive"))
    )
    (net (code "416") (name "/ROW73") (class "Default")
      (node (ref "ICXTRAP1") (pin "W3") (pinfunction "R120_W3") (pintype "passive"))
    )
    (net (code "417") (name "/ROW74") (class "Default")
      (node (ref "ICXTRAP1") (pin "W1") (pinfunction "R69_W1") (pintype "passive"))
    )
    (net (code "418") (name "/ROW75") (class "Default")
      (node (ref "ICXTRAP1") (pin "AA1") (pinfunction "R119_AA1") (pintype "passive"))
    )
    (net (code "419") (name "/ROW76") (class "Default")
      (node (ref "ICXTRAP1") (pin "Y2") (pinfunction "R96_Y2") (pintype "passive"))
    )
    (net (code "420") (name "/ROW77") (class "Default")
      (node (ref "ICXTRAP1") (pin "AC5") (pinfunction "R77_AC5") (pintype "passive"))
    )
    (net (code "421") (name "/ROW78") (class "Default")
      (node (ref "ICXTRAP1") (pin "AD4") (pinfunction "R66_AD4") (pintype "passive"))
    )
    (net (code "422") (name "/ROW79") (class "Default")
      (node (ref "ICXTRAP1") (pin "AA7") (pinfunction "R89_AA7") (pintype "passive"))
    )
    (net (code "423") (name "/ROW80") (class "Default")
      (node (ref "ICXTRAP1") (pin "AB6") (pinfunction "R90_AB6") (pintype "passive"))
    )
    (net (code "424") (name "/ROW81") (class "Default")
      (node (ref "ICXTRAP1") (pin "R7") (pinfunction "R87_R7") (pintype "passive"))
    )
    (net (code "425") (name "/ROW82") (class "Default")
      (node (ref "ICXTRAP1") (pin "M4") (pinfunction "R72_M4") (pintype "passive"))
    )
    (net (code "426") (name "/ROW83") (class "Default")
      (node (ref "ICXTRAP1") (pin "N3") (pinfunction "R100_N3") (pintype "passive"))
    )
    (net (code "427") (name "/ROW84") (class "Default")
      (node (ref "ICXTRAP1") (pin "P6") (pinfunction "R88_P6") (pintype "passive"))
    )
    (net (code "428") (name "/ROW85") (class "Default")
      (node (ref "ICXTRAP1") (pin "U7") (pinfunction "R117_U7") (pintype "passive"))
    )
    (net (code "429") (name "/ROW86") (class "Default")
      (node (ref "ICXTRAP1") (pin "P4") (pinfunction "R111_P4") (pintype "passive"))
    )
    (net (code "430") (name "/ROW87") (class "Default")
      (node (ref "ICXTRAP1") (pin "R5") (pinfunction "R110_R5") (pintype "passive"))
    )
    (net (code "431") (name "/ROW88") (class "Default")
      (node (ref "ICXTRAP1") (pin "M2") (pinfunction "R106_M2") (pintype "passive"))
    )
    (net (code "432") (name "/ROW89") (class "Default")
      (node (ref "ICXTRAP1") (pin "H2") (pinfunction "R116_H2") (pintype "passive"))
    )
    (net (code "433") (name "/ROW90") (class "Default")
      (node (ref "ICXTRAP1") (pin "J3") (pinfunction "R122_J3") (pintype "passive"))
    )
    (net (code "434") (name "/ROW91") (class "Default")
      (node (ref "ICXTRAP1") (pin "G1") (pinfunction "R125_G1") (pintype "passive"))
    )
    (net (code "435") (name "/ROW92") (class "Default")
      (node (ref "ICXTRAP1") (pin "N5") (pinfunction "R112_N5") (pintype "passive"))
    )
    (net (code "436") (name "/ROW93") (class "Default")
      (node (ref "ICXTRAP1") (pin "P2") (pinfunction "R91_P2") (pintype "passive"))
    )
    (net (code "437") (name "/ROW94") (class "Default")
      (node (ref "ICXTRAP1") (pin "R3") (pinfunction "R85_R3") (pintype "passive"))
    )
    (net (code "438") (name "/ROW95") (class "Default")
      (node (ref "ICXTRAP1") (pin "L1") (pinfunction "R109_L1") (pintype "passive"))
    )
    (net (code "439") (name "/ROW96") (class "Default")
      (node (ref "ICXTRAP1") (pin "T6") (pinfunction "R86_T6") (pintype "passive"))
    )
    (net (code "440") (name "/ROW97") (class "Default")
      (node (ref "ICXTRAP1") (pin "U3") (pinfunction "R76_U3") (pintype "passive"))
    )
    (net (code "441") (name "/ROW98") (class "Default")
      (node (ref "ICXTRAP1") (pin "N1") (pinfunction "R97_N1") (pintype "passive"))
    )
    (net (code "442") (name "/ROW99") (class "Default")
      (node (ref "ICXTRAP1") (pin "T4") (pinfunction "R123_T4") (pintype "passive"))
    )
    (net (code "443") (name "/ROW100") (class "Default")
      (node (ref "ICXTRAP1") (pin "U5") (pinfunction "R114_U5") (pintype "passive"))
    )
    (net (code "444") (name "/ROW101") (class "Default")
      (node (ref "ICXTRAP1") (pin "F2") (pinfunction "R126_F2") (pintype "passive"))
    )
    (net (code "445") (name "/ROW102") (class "Default")
      (node (ref "ICXTRAP1") (pin "G3") (pinfunction "R103_G3") (pintype "passive"))
    )
    (net (code "446") (name "/ROW103") (class "Default")
      (node (ref "ICXTRAP1") (pin "N7") (pinfunction "R70_N7") (pintype "passive"))
    )
    (net (code "447") (name "/ROW104") (class "Default")
      (node (ref "ICXTRAP1") (pin "E1") (pinfunction "R102_E1") (pintype "passive"))
    )
    (net (code "448") (name "/ROW105") (class "Default")
      (node (ref "ICXTRAP1") (pin "V2") (pinfunction "R67_V2") (pintype "passive"))
    )
    (net (code "449") (name "/ROW106") (class "Default")
      (node (ref "ICXTRAP1") (pin "U1") (pinfunction "R73_U1") (pintype "passive"))
    )
    (net (code "450") (name "/ROW107") (class "Default")
      (node (ref "ICXTRAP1") (pin "T2") (pinfunction "R79_T2") (pintype "passive"))
    )
    (net (code "451") (name "/ROW108") (class "Default")
      (node (ref "ICXTRAP1") (pin "R1") (pinfunction "R82_R1") (pintype "passive"))
    )
    (net (code "452") (name "/ROW109") (class "Default")
      (node (ref "ICXTRAP1") (pin "E3") (pinfunction "R128_E3") (pintype "passive"))
    )
    (net (code "453") (name "/ROW110") (class "Default")
      (node (ref "ICXTRAP1") (pin "B2") (pinfunction "R71_B2") (pintype "passive"))
    )
    (net (code "454") (name "/ROW111") (class "Default")
      (node (ref "ICXTRAP1") (pin "C1") (pinfunction "R127_C1") (pintype "passive"))
    )
    (net (code "455") (name "/ROW112") (class "Default")
      (node (ref "ICXTRAP1") (pin "D2") (pinfunction "R104_D2") (pintype "passive"))
    )
    (net (code "456") (name "/ROW113") (class "Default")
      (node (ref "ICXTRAP1") (pin "AJ3") (pinfunction "R84_AJ3") (pintype "passive"))
    )
    (net (code "457") (name "/ROW114") (class "Default")
      (node (ref "ICXTRAP1") (pin "AK2") (pinfunction "R90_AK2") (pintype "passive"))
    )
    (net (code "458") (name "/ROW115") (class "Default")
      (node (ref "ICXTRAP1") (pin "AL1") (pinfunction "R93_AL1") (pintype "passive"))
    )
    (net (code "459") (name "/ROW116") (class "Default")
      (node (ref "ICXTRAP1") (pin "AC7") (pinfunction "R74_AC7") (pintype "passive"))
    )
    (net (code "460") (name "/ROW117") (class "Default")
      (node (ref "ICXTRAP1") (pin "AE1") (pinfunction "R115_AE1") (pintype "passive"))
    )
    (net (code "461") (name "/ROW118") (class "Default")
      (node (ref "ICXTRAP1") (pin "AD2") (pinfunction "R121_AD2") (pintype "passive"))
    )
    (net (code "462") (name "/ROW119") (class "Default")
      (node (ref "ICXTRAP1") (pin "AC3") (pinfunction "R124_AC3") (pintype "passive"))
    )
    (net (code "463") (name "/ROW120") (class "Default")
      (node (ref "ICXTRAP1") (pin "AC1") (pinfunction "R94_AC1") (pintype "passive"))
    )
    (net (code "464") (name "/ROW121") (class "Default")
      (node (ref "ICXTRAP1") (pin "AN3") (pinfunction "R65_AN3") (pintype "passive"))
    )
    (net (code "465") (name "/ROW122") (class "Default")
      (node (ref "ICXTRAP1") (pin "AL3") (pinfunction "R75_AL3") (pintype "passive"))
    )
    (net (code "466") (name "/ROW123") (class "Default")
      (node (ref "ICXTRAP1") (pin "AM2") (pinfunction "R78_AM2") (pintype "passive"))
    )
    (net (code "467") (name "/ROW124") (class "Default")
      (node (ref "ICXTRAP1") (pin "AN1") (pinfunction "R81_AN1") (pintype "passive"))
    )
    (net (code "468") (name "/ROW125") (class "Default")
      (node (ref "ICXTRAP1") (pin "W7") (pinfunction "R107_W7") (pintype "passive"))
    )
    (net (code "469") (name "/ROW126") (class "Default")
      (node (ref "ICXTRAP1") (pin "Y6") (pinfunction "R98_Y6") (pintype "passive"))
    )
    (net (code "470") (name "/ROW127") (class "Default")
      (node (ref "ICXTRAP1") (pin "AA5") (pinfunction "R92_AA5") (pintype "passive"))
    )
    (net (code "471") (name "/ROW128") (class "Default")
      (node (ref "ICXTRAP1") (pin "AB4") (pinfunction "R83_AB4") (pintype "passive"))
    )
    (net (code "473") (name "/ROW_DIN1_FPGA") (class "Default")
      (node (ref "FMC HPC1") (pin "D24") (pinfunction "LA23_N_D24") (pintype "passive"))
    )
    (net (code "475") (name "/ROW_DIN2_FPGA") (class "Default")
      (node (ref "FMC HPC1") (pin "D23") (pinfunction "LA23_P_D23") (pintype "passive"))
    )
    (net (code "477") (name "/ROW_DIN3_FPGA") (class "Default")
      (node (ref "FMC HPC1") (pin "D21") (pinfunction "LA17_N_CC_D21") (pintype "passive"))
    )
    (net (code "479") (name "/ROW_DIN4_FPGA") (class "Default")
      (node (ref "FMC HPC1") (pin "D20") (pinfunction "LA17_P_CC_D20") (pintype "passive"))
    )
    (net (code "481") (name "/ROW_DIN5_FPGA") (class "Default")
      (node (ref "FMC HPC1") (pin "D18") (pinfunction "LA13_N_D18") (pintype "passive"))
    )
    (net (code "483") (name "/ROW_DIN6_FPGA") (class "Default")
      (node (ref "FMC HPC1") (pin "D17") (pinfunction "LA13_P_D17") (pintype "passive"))
    )
    (net (code "485") (name "/ROW_DIN7_FPGA") (class "Default")
      (node (ref "FMC HPC1") (pin "D15") (pinfunction "LA09_N_D15") (pintype "passive"))
    )
    (net (code "487") (name "/ROW_DIN8_FPGA") (class "Default")
      (node (ref "FMC HPC1") (pin "D14") (pinfunction "LA09_P_D14") (pintype "passive"))
    )
    (net (code "489") (name "/ROW_DIN9_FPGA") (class "Default")
      (node (ref "FMC HPC1") (pin "F14") (pinfunction "HA12_N_F14") (pintype "passive"))
    )
    (net (code "491") (name "/ROW_DIN10_FPGA") (class "Default")
      (node (ref "FMC HPC1") (pin "F13") (pinfunction "HA12_P_F13") (pintype "passive"))
    )
    (net (code "493") (name "/ROW_DIN11_FPGA") (class "Default")
      (node (ref "FMC HPC1") (pin "F11") (pinfunction "HA08_N_F11") (pintype "passive"))
    )
    (net (code "495") (name "/ROW_DIN12_FPGA") (class "Default")
      (node (ref "FMC HPC1") (pin "F10") (pinfunction "HA08_P_F10") (pintype "passive"))
    )
    (net (code "497") (name "/ROW_DIN13_FPGA") (class "Default")
      (node (ref "FMC HPC1") (pin "F8") (pinfunction "HA04_N_F8") (pintype "passive"))
    )
    (net (code "499") (name "/ROW_DIN14_FPGA") (class "Default")
      (node (ref "FMC HPC1") (pin "F7") (pinfunction "HA04_P_F7") (pintype "passive"))
    )
    (net (code "501") (name "/ROW_DIN15_FPGA") (class "Default")
      (node (ref "FMC HPC1") (pin "F5") (pinfunction "HA00_N_CC_F5") (pintype "passive"))
    )
    (net (code "503") (name "/ROW_DIN16_FPGA") (class "Default")
      (node (ref "FMC HPC1") (pin "F4") (pinfunction "HA00_P_CC_F4") (pintype "passive"))
    )
    (net (code "504") (name "/SCLKSerDes") (class "Default")
      (node (ref "FMC HPC1") (pin "K23") (pinfunction "HA23_N_K23") (pintype "passive"))
    )
    (net (code "505") (name "/SI1") (class "Default")
      (node (ref "FMC HPC1") (pin "K22") (pinfunction "HA23_P_K22") (pintype "passive"))
    )
    (net (code "506") (name "/SI2") (class "Default")
      (node (ref "FMC HPC1") (pin "K14") (pinfunction "HA10_N_K14") (pintype "passive"))
    )
    (net (code "507") (name "/SO1") (class "Default")
      (node (ref "FMC HPC1") (pin "K20") (pinfunction "HA21_N_K20") (pintype "passive"))
    )
    (net (code "508") (name "/SO2") (class "Default")
      (node (ref "FMC HPC1") (pin "K13") (pinfunction "HA10_P_K13") (pintype "passive"))
    )
    (net (code "510") (name "/SW_SCLK_FPGA") (class "Default")
      (node (ref "FMC HPC1") (pin "F16") (pinfunction "HA15_P_F16") (pintype "passive"))
    )
    (net (code "512") (name "/SW_~{RESET}_FPGA") (class "Default")
      (node (ref "FMC HPC1") (pin "F19") (pinfunction "HA19_P_F19") (pintype "passive"))
    )
    (net (code "514") (name "/SW_~{SYNC}_FPGA") (class "Default")
      (node (ref "FMC HPC1") (pin "F17") (pinfunction "HA15_N_F17") (pintype "passive"))
    )
    (net (code "515") (name "/Select1") (class "Default")
      (node (ref "ICXTRAP1") (pin "C3") (pinfunction "SC4_C3") (pintype "passive"))
    )
    (net (code "516") (name "/Select2") (class "Default")
      (node (ref "ICXTRAP1") (pin "C5") (pinfunction "SC7_C5") (pintype "passive"))
    )
    (net (code "517") (name "/Select3") (class "Default")
      (node (ref "ICXTRAP1") (pin "D12") (pinfunction "SC3_D12") (pintype "passive"))
    )
    (net (code "518") (name "/Select4") (class "Default")
      (node (ref "ICXTRAP1") (pin "F12") (pinfunction "SC1_F12") (pintype "passive"))
    )
    (net (code "519") (name "/Select5") (class "Default")
      (node (ref "ICXTRAP1") (pin "G13") (pinfunction "SC6_G13") (pintype "passive"))
    )
    (net (code "520") (name "/Select6") (class "Default")
      (node (ref "ICXTRAP1") (pin "A17") (pinfunction "SC2_A17") (pintype "passive"))
    )
    (net (code "521") (name "/Select7") (class "Default")
      (node (ref "ICXTRAP1") (pin "B18") (pinfunction "SC5_B18") (pintype "passive"))
    )
    (net (code "522") (name "/Select8") (class "Default")
      (node (ref "ICXTRAP1") (pin "A19") (pinfunction "SC8_A19") (pintype "passive"))
    )
    (net (code "523") (name "/Select9") (class "Default")
      (node (ref "ICXTRAP1") (pin "C33") (pinfunction "SR13_C33") (pintype "passive"))
    )
    (net (code "524") (name "/Select10") (class "Default")
      (node (ref "ICXTRAP1") (pin "E33") (pinfunction "SR10_E33") (pintype "passive"))
    )
    (net (code "525") (name "/Select11") (class "Default")
      (node (ref "ICXTRAP1") (pin "M30") (pinfunction "SR14_M30") (pintype "passive"))
    )
    (net (code "526") (name "/Select12") (class "Default")
      (node (ref "ICXTRAP1") (pin "L31") (pinfunction "SR16_L31") (pintype "passive"))
    )
    (net (code "527") (name "/Select13") (class "Default")
      (node (ref "ICXTRAP1") (pin "M32") (pinfunction "SR11_M32") (pintype "passive"))
    )
    (net (code "528") (name "/Select14") (class "Default")
      (node (ref "ICXTRAP1") (pin "U35") (pinfunction "SR15_U35") (pintype "passive"))
    )
    (net (code "529") (name "/Select15") (class "Default")
      (node (ref "ICXTRAP1") (pin "V34") (pinfunction "SR12_V34") (pintype "passive"))
    )
    (net (code "530") (name "/Select16") (class "Default")
      (node (ref "ICXTRAP1") (pin "W35") (pinfunction "SR9_W35") (pintype "passive"))
    )
    (net (code "531") (name "/Select17") (class "Default")
      (node (ref "ICXTRAP1") (pin "J1") (pinfunction "SR8_J1") (pintype "passive"))
    )
    (net (code "532") (name "/Select18") (class "Default")
      (node (ref "ICXTRAP1") (pin "K2") (pinfunction "SR5_K2") (pintype "passive"))
    )
    (net (code "533") (name "/Select19") (class "Default")
      (node (ref "ICXTRAP1") (pin "L3") (pinfunction "SR2_L3") (pintype "passive"))
    )
    (net (code "534") (name "/Select20") (class "Default")
      (node (ref "ICXTRAP1") (pin "V4") (pinfunction "SR6_V4") (pintype "passive"))
    )
    (net (code "535") (name "/Select21") (class "Default")
      (node (ref "ICXTRAP1") (pin "V6") (pinfunction "SR3_V6") (pintype "passive"))
    )
    (net (code "536") (name "/Select22") (class "Default")
      (node (ref "ICXTRAP1") (pin "AG1") (pinfunction "SR1_AG1") (pintype "passive"))
    )
    (net (code "537") (name "/Select23") (class "Default")
      (node (ref "ICXTRAP1") (pin "AF2") (pinfunction "SR4_AF2") (pintype "passive"))
    )
    (net (code "538") (name "/Select24") (class "Default")
      (node (ref "ICXTRAP1") (pin "AE3") (pinfunction "SR7_AE3") (pintype "passive"))
    )
    (net (code "539") (name "/Select25") (class "Default")
      (node (ref "ICXTRAP1") (pin "AP12") (pinfunction "SC9_AP12") (pintype "passive"))
    )
    (net (code "540") (name "/Select26") (class "Default")
      (node (ref "ICXTRAP1") (pin "AR13") (pinfunction "SC15_AR13") (pintype "passive"))
    )
    (net (code "541") (name "/Select27") (class "Default")
      (node (ref "ICXTRAP1") (pin "AN13") (pinfunction "SC12_AN13") (pintype "passive"))
    )
    (net (code "542") (name "/Select28") (class "Default")
      (node (ref "ICXTRAP1") (pin "AM20") (pinfunction "SC11_AM20") (pintype "passive"))
    )
    (net (code "543") (name "/Select29") (class "Default")
      (node (ref "ICXTRAP1") (pin "AK20") (pinfunction "SC14_AK20") (pintype "passive"))
    )
    (net (code "544") (name "/Select30") (class "Default")
      (node (ref "ICXTRAP1") (pin "AN27") (pinfunction "SC10_AN27") (pintype "passive"))
    )
    (net (code "545") (name "/Select31") (class "Default")
      (node (ref "ICXTRAP1") (pin "AR29") (pinfunction "SC13_AR29") (pintype "passive"))
    )
    (net (code "546") (name "/Select32") (class "Default")
      (node (ref "ICXTRAP1") (pin "AR31") (pinfunction "SC16_AR31") (pintype "passive"))
    )
    (net (code "549") (name "/VDD1") (class "Default")
      (node (ref "ICXTRAP1") (pin "AD32") (pinfunction "VDD1_AD32") (pintype "passive"))
    )
    (net (code "550") (name "/VDD3") (class "Default")
      (node (ref "ICXTRAP1") (pin "F24") (pinfunction "VDD3_F24") (pintype "passive"))
    )
    (net (code "551") (name "/VDD_12V") (class "Default")
      (node (ref "C3") (pin "2") (pinfunction "2_2") (pintype "passive"))
      (node (ref "C4") (pin "2") (pinfunction "2_2") (pintype "passive"))
      (node (ref "S1") (pin "2") (pinfunction "NO_2") (pintype "passive"))
      (node (ref "TP1") (pin "1") (pinfunction "1_1") (pintype "passive"))
    )
    (net (code "555") (name "/VDDesd") (class "Default")
      (node (ref "ICXTRAP1") (pin "M6") (pinfunction "VDDesd_M6") (pintype "passive"))
    )
    (net (code "587") (name "/~{CS}") (class "Default")
      (node (ref "FMC HPC1") (pin "H20") (pinfunction "LA15_N_H20") (pintype "passive"))
    )
    (net (code "588") (name "/~{RST}") (class "Default")
      (node (ref "FMC HPC1") (pin "K7") (pinfunction "HA02_P_K7") (pintype "passive"))
    )
    (net (code "589") (name "GND") (class "Default")
      (node (ref "C1") (pin "1") (pinfunction "1_1") (pintype "passive"))
      (node (ref "C2") (pin "1") (pinfunction "1_1") (pintype "passive"))
      (node (ref "C3") (pin "1") (pinfunction "1_1") (pintype "passive"))
      (node (ref "C4") (pin "1") (pinfunction "1_1") (pintype "passive"))
      (node (ref "FMC HPC1") (pin "A1") (pinfunction "GND_A1") (pintype "passive"))
      (node (ref "FMC HPC1") (pin "A12") (pinfunction "GND_A12") (pintype "passive"))
      (node (ref "FMC HPC1") (pin "A13") (pinfunction "GND_A13") (pintype "passive"))
      (node (ref "FMC HPC1") (pin "A16") (pinfunction "GND_A16") (pintype "passive"))
      (node (ref "FMC HPC1") (pin "A17") (pinfunction "GND_A17") (pintype "passive"))
      (node (ref "FMC HPC1") (pin "A20") (pinfunction "GND_A20") (pintype "passive"))
      (node (ref "FMC HPC1") (pin "A21") (pinfunction "GND_A21") (pintype "passive"))
      (node (ref "FMC HPC1") (pin "A24") (pinfunction "GND_A24") (pintype "passive"))
      (node (ref "FMC HPC1") (pin "A25") (pinfunction "GND_A25") (pintype "passive"))
      (node (ref "FMC HPC1") (pin "A28") (pinfunction "GND_A28") (pintype "passive"))
      (node (ref "FMC HPC1") (pin "A29") (pinfunction "GND_A29") (pintype "passive"))
      (node (ref "FMC HPC1") (pin "A32") (pinfunction "GND_A32") (pintype "passive"))
      (node (ref "FMC HPC1") (pin "A33") (pinfunction "GND_A33") (pintype "passive"))
      (node (ref "FMC HPC1") (pin "A36") (pinfunction "GND_A36") (pintype "passive"))
      (node (ref "FMC HPC1") (pin "A37") (pinfunction "GND_A37") (pintype "passive"))
      (node (ref "FMC HPC1") (pin "A4") (pinfunction "GND_A4") (pintype "passive"))
      (node (ref "FMC HPC1") (pin "A40") (pinfunction "GND_A40") (pintype "passive"))
      (node (ref "FMC HPC1") (pin "A5") (pinfunction "GND_A5") (pintype "passive"))
      (node (ref "FMC HPC1") (pin "A8") (pinfunction "GND_A8") (pintype "passive"))
      (node (ref "FMC HPC1") (pin "A9") (pinfunction "GND_A9") (pintype "passive"))
      (node (ref "FMC HPC1") (pin "B10") (pinfunction "GND_B10") (pintype "passive"))
      (node (ref "FMC HPC1") (pin "B11") (pinfunction "GND_B11") (pintype "passive"))
      (node (ref "FMC HPC1") (pin "B14") (pinfunction "GND_B14") (pintype "passive"))
      (node (ref "FMC HPC1") (pin "B15") (pinfunction "GND_B15") (pintype "passive"))
      (node (ref "FMC HPC1") (pin "B18") (pinfunction "GND_B18") (pintype "passive"))
      (node (ref "FMC HPC1") (pin "B19") (pinfunction "GND_B19") (pintype "passive"))
      (node (ref "FMC HPC1") (pin "B2") (pinfunction "GND_B2") (pintype "passive"))
      (node (ref "FMC HPC1") (pin "B22") (pinfunction "GND_B22") (pintype "passive"))
      (node (ref "FMC HPC1") (pin "B23") (pinfunction "GND_B23") (pintype "passive"))
      (node (ref "FMC HPC1") (pin "B26") (pinfunction "GND_B26") (pintype "passive"))
      (node (ref "FMC HPC1") (pin "B27") (pinfunction "GND_B27") (pintype "passive"))
      (node (ref "FMC HPC1") (pin "B3") (pinfunction "GND_B3") (pintype "passive"))
      (node (ref "FMC HPC1") (pin "B30") (pinfunction "GND_B30") (pintype "passive"))
      (node (ref "FMC HPC1") (pin "B31") (pinfunction "GND_B31") (pintype "passive"))
      (node (ref "FMC HPC1") (pin "B34") (pinfunction "GND_B34") (pintype "passive"))
      (node (ref "FMC HPC1") (pin "B35") (pinfunction "GND_B35") (pintype "passive"))
      (node (ref "FMC HPC1") (pin "B38") (pinfunction "GND_B38") (pintype "passive"))
      (node (ref "FMC HPC1") (pin "B39") (pinfunction "GND_B39") (pintype "passive"))
      (node (ref "FMC HPC1") (pin "B6") (pinfunction "GND_B6") (pintype "passive"))
      (node (ref "FMC HPC1") (pin "B7") (pinfunction "GND_B7") (pintype "passive"))
      (node (ref "FMC HPC1") (pin "C1") (pinfunction "GND_C1") (pintype "passive"))
      (node (ref "FMC HPC1") (pin "C12") (pinfunction "GND_C12") (pintype "passive"))
      (node (ref "FMC HPC1") (pin "C13") (pinfunction "GND_C13") (pintype "passive"))
      (node (ref "FMC HPC1") (pin "C16") (pinfunction "GND_C16") (pintype "passive"))
      (node (ref "FMC HPC1") (pin "C17") (pinfunction "GND_C17") (pintype "passive"))
      (node (ref "FMC HPC1") (pin "C20") (pinfunction "GND_C20") (pintype "passive"))
      (node (ref "FMC HPC1") (pin "C21") (pinfunction "GND_C21") (pintype "passive"))
      (node (ref "FMC HPC1") (pin "C24") (pinfunction "GND_C24") (pintype "passive"))
      (node (ref "FMC HPC1") (pin "C25") (pinfunction "GND_C25") (pintype "passive"))
      (node (ref "FMC HPC1") (pin "C28") (pinfunction "GND_C28") (pintype "passive"))
      (node (ref "FMC HPC1") (pin "C29") (pinfunction "GND_C29") (pintype "passive"))
      (node (ref "FMC HPC1") (pin "C32") (pinfunction "GND_C32") (pintype "passive"))
      (node (ref "FMC HPC1") (pin "C33") (pinfunction "GND_C33") (pintype "passive"))
      (node (ref "FMC HPC1") (pin "C36") (pinfunction "GND_C36") (pintype "passive"))
      (node (ref "FMC HPC1") (pin "C38") (pinfunction "GND_C38") (pintype "passive"))
      (node (ref "FMC HPC1") (pin "C4") (pinfunction "GND_C4") (pintype "passive"))
      (node (ref "FMC HPC1") (pin "C40") (pinfunction "GND_C40") (pintype "passive"))
      (node (ref "FMC HPC1") (pin "C5") (pinfunction "GND_C5") (pintype "passive"))
      (node (ref "FMC HPC1") (pin "C8") (pinfunction "GND_C8") (pintype "passive"))
      (node (ref "FMC HPC1") (pin "C9") (pinfunction "GND_C9") (pintype "passive"))
      (node (ref "FMC HPC1") (pin "D10") (pinfunction "GND_D10") (pintype "passive"))
      (node (ref "FMC HPC1") (pin "D13") (pinfunction "GND_D13") (pintype "passive"))
      (node (ref "FMC HPC1") (pin "D16") (pinfunction "GND_D16") (pintype "passive"))
      (node (ref "FMC HPC1") (pin "D19") (pinfunction "GND_D19") (pintype "passive"))
      (node (ref "FMC HPC1") (pin "D2") (pinfunction "GND_D2") (pintype "passive"))
      (node (ref "FMC HPC1") (pin "D22") (pinfunction "GND_D22") (pintype "passive"))
      (node (ref "FMC HPC1") (pin "D25") (pinfunction "GND_D25") (pintype "passive"))
      (node (ref "FMC HPC1") (pin "D28") (pinfunction "GND_D28") (pintype "passive"))
      (node (ref "FMC HPC1") (pin "D3") (pinfunction "GND_D3") (pintype "passive"))
      (node (ref "FMC HPC1") (pin "D37") (pinfunction "GND_D37") (pintype "passive"))
      (node (ref "FMC HPC1") (pin "D39") (pinfunction "GND_D39") (pintype "passive"))
      (node (ref "FMC HPC1") (pin "D6") (pinfunction "GND_D6") (pintype "passive"))
      (node (ref "FMC HPC1") (pin "D7") (pinfunction "GND_D7") (pintype "passive"))
      (node (ref "FMC HPC1") (pin "E1") (pinfunction "GND_E1") (pintype "passive"))
      (node (ref "FMC HPC1") (pin "E11") (pinfunction "GND_E11") (pintype "passive"))
      (node (ref "FMC HPC1") (pin "E14") (pinfunction "GND_E14") (pintype "passive"))
      (node (ref "FMC HPC1") (pin "E17") (pinfunction "GND_E17") (pintype "passive"))
      (node (ref "FMC HPC1") (pin "E20") (pinfunction "GND_E20") (pintype "passive"))
      (node (ref "FMC HPC1") (pin "E23") (pinfunction "GND_E23") (pintype "passive"))
      (node (ref "FMC HPC1") (pin "E26") (pinfunction "GND_E26") (pintype "passive"))
      (node (ref "FMC HPC1") (pin "E29") (pinfunction "GND_E29") (pintype "passive"))
      (node (ref "FMC HPC1") (pin "E32") (pinfunction "GND_E32") (pintype "passive"))
      (node (ref "FMC HPC1") (pin "E35") (pinfunction "GND_E35") (pintype "passive"))
      (node (ref "FMC HPC1") (pin "E38") (pinfunction "GND_E38") (pintype "passive"))
      (node (ref "FMC HPC1") (pin "E4") (pinfunction "GND_E4") (pintype "passive"))
      (node (ref "FMC HPC1") (pin "E40") (pinfunction "GND_E40") (pintype "passive"))
      (node (ref "FMC HPC1") (pin "E5") (pinfunction "GND_E5") (pintype "passive"))
      (node (ref "FMC HPC1") (pin "E8") (pinfunction "GND_E8") (pintype "passive"))
      (node (ref "FMC HPC1") (pin "F12") (pinfunction "GND_F12") (pintype "passive"))
      (node (ref "FMC HPC1") (pin "F15") (pinfunction "GND_F15") (pintype "passive"))
      (node (ref "FMC HPC1") (pin "F18") (pinfunction "GND_F18") (pintype "passive"))
      (node (ref "FMC HPC1") (pin "F2") (pinfunction "GND_F2") (pintype "passive"))
      (node (ref "FMC HPC1") (pin "F21") (pinfunction "GND_F21") (pintype "passive"))
      (node (ref "FMC HPC1") (pin "F24") (pinfunction "GND_F24") (pintype "passive"))
      (node (ref "FMC HPC1") (pin "F27") (pinfunction "GND_F27") (pintype "passive"))
      (node (ref "FMC HPC1") (pin "F3") (pinfunction "GND_F3") (pintype "passive"))
      (node (ref "FMC HPC1") (pin "F30") (pinfunction "GND_F30") (pintype "passive"))
      (node (ref "FMC HPC1") (pin "F33") (pinfunction "GND_F33") (pintype "passive"))
      (node (ref "FMC HPC1") (pin "F36") (pinfunction "GND_F36") (pintype "passive"))
      (node (ref "FMC HPC1") (pin "F39") (pinfunction "GND_F39") (pintype "passive"))
      (node (ref "FMC HPC1") (pin "F6") (pinfunction "GND_F6") (pintype "passive"))
      (node (ref "FMC HPC1") (pin "F9") (pinfunction "GND_F9") (pintype "passive"))
      (node (ref "FMC HPC1") (pin "G1") (pinfunction "GND_G1") (pintype "passive"))
      (node (ref "FMC HPC1") (pin "G11") (pinfunction "GND_G11") (pintype "passive"))
      (node (ref "FMC HPC1") (pin "G14") (pinfunction "GND_G14") (pintype "passive"))
      (node (ref "FMC HPC1") (pin "G17") (pinfunction "GND_G17") (pintype "passive"))
      (node (ref "FMC HPC1") (pin "G20") (pinfunction "GND_G20") (pintype "passive"))
      (node (ref "FMC HPC1") (pin "G23") (pinfunction "GND_G23") (pintype "passive"))
      (node (ref "FMC HPC1") (pin "G26") (pinfunction "GND_G26") (pintype "passive"))
      (node (ref "FMC HPC1") (pin "G29") (pinfunction "GND_G29") (pintype "passive"))
      (node (ref "FMC HPC1") (pin "G32") (pinfunction "GND_G32") (pintype "passive"))
      (node (ref "FMC HPC1") (pin "G35") (pinfunction "GND_G35") (pintype "passive"))
      (node (ref "FMC HPC1") (pin "G38") (pinfunction "GND_G38") (pintype "passive"))
      (node (ref "FMC HPC1") (pin "G4") (pinfunction "GND_G4") (pintype "passive"))
      (node (ref "FMC HPC1") (pin "G40") (pinfunction "GND_G40") (pintype "passive"))
      (node (ref "FMC HPC1") (pin "G5") (pinfunction "GND_G5") (pintype "passive"))
      (node (ref "FMC HPC1") (pin "G8") (pinfunction "GND_G8") (pintype "passive"))
      (node (ref "FMC HPC1") (pin "H12") (pinfunction "GND_H12") (pintype "passive"))
      (node (ref "FMC HPC1") (pin "H15") (pinfunction "GND_H15") (pintype "passive"))
      (node (ref "FMC HPC1") (pin "H18") (pinfunction "GND_H18") (pintype "passive"))
      (node (ref "FMC HPC1") (pin "H21") (pinfunction "GND_H21") (pintype "passive"))
      (node (ref "FMC HPC1") (pin "H24") (pinfunction "GND_H24") (pintype "passive"))
      (node (ref "FMC HPC1") (pin "H27") (pinfunction "GND_H27") (pintype "passive"))
      (node (ref "FMC HPC1") (pin "H3") (pinfunction "GND_H3") (pintype "passive"))
      (node (ref "FMC HPC1") (pin "H30") (pinfunction "GND_H30") (pintype "passive"))
      (node (ref "FMC HPC1") (pin "H33") (pinfunction "GND_H33") (pintype "passive"))
      (node (ref "FMC HPC1") (pin "H36") (pinfunction "GND_H36") (pintype "passive"))
      (node (ref "FMC HPC1") (pin "H39") (pinfunction "GND_H39") (pintype "passive"))
      (node (ref "FMC HPC1") (pin "H6") (pinfunction "GND_H6") (pintype "passive"))
      (node (ref "FMC HPC1") (pin "H9") (pinfunction "GND_H9") (pintype "passive"))
      (node (ref "FMC HPC1") (pin "J1") (pinfunction "GND_J1") (pintype "passive"))
      (node (ref "FMC HPC1") (pin "J11") (pinfunction "GND_J11") (pintype "passive"))
      (node (ref "FMC HPC1") (pin "J14") (pinfunction "GND_J14") (pintype "passive"))
      (node (ref "FMC HPC1") (pin "J17") (pinfunction "GND_J17") (pintype "passive"))
      (node (ref "FMC HPC1") (pin "J20") (pinfunction "GND_J20") (pintype "passive"))
      (node (ref "FMC HPC1") (pin "J23") (pinfunction "GND_J23") (pintype "passive"))
      (node (ref "FMC HPC1") (pin "J26") (pinfunction "GND_J26") (pintype "passive"))
      (node (ref "FMC HPC1") (pin "J29") (pinfunction "GND_J29") (pintype "passive"))
      (node (ref "FMC HPC1") (pin "J32") (pinfunction "GND_J32") (pintype "passive"))
      (node (ref "FMC HPC1") (pin "J35") (pinfunction "GND_J35") (pintype "passive"))
      (node (ref "FMC HPC1") (pin "J38") (pinfunction "GND_J38") (pintype "passive"))
      (node (ref "FMC HPC1") (pin "J4") (pinfunction "GND_J4") (pintype "passive"))
      (node (ref "FMC HPC1") (pin "J40") (pinfunction "GND_J40") (pintype "passive"))
      (node (ref "FMC HPC1") (pin "J5") (pinfunction "GND_J5") (pintype "passive"))
      (node (ref "FMC HPC1") (pin "J8") (pinfunction "GND_J8") (pintype "passive"))
      (node (ref "FMC HPC1") (pin "K12") (pinfunction "GND_K12") (pintype "passive"))
      (node (ref "FMC HPC1") (pin "K15") (pinfunction "GND_K15") (pintype "passive"))
      (node (ref "FMC HPC1") (pin "K18") (pinfunction "GND_K18") (pintype "passive"))
      (node (ref "FMC HPC1") (pin "K2") (pinfunction "GND_K2") (pintype "passive"))
      (node (ref "FMC HPC1") (pin "K21") (pinfunction "GND_K21") (pintype "passive"))
      (node (ref "FMC HPC1") (pin "K24") (pinfunction "GND_K24") (pintype "passive"))
      (node (ref "FMC HPC1") (pin "K27") (pinfunction "GND_K27") (pintype "passive"))
      (node (ref "FMC HPC1") (pin "K3") (pinfunction "GND_K3") (pintype "passive"))
      (node (ref "FMC HPC1") (pin "K30") (pinfunction "GND_K30") (pintype "passive"))
      (node (ref "FMC HPC1") (pin "K33") (pinfunction "GND_K33") (pintype "passive"))
      (node (ref "FMC HPC1") (pin "K36") (pinfunction "GND_K36") (pintype "passive"))
      (node (ref "FMC HPC1") (pin "K39") (pinfunction "GND_K39") (pintype "passive"))
      (node (ref "FMC HPC1") (pin "K6") (pinfunction "GND_K6") (pintype "passive"))
      (node (ref "FMC HPC1") (pin "K9") (pinfunction "GND_K9") (pintype "passive"))
      (node (ref "ICXTRAP1") (pin "AK12") (pinfunction "VSS_AK12") (pintype "passive"))
      (node (ref "JP1") (pin "3") (pinfunction "3_3") (pintype "passive"))
      (node (ref "JP1") (pin "4") (pinfunction "4_4") (pintype "passive"))
      (node (ref "MH1") (pin "1") (pinfunction "1_1") (pintype "passive"))
      (node (ref "MH2") (pin "1") (pinfunction "1_1") (pintype "passive"))
      (node (ref "MH3") (pin "1") (pinfunction "1_1") (pintype "passive"))
      (node (ref "MH4") (pin "1") (pinfunction "1_1") (pintype "passive"))
      (node (ref "POWER1") (pin "2") (pintype "power_in"))
      (node (ref "POWER1") (pin "3") (pinfunction "3_3") (pintype "power_in"))
      (node (ref "R1") (pin "1") (pinfunction "1_1") (pintype "passive"))
      (node (ref "R10") (pin "1") (pinfunction "1_1") (pintype "passive"))
      (node (ref "R100") (pin "1") (pinfunction "1_1") (pintype "passive"))
      (node (ref "R101") (pin "1") (pinfunction "1_1") (pintype "passive"))
      (node (ref "R102") (pin "1") (pinfunction "1_1") (pintype "passive"))
      (node (ref "R103") (pin "1") (pinfunction "1_1") (pintype "passive"))
      (node (ref "R104") (pin "1") (pinfunction "1_1") (pintype "passive"))
      (node (ref "R11") (pin "1") (pinfunction "1_1") (pintype "passive"))
      (node (ref "R12") (pin "1") (pinfunction "1_1") (pintype "passive"))
      (node (ref "R13") (pin "1") (pinfunction "1_1") (pintype "passive"))
      (node (ref "R14") (pin "1") (pinfunction "1_1") (pintype "passive"))
      (node (ref "R15") (pin "1") (pinfunction "1_1") (pintype "passive"))
      (node (ref "R16") (pin "1") (pinfunction "1_1") (pintype "passive"))
      (node (ref "R17") (pin "1") (pinfunction "1_1") (pintype "passive"))
      (node (ref "R18") (pin "1") (pinfunction "1_1") (pintype "passive"))
      (node (ref "R19") (pin "1") (pinfunction "1_1") (pintype "passive"))
      (node (ref "R2") (pin "1") (pinfunction "1_1") (pintype "passive"))
      (node (ref "R20") (pin "1") (pinfunction "1_1") (pintype "passive"))
      (node (ref "R21") (pin "1") (pinfunction "1_1") (pintype "passive"))
      (node (ref "R22") (pin "1") (pinfunction "1_1") (pintype "passive"))
      (node (ref "R23") (pin "1") (pinfunction "1_1") (pintype "passive"))
      (node (ref "R24") (pin "1") (pinfunction "1_1") (pintype "passive"))
      (node (ref "R25") (pin "1") (pinfunction "1_1") (pintype "passive"))
      (node (ref "R26") (pin "1") (pinfunction "1_1") (pintype "passive"))
      (node (ref "R27") (pin "1") (pinfunction "1_1") (pintype "passive"))
      (node (ref "R28") (pin "1") (pinfunction "1_1") (pintype "passive"))
      (node (ref "R29") (pin "1") (pinfunction "1_1") (pintype "passive"))
      (node (ref "R3") (pin "1") (pinfunction "1_1") (pintype "passive"))
      (node (ref "R30") (pin "1") (pinfunction "1_1") (pintype "passive"))
      (node (ref "R31") (pin "1") (pinfunction "1_1") (pintype "passive"))
      (node (ref "R32") (pin "1") (pinfunction "1_1") (pintype "passive"))
      (node (ref "R33") (pin "1") (pinfunction "1_1") (pintype "passive"))
      (node (ref "R34") (pin "1") (pinfunction "1_1") (pintype "passive"))
      (node (ref "R35") (pin "1") (pinfunction "1_1") (pintype "passive"))
      (node (ref "R36") (pin "1") (pinfunction "1_1") (pintype "passive"))
      (node (ref "R37") (pin "1") (pinfunction "1_1") (pintype "passive"))
      (node (ref "R38") (pin "1") (pinfunction "1_1") (pintype "passive"))
      (node (ref "R39") (pin "1") (pinfunction "1_1") (pintype "passive"))
      (node (ref "R4") (pin "1") (pinfunction "1_1") (pintype "passive"))
      (node (ref "R40") (pin "1") (pinfunction "1_1") (pintype "passive"))
      (node (ref "R41") (pin "1") (pinfunction "1_1") (pintype "passive"))
      (node (ref "R42") (pin "1") (pinfunction "1_1") (pintype "passive"))
      (node (ref "R43") (pin "1") (pinfunction "1_1") (pintype "passive"))
      (node (ref "R44") (pin "1") (pinfunction "1_1") (pintype "passive"))
      (node (ref "R45") (pin "1") (pinfunction "1_1") (pintype "passive"))
      (node (ref "R46") (pin "1") (pinfunction "1_1") (pintype "passive"))
      (node (ref "R47") (pin "1") (pinfunction "1_1") (pintype "passive"))
      (node (ref "R48") (pin "1") (pinfunction "1_1") (pintype "passive"))
      (node (ref "R49") (pin "1") (pinfunction "1_1") (pintype "passive"))
      (node (ref "R5") (pin "1") (pinfunction "1_1") (pintype "passive"))
      (node (ref "R50") (pin "1") (pinfunction "1_1") (pintype "passive"))
      (node (ref "R51") (pin "1") (pinfunction "1_1") (pintype "passive"))
      (node (ref "R52") (pin "1") (pinfunction "1_1") (pintype "passive"))
      (node (ref "R53") (pin "1") (pinfunction "1_1") (pintype "passive"))
      (node (ref "R54") (pin "1") (pinfunction "1_1") (pintype "passive"))
      (node (ref "R55") (pin "1") (pinfunction "1_1") (pintype "passive"))
      (node (ref "R56") (pin "1") (pinfunction "1_1") (pintype "passive"))
      (node (ref "R57") (pin "1") (pinfunction "1_1") (pintype "passive"))
      (node (ref "R58") (pin "1") (pinfunction "1_1") (pintype "passive"))
      (node (ref "R59") (pin "1") (pinfunction "1_1") (pintype "passive"))
      (node (ref "R6") (pin "1") (pinfunction "1_1") (pintype "passive"))
      (node (ref "R60") (pin "1") (pinfunction "1_1") (pintype "passive"))
      (node (ref "R61") (pin "1") (pinfunction "1_1") (pintype "passive"))
      (node (ref "R62") (pin "1") (pinfunction "1_1") (pintype "passive"))
      (node (ref "R63") (pin "1") (pinfunction "1_1") (pintype "passive"))
      (node (ref "R64") (pin "1") (pinfunction "1_1") (pintype "passive"))
      (node (ref "R65") (pin "1") (pinfunction "1_1") (pintype "passive"))
      (node (ref "R66") (pin "1") (pinfunction "1_1") (pintype "passive"))
      (node (ref "R67") (pin "1") (pinfunction "1_1") (pintype "passive"))
      (node (ref "R68") (pin "1") (pinfunction "1_1") (pintype "passive"))
      (node (ref "R69") (pin "1") (pinfunction "1_1") (pintype "passive"))
      (node (ref "R7") (pin "1") (pinfunction "1_1") (pintype "passive"))
      (node (ref "R70") (pin "1") (pinfunction "1_1") (pintype "passive"))
      (node (ref "R71") (pin "1") (pinfunction "1_1") (pintype "passive"))
      (node (ref "R72") (pin "1") (pinfunction "1_1") (pintype "passive"))
      (node (ref "R73") (pin "1") (pinfunction "1_1") (pintype "passive"))
      (node (ref "R74") (pin "1") (pinfunction "1_1") (pintype "passive"))
      (node (ref "R75") (pin "1") (pinfunction "1_1") (pintype "passive"))
      (node (ref "R76") (pin "1") (pinfunction "1_1") (pintype "passive"))
      (node (ref "R77") (pin "1") (pinfunction "1_1") (pintype "passive"))
      (node (ref "R78") (pin "1") (pinfunction "1_1") (pintype "passive"))
      (node (ref "R79") (pin "1") (pinfunction "1_1") (pintype "passive"))
      (node (ref "R8") (pin "1") (pinfunction "1_1") (pintype "passive"))
      (node (ref "R80") (pin "1") (pinfunction "1_1") (pintype "passive"))
      (node (ref "R81") (pin "1") (pinfunction "1_1") (pintype "passive"))
      (node (ref "R82") (pin "1") (pinfunction "1_1") (pintype "passive"))
      (node (ref "R83") (pin "1") (pinfunction "1_1") (pintype "passive"))
      (node (ref "R84") (pin "1") (pinfunction "1_1") (pintype "passive"))
      (node (ref "R85") (pin "1") (pinfunction "1_1") (pintype "passive"))
      (node (ref "R86") (pin "1") (pinfunction "1_1") (pintype "passive"))
      (node (ref "R87") (pin "1") (pinfunction "1_1") (pintype "passive"))
      (node (ref "R88") (pin "1") (pinfunction "1_1") (pintype "passive"))
      (node (ref "R89") (pin "1") (pinfunction "1_1") (pintype "passive"))
      (node (ref "R9") (pin "1") (pinfunction "1_1") (pintype "passive"))
      (node (ref "R90") (pin "1") (pinfunction "1_1") (pintype "passive"))
      (node (ref "R91") (pin "1") (pinfunction "1_1") (pintype "passive"))
      (node (ref "R92") (pin "1") (pinfunction "1_1") (pintype "passive"))
      (node (ref "R93") (pin "1") (pinfunction "1_1") (pintype "passive"))
      (node (ref "R94") (pin "1") (pinfunction "1_1") (pintype "passive"))
      (node (ref "R95") (pin "1") (pinfunction "1_1") (pintype "passive"))
      (node (ref "R96") (pin "1") (pinfunction "1_1") (pintype "passive"))
      (node (ref "R97") (pin "1") (pinfunction "1_1") (pintype "passive"))
      (node (ref "R98") (pin "1") (pinfunction "1_1") (pintype "passive"))
      (node (ref "R99") (pin "1") (pinfunction "1_1") (pintype "passive"))
    )
    (net (code "590") (name "Net-(JP2-Pad2)") (class "Default")
      (node (ref "JP2") (pin "2") (pinfunction "2_2") (pintype "passive"))
      (node (ref "R1") (pin "2") (pinfunction "2_2") (pintype "passive"))
    )
    (net (code "591") (name "Net-(JP3-Pad2)") (class "Default")
      (node (ref "JP3") (pin "2") (pinfunction "2_2") (pintype "passive"))
      (node (ref "R2") (pin "2") (pinfunction "2_2") (pintype "passive"))
    )
    (net (code "592") (name "Net-(JP4-Pad2)") (class "Default")
      (node (ref "JP4") (pin "2") (pinfunction "2_2") (pintype "passive"))
      (node (ref "R3") (pin "2") (pinfunction "2_2") (pintype "passive"))
    )
    (net (code "593") (name "Net-(JP5-Pad2)") (class "Default")
      (node (ref "JP5") (pin "2") (pinfunction "2_2") (pintype "passive"))
      (node (ref "R4") (pin "2") (pinfunction "2_2") (pintype "passive"))
    )
    (net (code "594") (name "Net-(JP6-Pad2)") (class "Default")
      (node (ref "JP6") (pin "2") (pinfunction "2_2") (pintype "passive"))
      (node (ref "R5") (pin "2") (pinfunction "2_2") (pintype "passive"))
    )
    (net (code "595") (name "Net-(JP7-Pad2)") (class "Default")
      (node (ref "JP7") (pin "2") (pinfunction "2_2") (pintype "passive"))
      (node (ref "R6") (pin "2") (pinfunction "2_2") (pintype "passive"))
    )
    (net (code "596") (name "Net-(JP8-Pad2)") (class "Default")
      (node (ref "JP8") (pin "2") (pinfunction "2_2") (pintype "passive"))
      (node (ref "R7") (pin "2") (pinfunction "2_2") (pintype "passive"))
    )
    (net (code "597") (name "Net-(JP9-Pad2)") (class "Default")
      (node (ref "JP9") (pin "2") (pinfunction "2_2") (pintype "passive"))
      (node (ref "R8") (pin "2") (pinfunction "2_2") (pintype "passive"))
    )
    (net (code "598") (name "Net-(JP10-Pad2)") (class "Default")
      (node (ref "JP10") (pin "2") (pinfunction "2_2") (pintype "passive"))
      (node (ref "R9") (pin "2") (pinfunction "2_2") (pintype "passive"))
    )
    (net (code "599") (name "Net-(JP11-Pad2)") (class "Default")
      (node (ref "JP11") (pin "2") (pinfunction "2_2") (pintype "passive"))
      (node (ref "R10") (pin "2") (pinfunction "2_2") (pintype "passive"))
    )
    (net (code "600") (name "Net-(JP12-Pad2)") (class "Default")
      (node (ref "JP12") (pin "2") (pinfunction "2_2") (pintype "passive"))
      (node (ref "R11") (pin "2") (pinfunction "2_2") (pintype "passive"))
    )
    (net (code "601") (name "Net-(JP13-Pad2)") (class "Default")
      (node (ref "JP13") (pin "2") (pinfunction "2_2") (pintype "passive"))
      (node (ref "R12") (pin "2") (pinfunction "2_2") (pintype "passive"))
    )
    (net (code "602") (name "Net-(JP14-Pad2)") (class "Default")
      (node (ref "JP14") (pin "2") (pinfunction "2_2") (pintype "passive"))
      (node (ref "R13") (pin "2") (pinfunction "2_2") (pintype "passive"))
    )
    (net (code "603") (name "Net-(JP15-Pad2)") (class "Default")
      (node (ref "JP15") (pin "2") (pinfunction "2_2") (pintype "passive"))
      (node (ref "R14") (pin "2") (pinfunction "2_2") (pintype "passive"))
    )
    (net (code "604") (name "Net-(JP16-Pad2)") (class "Default")
      (node (ref "JP16") (pin "2") (pinfunction "2_2") (pintype "passive"))
      (node (ref "R15") (pin "2") (pinfunction "2_2") (pintype "passive"))
    )
    (net (code "605") (name "Net-(JP17-Pad2)") (class "Default")
      (node (ref "JP17") (pin "2") (pinfunction "2_2") (pintype "passive"))
      (node (ref "R16") (pin "2") (pinfunction "2_2") (pintype "passive"))
    )
    (net (code "606") (name "Net-(JP18-Pad2)") (class "Default")
      (node (ref "JP18") (pin "2") (pinfunction "2_2") (pintype "passive"))
      (node (ref "R17") (pin "2") (pinfunction "2_2") (pintype "passive"))
    )
    (net (code "607") (name "Net-(JP19-Pad2)") (class "Default")
      (node (ref "JP19") (pin "2") (pinfunction "2_2") (pintype "passive"))
      (node (ref "R18") (pin "2") (pinfunction "2_2") (pintype "passive"))
    )
    (net (code "608") (name "Net-(JP20-Pad2)") (class "Default")
      (node (ref "JP20") (pin "2") (pinfunction "2_2") (pintype "passive"))
      (node (ref "R19") (pin "2") (pinfunction "2_2") (pintype "passive"))
    )
    (net (code "609") (name "Net-(JP21-Pad2)") (class "Default")
      (node (ref "JP21") (pin "2") (pinfunction "2_2") (pintype "passive"))
      (node (ref "R20") (pin "2") (pinfunction "2_2") (pintype "passive"))
    )
    (net (code "610") (name "Net-(JP22-Pad2)") (class "Default")
      (node (ref "JP22") (pin "2") (pinfunction "2_2") (pintype "passive"))
      (node (ref "R21") (pin "2") (pinfunction "2_2") (pintype "passive"))
    )
    (net (code "611") (name "Net-(JP23-Pad2)") (class "Default")
      (node (ref "JP23") (pin "2") (pinfunction "2_2") (pintype "passive"))
      (node (ref "R22") (pin "2") (pinfunction "2_2") (pintype "passive"))
    )
    (net (code "612") (name "Net-(JP24-Pad2)") (class "Default")
      (node (ref "JP24") (pin "2") (pinfunction "2_2") (pintype "passive"))
      (node (ref "R23") (pin "2") (pinfunction "2_2") (pintype "passive"))
    )
    (net (code "613") (name "Net-(JP25-Pad2)") (class "Default")
      (node (ref "JP25") (pin "2") (pinfunction "2_2") (pintype "passive"))
      (node (ref "R24") (pin "2") (pinfunction "2_2") (pintype "passive"))
    )
    (net (code "614") (name "Net-(JP26-Pad2)") (class "Default")
      (node (ref "JP26") (pin "2") (pinfunction "2_2") (pintype "passive"))
      (node (ref "R25") (pin "2") (pinfunction "2_2") (pintype "passive"))
    )
    (net (code "615") (name "Net-(JP27-Pad2)") (class "Default")
      (node (ref "JP27") (pin "2") (pinfunction "2_2") (pintype "passive"))
      (node (ref "R26") (pin "2") (pinfunction "2_2") (pintype "passive"))
    )
    (net (code "616") (name "Net-(JP28-Pad2)") (class "Default")
      (node (ref "JP28") (pin "2") (pinfunction "2_2") (pintype "passive"))
      (node (ref "R27") (pin "2") (pinfunction "2_2") (pintype "passive"))
    )
    (net (code "617") (name "Net-(JP29-Pad2)") (class "Default")
      (node (ref "JP29") (pin "2") (pinfunction "2_2") (pintype "passive"))
      (node (ref "R28") (pin "2") (pinfunction "2_2") (pintype "passive"))
    )
    (net (code "618") (name "Net-(JP30-Pad2)") (class "Default")
      (node (ref "JP30") (pin "2") (pinfunction "2_2") (pintype "passive"))
      (node (ref "R29") (pin "2") (pinfunction "2_2") (pintype "passive"))
    )
    (net (code "619") (name "Net-(JP31-Pad2)") (class "Default")
      (node (ref "JP31") (pin "2") (pinfunction "2_2") (pintype "passive"))
      (node (ref "R30") (pin "2") (pinfunction "2_2") (pintype "passive"))
    )
    (net (code "620") (name "Net-(JP32-Pad2)") (class "Default")
      (node (ref "JP32") (pin "2") (pinfunction "2_2") (pintype "passive"))
      (node (ref "R31") (pin "2") (pinfunction "2_2") (pintype "passive"))
    )
    (net (code "621") (name "Net-(JP33-Pad2)") (class "Default")
      (node (ref "JP33") (pin "2") (pinfunction "2_2") (pintype "passive"))
      (node (ref "R32") (pin "2") (pinfunction "2_2") (pintype "passive"))
    )
    (net (code "622") (name "Net-(JP34-Pad2)") (class "Default")
      (node (ref "JP34") (pin "2") (pinfunction "2_2") (pintype "passive"))
      (node (ref "R33") (pin "2") (pinfunction "2_2") (pintype "passive"))
    )
    (net (code "623") (name "Net-(JP35-Pad2)") (class "Default")
      (node (ref "JP35") (pin "2") (pinfunction "2_2") (pintype "passive"))
      (node (ref "R34") (pin "2") (pinfunction "2_2") (pintype "passive"))
    )
    (net (code "624") (name "Net-(JP36-Pad2)") (class "Default")
      (node (ref "JP36") (pin "2") (pinfunction "2_2") (pintype "passive"))
      (node (ref "R35") (pin "2") (pinfunction "2_2") (pintype "passive"))
    )
    (net (code "625") (name "Net-(JP37-Pad2)") (class "Default")
      (node (ref "JP37") (pin "2") (pinfunction "2_2") (pintype "passive"))
      (node (ref "R36") (pin "2") (pinfunction "2_2") (pintype "passive"))
    )
    (net (code "626") (name "Net-(JP38-Pad2)") (class "Default")
      (node (ref "JP38") (pin "2") (pinfunction "2_2") (pintype "passive"))
      (node (ref "R37") (pin "2") (pinfunction "2_2") (pintype "passive"))
    )
    (net (code "627") (name "Net-(JP39-Pad2)") (class "Default")
      (node (ref "JP39") (pin "2") (pinfunction "2_2") (pintype "passive"))
      (node (ref "R38") (pin "2") (pinfunction "2_2") (pintype "passive"))
    )
    (net (code "628") (name "Net-(JP40-Pad2)") (class "Default")
      (node (ref "JP40") (pin "2") (pinfunction "2_2") (pintype "passive"))
      (node (ref "R39") (pin "2") (pinfunction "2_2") (pintype "passive"))
    )
    (net (code "629") (name "Net-(JP41-Pad2)") (class "Default")
      (node (ref "JP41") (pin "2") (pinfunction "2_2") (pintype "passive"))
      (node (ref "R40") (pin "2") (pinfunction "2_2") (pintype "passive"))
    )
    (net (code "630") (name "Net-(JP42-Pad2)") (class "Default")
      (node (ref "JP42") (pin "2") (pinfunction "2_2") (pintype "passive"))
      (node (ref "R41") (pin "2") (pinfunction "2_2") (pintype "passive"))
    )
    (net (code "631") (name "Net-(JP43-Pad2)") (class "Default")
      (node (ref "JP43") (pin "2") (pinfunction "2_2") (pintype "passive"))
      (node (ref "R42") (pin "2") (pinfunction "2_2") (pintype "passive"))
    )
    (net (code "632") (name "Net-(JP44-Pad2)") (class "Default")
      (node (ref "JP44") (pin "2") (pinfunction "2_2") (pintype "passive"))
      (node (ref "R43") (pin "2") (pinfunction "2_2") (pintype "passive"))
    )
    (net (code "633") (name "Net-(JP45-Pad2)") (class "Default")
      (node (ref "JP45") (pin "2") (pinfunction "2_2") (pintype "passive"))
      (node (ref "R44") (pin "2") (pinfunction "2_2") (pintype "passive"))
    )
    (net (code "634") (name "Net-(JP46-Pad2)") (class "Default")
      (node (ref "JP46") (pin "2") (pinfunction "2_2") (pintype "passive"))
      (node (ref "R45") (pin "2") (pinfunction "2_2") (pintype "passive"))
    )
    (net (code "635") (name "Net-(JP47-Pad2)") (class "Default")
      (node (ref "JP47") (pin "2") (pinfunction "2_2") (pintype "passive"))
      (node (ref "R46") (pin "2") (pinfunction "2_2") (pintype "passive"))
    )
    (net (code "636") (name "Net-(JP48-Pad2)") (class "Default")
      (node (ref "JP48") (pin "2") (pinfunction "2_2") (pintype "passive"))
      (node (ref "R47") (pin "2") (pinfunction "2_2") (pintype "passive"))
    )
    (net (code "637") (name "Net-(JP49-Pad2)") (class "Default")
      (node (ref "JP49") (pin "2") (pinfunction "2_2") (pintype "passive"))
      (node (ref "R48") (pin "2") (pinfunction "2_2") (pintype "passive"))
    )
    (net (code "638") (name "Net-(JP50-Pad2)") (class "Default")
      (node (ref "JP50") (pin "2") (pinfunction "2_2") (pintype "passive"))
      (node (ref "R49") (pin "2") (pinfunction "2_2") (pintype "passive"))
    )
    (net (code "639") (name "Net-(JP51-Pad2)") (class "Default")
      (node (ref "JP51") (pin "2") (pinfunction "2_2") (pintype "passive"))
      (node (ref "R50") (pin "2") (pinfunction "2_2") (pintype "passive"))
    )
    (net (code "640") (name "Net-(JP52-Pad2)") (class "Default")
      (node (ref "JP52") (pin "2") (pinfunction "2_2") (pintype "passive"))
      (node (ref "R51") (pin "2") (pinfunction "2_2") (pintype "passive"))
    )
    (net (code "641") (name "Net-(JP53-Pad2)") (class "Default")
      (node (ref "JP53") (pin "2") (pinfunction "2_2") (pintype "passive"))
      (node (ref "R52") (pin "2") (pinfunction "2_2") (pintype "passive"))
    )
    (net (code "642") (name "Net-(JP54-Pad2)") (class "Default")
      (node (ref "JP54") (pin "2") (pinfunction "2_2") (pintype "passive"))
      (node (ref "R53") (pin "2") (pinfunction "2_2") (pintype "passive"))
    )
    (net (code "643") (name "Net-(JP55-Pad2)") (class "Default")
      (node (ref "JP55") (pin "2") (pinfunction "2_2") (pintype "passive"))
      (node (ref "R54") (pin "2") (pinfunction "2_2") (pintype "passive"))
    )
    (net (code "644") (name "Net-(JP56-Pad2)") (class "Default")
      (node (ref "JP56") (pin "2") (pinfunction "2_2") (pintype "passive"))
      (node (ref "R55") (pin "2") (pinfunction "2_2") (pintype "passive"))
    )
    (net (code "645") (name "Net-(JP57-Pad2)") (class "Default")
      (node (ref "JP57") (pin "2") (pinfunction "2_2") (pintype "passive"))
      (node (ref "R56") (pin "2") (pinfunction "2_2") (pintype "passive"))
    )
    (net (code "646") (name "Net-(JP58-Pad2)") (class "Default")
      (node (ref "JP58") (pin "2") (pinfunction "2_2") (pintype "passive"))
      (node (ref "R57") (pin "2") (pinfunction "2_2") (pintype "passive"))
    )
    (net (code "647") (name "Net-(JP59-Pad2)") (class "Default")
      (node (ref "JP59") (pin "2") (pinfunction "2_2") (pintype "passive"))
      (node (ref "R58") (pin "2") (pinfunction "2_2") (pintype "passive"))
    )
    (net (code "648") (name "Net-(JP60-Pad2)") (class "Default")
      (node (ref "JP60") (pin "2") (pinfunction "2_2") (pintype "passive"))
      (node (ref "R59") (pin "2") (pinfunction "2_2") (pintype "passive"))
    )
    (net (code "649") (name "Net-(JP61-Pad2)") (class "Default")
      (node (ref "JP61") (pin "2") (pinfunction "2_2") (pintype "passive"))
      (node (ref "R60") (pin "2") (pinfunction "2_2") (pintype "passive"))
    )
    (net (code "650") (name "Net-(JP62-Pad2)") (class "Default")
      (node (ref "JP62") (pin "2") (pinfunction "2_2") (pintype "passive"))
      (node (ref "R61") (pin "2") (pinfunction "2_2") (pintype "passive"))
    )
    (net (code "651") (name "Net-(JP63-Pad2)") (class "Default")
      (node (ref "JP63") (pin "2") (pinfunction "2_2") (pintype "passive"))
      (node (ref "R62") (pin "2") (pinfunction "2_2") (pintype "passive"))
    )
    (net (code "652") (name "Net-(JP64-Pad2)") (class "Default")
      (node (ref "JP64") (pin "2") (pinfunction "2_2") (pintype "passive"))
      (node (ref "R63") (pin "2") (pinfunction "2_2") (pintype "passive"))
    )
    (net (code "653") (name "Net-(JP65-Pad2)") (class "Default")
      (node (ref "JP65") (pin "2") (pinfunction "2_2") (pintype "passive"))
      (node (ref "R64") (pin "2") (pinfunction "2_2") (pintype "passive"))
    )
    (net (code "654") (name "Net-(JP66-Pad2)") (class "Default")
      (node (ref "JP66") (pin "2") (pinfunction "2_2") (pintype "passive"))
      (node (ref "R65") (pin "2") (pinfunction "2_2") (pintype "passive"))
    )
    (net (code "655") (name "Net-(JP67-Pad2)") (class "Default")
      (node (ref "JP67") (pin "2") (pinfunction "2_2") (pintype "passive"))
      (node (ref "R66") (pin "2") (pinfunction "2_2") (pintype "passive"))
    )
    (net (code "656") (name "Net-(JP68-Pad2)") (class "Default")
      (node (ref "JP68") (pin "2") (pinfunction "2_2") (pintype "passive"))
      (node (ref "R67") (pin "2") (pinfunction "2_2") (pintype "passive"))
    )
    (net (code "657") (name "Net-(JP69-Pad2)") (class "Default")
      (node (ref "JP69") (pin "2") (pinfunction "2_2") (pintype "passive"))
      (node (ref "R68") (pin "2") (pinfunction "2_2") (pintype "passive"))
    )
    (net (code "658") (name "Net-(JP70-Pad2)") (class "Default")
      (node (ref "JP70") (pin "2") (pinfunction "2_2") (pintype "passive"))
      (node (ref "R69") (pin "2") (pinfunction "2_2") (pintype "passive"))
    )
    (net (code "659") (name "Net-(JP71-Pad2)") (class "Default")
      (node (ref "JP71") (pin "2") (pinfunction "2_2") (pintype "passive"))
      (node (ref "R70") (pin "2") (pinfunction "2_2") (pintype "passive"))
    )
    (net (code "660") (name "Net-(JP72-Pad2)") (class "Default")
      (node (ref "JP72") (pin "2") (pinfunction "2_2") (pintype "passive"))
      (node (ref "R71") (pin "2") (pinfunction "2_2") (pintype "passive"))
    )
    (net (code "661") (name "Net-(JP73-Pad2)") (class "Default")
      (node (ref "JP73") (pin "2") (pinfunction "2_2") (pintype "passive"))
      (node (ref "R72") (pin "2") (pinfunction "2_2") (pintype "passive"))
    )
    (net (code "662") (name "Net-(JP74-Pad2)") (class "Default")
      (node (ref "JP74") (pin "2") (pinfunction "2_2") (pintype "passive"))
      (node (ref "R73") (pin "2") (pinfunction "2_2") (pintype "passive"))
    )
    (net (code "663") (name "Net-(JP75-Pad2)") (class "Default")
      (node (ref "JP75") (pin "2") (pinfunction "2_2") (pintype "passive"))
      (node (ref "R74") (pin "2") (pinfunction "2_2") (pintype "passive"))
    )
    (net (code "664") (name "Net-(JP76-Pad2)") (class "Default")
      (node (ref "JP76") (pin "2") (pinfunction "2_2") (pintype "passive"))
      (node (ref "R75") (pin "2") (pinfunction "2_2") (pintype "passive"))
    )
    (net (code "665") (name "Net-(JP77-Pad2)") (class "Default")
      (node (ref "JP77") (pin "2") (pinfunction "2_2") (pintype "passive"))
      (node (ref "R76") (pin "2") (pinfunction "2_2") (pintype "passive"))
    )
    (net (code "666") (name "Net-(JP78-Pad2)") (class "Default")
      (node (ref "JP78") (pin "2") (pinfunction "2_2") (pintype "passive"))
      (node (ref "R77") (pin "2") (pinfunction "2_2") (pintype "passive"))
    )
    (net (code "667") (name "Net-(JP79-Pad2)") (class "Default")
      (node (ref "JP79") (pin "2") (pinfunction "2_2") (pintype "passive"))
      (node (ref "R78") (pin "2") (pinfunction "2_2") (pintype "passive"))
    )
    (net (code "668") (name "Net-(JP80-Pad2)") (class "Default")
      (node (ref "JP80") (pin "2") (pinfunction "2_2") (pintype "passive"))
      (node (ref "R79") (pin "2") (pinfunction "2_2") (pintype "passive"))
    )
    (net (code "669") (name "Net-(JP81-Pad2)") (class "Default")
      (node (ref "JP81") (pin "2") (pinfunction "2_2") (pintype "passive"))
      (node (ref "R80") (pin "2") (pinfunction "2_2") (pintype "passive"))
    )
    (net (code "670") (name "Net-(JP82-Pad2)") (class "Default")
      (node (ref "JP82") (pin "2") (pinfunction "2_2") (pintype "passive"))
      (node (ref "R81") (pin "2") (pinfunction "2_2") (pintype "passive"))
    )
    (net (code "671") (name "Net-(JP83-Pad2)") (class "Default")
      (node (ref "JP83") (pin "2") (pinfunction "2_2") (pintype "passive"))
      (node (ref "R82") (pin "2") (pinfunction "2_2") (pintype "passive"))
    )
    (net (code "672") (name "Net-(JP84-Pad2)") (class "Default")
      (node (ref "JP84") (pin "2") (pinfunction "2_2") (pintype "passive"))
      (node (ref "R83") (pin "2") (pinfunction "2_2") (pintype "passive"))
    )
    (net (code "673") (name "Net-(JP85-Pad2)") (class "Default")
      (node (ref "JP85") (pin "2") (pinfunction "2_2") (pintype "passive"))
      (node (ref "R84") (pin "2") (pinfunction "2_2") (pintype "passive"))
    )
    (net (code "674") (name "Net-(JP86-Pad2)") (class "Default")
      (node (ref "JP86") (pin "2") (pinfunction "2_2") (pintype "passive"))
      (node (ref "R85") (pin "2") (pinfunction "2_2") (pintype "passive"))
    )
    (net (code "675") (name "Net-(JP87-Pad2)") (class "Default")
      (node (ref "JP87") (pin "2") (pinfunction "2_2") (pintype "passive"))
      (node (ref "R86") (pin "2") (pinfunction "2_2") (pintype "passive"))
    )
    (net (code "676") (name "Net-(JP88-Pad2)") (class "Default")
      (node (ref "JP88") (pin "2") (pinfunction "2_2") (pintype "passive"))
      (node (ref "R87") (pin "2") (pinfunction "2_2") (pintype "passive"))
    )
    (net (code "677") (name "Net-(JP89-Pad2)") (class "Default")
      (node (ref "JP89") (pin "2") (pinfunction "2_2") (pintype "passive"))
      (node (ref "R88") (pin "2") (pinfunction "2_2") (pintype "passive"))
    )
    (net (code "678") (name "Net-(JP90-Pad2)") (class "Default")
      (node (ref "JP90") (pin "2") (pinfunction "2_2") (pintype "passive"))
      (node (ref "R89") (pin "2") (pinfunction "2_2") (pintype "passive"))
    )
    (net (code "679") (name "Net-(JP91-Pad2)") (class "Default")
      (node (ref "JP91") (pin "2") (pinfunction "2_2") (pintype "passive"))
      (node (ref "R90") (pin "2") (pinfunction "2_2") (pintype "passive"))
    )
    (net (code "680") (name "Net-(JP92-Pad2)") (class "Default")
      (node (ref "JP92") (pin "2") (pinfunction "2_2") (pintype "passive"))
      (node (ref "R91") (pin "2") (pinfunction "2_2") (pintype "passive"))
    )
    (net (code "681") (name "Net-(JP93-Pad2)") (class "Default")
      (node (ref "JP93") (pin "2") (pinfunction "2_2") (pintype "passive"))
      (node (ref "R92") (pin "2") (pinfunction "2_2") (pintype "passive"))
    )
    (net (code "682") (name "Net-(JP94-Pad2)") (class "Default")
      (node (ref "JP94") (pin "2") (pinfunction "2_2") (pintype "passive"))
      (node (ref "R93") (pin "2") (pinfunction "2_2") (pintype "passive"))
    )
    (net (code "683") (name "Net-(JP95-Pad2)") (class "Default")
      (node (ref "JP95") (pin "2") (pinfunction "2_2") (pintype "passive"))
      (node (ref "R94") (pin "2") (pinfunction "2_2") (pintype "passive"))
    )
    (net (code "684") (name "Net-(JP96-Pad2)") (class "Default")
      (node (ref "JP96") (pin "2") (pinfunction "2_2") (pintype "passive"))
      (node (ref "R95") (pin "2") (pinfunction "2_2") (pintype "passive"))
    )
    (net (code "685") (name "Net-(JP97-Pad2)") (class "Default")
      (node (ref "JP97") (pin "2") (pinfunction "2_2") (pintype "passive"))
      (node (ref "R96") (pin "2") (pinfunction "2_2") (pintype "passive"))
    )
    (net (code "686") (name "Net-(JP98-Pad2)") (class "Default")
      (node (ref "JP98") (pin "2") (pinfunction "2_2") (pintype "passive"))
      (node (ref "R97") (pin "2") (pinfunction "2_2") (pintype "passive"))
    )
    (net (code "687") (name "Net-(JP99-Pad2)") (class "Default")
      (node (ref "JP99") (pin "2") (pinfunction "2_2") (pintype "passive"))
      (node (ref "R98") (pin "2") (pinfunction "2_2") (pintype "passive"))
    )
    (net (code "688") (name "Net-(JP100-Pad2)") (class "Default")
      (node (ref "JP100") (pin "2") (pinfunction "2_2") (pintype "passive"))
      (node (ref "R99") (pin "2") (pinfunction "2_2") (pintype "passive"))
    )
    (net (code "689") (name "Net-(JP101-Pad2)") (class "Default")
      (node (ref "JP101") (pin "2") (pinfunction "2_2") (pintype "passive"))
      (node (ref "R100") (pin "2") (pinfunction "2_2") (pintype "passive"))
    )
    (net (code "690") (name "Net-(JP102-Pad2)") (class "Default")
      (node (ref "JP102") (pin "2") (pinfunction "2_2") (pintype "passive"))
      (node (ref "R101") (pin "2") (pinfunction "2_2") (pintype "passive"))
    )
    (net (code "691") (name "Net-(JP103-Pad2)") (class "Default")
      (node (ref "JP103") (pin "2") (pinfunction "2_2") (pintype "passive"))
      (node (ref "R102") (pin "2") (pinfunction "2_2") (pintype "passive"))
    )
    (net (code "692") (name "Net-(JP104-Pad2)") (class "Default")
      (node (ref "JP104") (pin "2") (pinfunction "2_2") (pintype "passive"))
      (node (ref "R103") (pin "2") (pinfunction "2_2") (pintype "passive"))
    )
    (net (code "693") (name "Net-(JP105-Pad2)") (class "Default")
      (node (ref "JP105") (pin "2") (pinfunction "2_2") (pintype "passive"))
      (node (ref "R104") (pin "2") (pinfunction "2_2") (pintype "passive"))
    )
    (net (code "694") (name "Net-(S1-COMMON)") (class "Default")
      (node (ref "C1") (pin "2") (pinfunction "2_2") (pintype "passive"))
      (node (ref "C2") (pin "2") (pinfunction "2_2") (pintype "passive"))
      (node (ref "JP1") (pin "1") (pinfunction "1_1") (pintype "passive"))
      (node (ref "JP1") (pin "2") (pinfunction "2_2") (pintype "passive"))
      (node (ref "POWER1") (pin "1") (pinfunction "1_1") (pintype "power_in"))
      (node (ref "S1") (pin "1") (pinfunction "COMMON_1") (pintype "passive"))
    )
    (net (code "695") (name "unconnected-(FMC HPC1A-CLK_DIR-PadB1)") (class "Default")
      (node (ref "FMC HPC1") (pin "B1") (pinfunction "CLK_DIR_B1") (pintype "passive+no_connect"))
    )
    (net (code "696") (name "unconnected-(FMC HPC1A-DP1_C2M_N-PadA23)") (class "Default")
      (node (ref "FMC HPC1") (pin "A23") (pinfunction "DP1_C2M_N_A23") (pintype "passive+no_connect"))
    )
    (net (code "697") (name "unconnected-(FMC HPC1A-DP1_C2M_P-PadA22)") (class "Default")
      (node (ref "FMC HPC1") (pin "A22") (pinfunction "DP1_C2M_P_A22") (pintype "passive+no_connect"))
    )
    (net (code "698") (name "unconnected-(FMC HPC1A-DP1_M2C_N-PadA3)") (class "Default")
      (node (ref "FMC HPC1") (pin "A3") (pinfunction "DP1_M2C_N_A3") (pintype "passive+no_connect"))
    )
    (net (code "699") (name "unconnected-(FMC HPC1A-DP1_M2C_P-PadA2)") (class "Default")
      (node (ref "FMC HPC1") (pin "A2") (pinfunction "DP1_M2C_P_A2") (pintype "passive+no_connect"))
    )
    (net (code "700") (name "unconnected-(FMC HPC1A-DP2_C2M_N-PadA27)") (class "Default")
      (node (ref "FMC HPC1") (pin "A27") (pinfunction "DP2_C2M_N_A27") (pintype "passive+no_connect"))
    )
    (net (code "701") (name "unconnected-(FMC HPC1A-DP2_C2M_P-PadA26)") (class "Default")
      (node (ref "FMC HPC1") (pin "A26") (pinfunction "DP2_C2M_P_A26") (pintype "passive+no_connect"))
    )
    (net (code "702") (name "unconnected-(FMC HPC1A-DP2_M2C_N-PadA7)") (class "Default")
      (node (ref "FMC HPC1") (pin "A7") (pinfunction "DP2_M2C_N_A7") (pintype "passive+no_connect"))
    )
    (net (code "703") (name "unconnected-(FMC HPC1A-DP2_M2C_P-PadA6)") (class "Default")
      (node (ref "FMC HPC1") (pin "A6") (pinfunction "DP2_M2C_P_A6") (pintype "passive+no_connect"))
    )
    (net (code "704") (name "unconnected-(FMC HPC1A-DP3_C2M_N-PadA31)") (class "Default")
      (node (ref "FMC HPC1") (pin "A31") (pinfunction "DP3_C2M_N_A31") (pintype "passive+no_connect"))
    )
    (net (code "705") (name "unconnected-(FMC HPC1A-DP3_C2M_P-PadA30)") (class "Default")
      (node (ref "FMC HPC1") (pin "A30") (pinfunction "DP3_C2M_P_A30") (pintype "passive+no_connect"))
    )
    (net (code "706") (name "unconnected-(FMC HPC1A-DP3_M2C_N-PadA11)") (class "Default")
      (node (ref "FMC HPC1") (pin "A11") (pinfunction "DP3_M2C_N_A11") (pintype "passive+no_connect"))
    )
    (net (code "707") (name "unconnected-(FMC HPC1A-DP3_M2C_P-PadA10)") (class "Default")
      (node (ref "FMC HPC1") (pin "A10") (pinfunction "DP3_M2C_P_A10") (pintype "passive+no_connect"))
    )
    (net (code "708") (name "unconnected-(FMC HPC1A-DP4_C2M_N-PadA35)") (class "Default")
      (node (ref "FMC HPC1") (pin "A35") (pinfunction "DP4_C2M_N_A35") (pintype "passive+no_connect"))
    )
    (net (code "709") (name "unconnected-(FMC HPC1A-DP4_C2M_P-PadA34)") (class "Default")
      (node (ref "FMC HPC1") (pin "A34") (pinfunction "DP4_C2M_P_A34") (pintype "passive+no_connect"))
    )
    (net (code "710") (name "unconnected-(FMC HPC1A-DP4_M2C_N-PadA15)") (class "Default")
      (node (ref "FMC HPC1") (pin "A15") (pinfunction "DP4_M2C_N_A15") (pintype "passive+no_connect"))
    )
    (net (code "711") (name "unconnected-(FMC HPC1A-DP4_M2C_P-PadA14)") (class "Default")
      (node (ref "FMC HPC1") (pin "A14") (pinfunction "DP4_M2C_P_A14") (pintype "passive+no_connect"))
    )
    (net (code "712") (name "unconnected-(FMC HPC1A-DP5_C2M_N-PadA39)") (class "Default")
      (node (ref "FMC HPC1") (pin "A39") (pinfunction "DP5_C2M_N_A39") (pintype "passive+no_connect"))
    )
    (net (code "713") (name "unconnected-(FMC HPC1A-DP5_C2M_P-PadA38)") (class "Default")
      (node (ref "FMC HPC1") (pin "A38") (pinfunction "DP5_C2M_P_A38") (pintype "passive+no_connect"))
    )
    (net (code "714") (name "unconnected-(FMC HPC1A-DP5_M2C_N-PadA19)") (class "Default")
      (node (ref "FMC HPC1") (pin "A19") (pinfunction "DP5_M2C_N_A19") (pintype "passive+no_connect"))
    )
    (net (code "715") (name "unconnected-(FMC HPC1A-DP5_M2C_P-PadA18)") (class "Default")
      (node (ref "FMC HPC1") (pin "A18") (pinfunction "DP5_M2C_P_A18") (pintype "passive+no_connect"))
    )
    (net (code "716") (name "unconnected-(FMC HPC1A-DP6_C2M_N-PadB37)") (class "Default")
      (node (ref "FMC HPC1") (pin "B37") (pinfunction "DP6_C2M_N_B37") (pintype "passive+no_connect"))
    )
    (net (code "717") (name "unconnected-(FMC HPC1A-DP6_C2M_P-PadB36)") (class "Default")
      (node (ref "FMC HPC1") (pin "B36") (pinfunction "DP6_C2M_P_B36") (pintype "passive+no_connect"))
    )
    (net (code "718") (name "unconnected-(FMC HPC1A-DP6_M2C_N-PadB17)") (class "Default")
      (node (ref "FMC HPC1") (pin "B17") (pinfunction "DP6_M2C_N_B17") (pintype "passive+no_connect"))
    )
    (net (code "719") (name "unconnected-(FMC HPC1A-DP6_M2C_P-PadB16)") (class "Default")
      (node (ref "FMC HPC1") (pin "B16") (pinfunction "DP6_M2C_P_B16") (pintype "passive+no_connect"))
    )
    (net (code "720") (name "unconnected-(FMC HPC1A-DP7_C2M_N-PadB33)") (class "Default")
      (node (ref "FMC HPC1") (pin "B33") (pinfunction "DP7_C2M_N_B33") (pintype "passive+no_connect"))
    )
    (net (code "721") (name "unconnected-(FMC HPC1A-DP7_C2M_P-PadB32)") (class "Default")
      (node (ref "FMC HPC1") (pin "B32") (pinfunction "DP7_C2M_P_B32") (pintype "passive+no_connect"))
    )
    (net (code "722") (name "unconnected-(FMC HPC1A-DP7_M2C_N-PadB13)") (class "Default")
      (node (ref "FMC HPC1") (pin "B13") (pinfunction "DP7_M2C_N_B13") (pintype "passive+no_connect"))
    )
    (net (code "723") (name "unconnected-(FMC HPC1A-DP7_M2C_P-PadB12)") (class "Default")
      (node (ref "FMC HPC1") (pin "B12") (pinfunction "DP7_M2C_P_B12") (pintype "passive+no_connect"))
    )
    (net (code "724") (name "unconnected-(FMC HPC1A-DP8_C2M_N-PadB29)") (class "Default")
      (node (ref "FMC HPC1") (pin "B29") (pinfunction "DP8_C2M_N_B29") (pintype "passive+no_connect"))
    )
    (net (code "725") (name "unconnected-(FMC HPC1A-DP8_C2M_P-PadB28)") (class "Default")
      (node (ref "FMC HPC1") (pin "B28") (pinfunction "DP8_C2M_P_B28") (pintype "passive+no_connect"))
    )
    (net (code "726") (name "unconnected-(FMC HPC1A-DP8_M2C_N-PadB9)") (class "Default")
      (node (ref "FMC HPC1") (pin "B9") (pinfunction "DP8_M2C_N_B9") (pintype "passive+no_connect"))
    )
    (net (code "727") (name "unconnected-(FMC HPC1A-DP8_M2C_P-PadB8)") (class "Default")
      (node (ref "FMC HPC1") (pin "B8") (pinfunction "DP8_M2C_P_B8") (pintype "passive+no_connect"))
    )
    (net (code "728") (name "unconnected-(FMC HPC1A-DP9_C2M_N-PadB25)") (class "Default")
      (node (ref "FMC HPC1") (pin "B25") (pinfunction "DP9_C2M_N_B25") (pintype "passive+no_connect"))
    )
    (net (code "729") (name "unconnected-(FMC HPC1A-DP9_C2M_P-PadB24)") (class "Default")
      (node (ref "FMC HPC1") (pin "B24") (pinfunction "DP9_C2M_P_B24") (pintype "passive+no_connect"))
    )
    (net (code "730") (name "unconnected-(FMC HPC1A-DP9_M2C_N-PadB5)") (class "Default")
      (node (ref "FMC HPC1") (pin "B5") (pinfunction "DP9_M2C_N_B5") (pintype "passive+no_connect"))
    )
    (net (code "731") (name "unconnected-(FMC HPC1A-DP9_M2C_P-PadB4)") (class "Default")
      (node (ref "FMC HPC1") (pin "B4") (pinfunction "DP9_M2C_P_B4") (pintype "passive+no_connect"))
    )
    (net (code "732") (name "unconnected-(FMC HPC1A-GBTCLK1_M2C_N-PadB21)") (class "Default")
      (node (ref "FMC HPC1") (pin "B21") (pinfunction "GBTCLK1_M2C_N_B21") (pintype "passive+no_connect"))
    )
    (net (code "733") (name "unconnected-(FMC HPC1A-GBTCLK1_M2C_P-PadB20)") (class "Default")
      (node (ref "FMC HPC1") (pin "B20") (pinfunction "GBTCLK1_M2C_P_B20") (pintype "passive+no_connect"))
    )
    (net (code "734") (name "unconnected-(FMC HPC1A-RES0-PadB40)") (class "Default")
      (node (ref "FMC HPC1") (pin "B40") (pinfunction "RES0_B40") (pintype "passive+no_connect"))
    )
    (net (code "735") (name "unconnected-(FMC HPC1B-3P3V-PadC39)") (class "Default")
      (node (ref "FMC HPC1") (pin "C39") (pinfunction "3P3V_C39") (pintype "passive+no_connect"))
    )
    (net (code "736") (name "unconnected-(FMC HPC1B-3P3V-PadD36)") (class "Default")
      (node (ref "FMC HPC1") (pin "D36") (pinfunction "3P3V_D36") (pintype "passive+no_connect"))
    )
    (net (code "737") (name "unconnected-(FMC HPC1B-3P3V-PadD38)") (class "Default")
      (node (ref "FMC HPC1") (pin "D38") (pinfunction "3P3V_D38") (pintype "passive+no_connect"))
    )
    (net (code "738") (name "unconnected-(FMC HPC1B-3P3V-PadD40)") (class "Default")
      (node (ref "FMC HPC1") (pin "D40") (pinfunction "3P3V_D40") (pintype "passive+no_connect"))
    )
    (net (code "739") (name "unconnected-(FMC HPC1B-3P3VAUX-PadD32)") (class "Default")
      (node (ref "FMC HPC1") (pin "D32") (pinfunction "3P3VAUX_D32") (pintype "passive+no_connect"))
    )
    (net (code "740") (name "unconnected-(FMC HPC1B-12P0V-PadC35)") (class "Default")
      (node (ref "FMC HPC1") (pin "C35") (pinfunction "12P0V_C35") (pintype "passive+no_connect"))
    )
    (net (code "741") (name "unconnected-(FMC HPC1B-12P0V-PadC37)") (class "Default")
      (node (ref "FMC HPC1") (pin "C37") (pinfunction "12P0V_C37") (pintype "passive+no_connect"))
    )
    (net (code "742") (name "unconnected-(FMC HPC1B-DP0_C2M_N-PadC3)") (class "Default")
      (node (ref "FMC HPC1") (pin "C3") (pinfunction "DP0_C2M_N_C3") (pintype "passive+no_connect"))
    )
    (net (code "743") (name "unconnected-(FMC HPC1B-DP0_C2M_P-PadC2)") (class "Default")
      (node (ref "FMC HPC1") (pin "C2") (pinfunction "DP0_C2M_P_C2") (pintype "passive+no_connect"))
    )
    (net (code "744") (name "unconnected-(FMC HPC1B-DP0_M2C_N-PadC7)") (class "Default")
      (node (ref "FMC HPC1") (pin "C7") (pinfunction "DP0_M2C_N_C7") (pintype "passive+no_connect"))
    )
    (net (code "745") (name "unconnected-(FMC HPC1B-DP0_M2C_P-PadC6)") (class "Default")
      (node (ref "FMC HPC1") (pin "C6") (pinfunction "DP0_M2C_P_C6") (pintype "passive+no_connect"))
    )
    (net (code "746") (name "unconnected-(FMC HPC1B-GA0-PadC34)") (class "Default")
      (node (ref "FMC HPC1") (pin "C34") (pinfunction "GA0_C34") (pintype "passive+no_connect"))
    )
    (net (code "747") (name "unconnected-(FMC HPC1B-GA1-PadD35)") (class "Default")
      (node (ref "FMC HPC1") (pin "D35") (pinfunction "GA1_D35") (pintype "passive+no_connect"))
    )
    (net (code "748") (name "unconnected-(FMC HPC1B-GBT_CLK0_M2C_N-PadD5)") (class "Default")
      (node (ref "FMC HPC1") (pin "D5") (pinfunction "GBT_CLK0_M2C_N_D5") (pintype "passive+no_connect"))
    )
    (net (code "749") (name "unconnected-(FMC HPC1B-GBT_CLK0_M2C_P-PadD4)") (class "Default")
      (node (ref "FMC HPC1") (pin "D4") (pinfunction "GBT_CLK0_M2C_P_D4") (pintype "passive+no_connect"))
    )
    (net (code "750") (name "unconnected-(FMC HPC1B-PG_C2M-PadD1)") (class "Default")
      (node (ref "FMC HPC1") (pin "D1") (pinfunction "PG_C2M_D1") (pintype "passive+no_connect"))
    )
    (net (code "751") (name "unconnected-(FMC HPC1B-SCL-PadC30)") (class "Default")
      (node (ref "FMC HPC1") (pin "C30") (pinfunction "SCL_C30") (pintype "passive+no_connect"))
    )
    (net (code "752") (name "unconnected-(FMC HPC1B-SDA-PadC31)") (class "Default")
      (node (ref "FMC HPC1") (pin "C31") (pinfunction "SDA_C31") (pintype "passive+no_connect"))
    )
    (net (code "753") (name "unconnected-(FMC HPC1B-TCK-PadD29)") (class "Default")
      (node (ref "FMC HPC1") (pin "D29") (pinfunction "TCK_D29") (pintype "passive+no_connect"))
    )
    (net (code "754") (name "unconnected-(FMC HPC1B-TDI-PadD30)") (class "Default")
      (node (ref "FMC HPC1") (pin "D30") (pinfunction "TDI_D30") (pintype "passive+no_connect"))
    )
    (net (code "755") (name "unconnected-(FMC HPC1B-TDO-PadD31)") (class "Default")
      (node (ref "FMC HPC1") (pin "D31") (pinfunction "TDO_D31") (pintype "passive+no_connect"))
    )
    (net (code "756") (name "unconnected-(FMC HPC1B-TMS-PadD33)") (class "Default")
      (node (ref "FMC HPC1") (pin "D33") (pinfunction "TMS_D33") (pintype "passive+no_connect"))
    )
    (net (code "757") (name "unconnected-(FMC HPC1B-TRST_L-PadD34)") (class "Default")
      (node (ref "FMC HPC1") (pin "D34") (pinfunction "TRST_L_D34") (pintype "passive+no_connect"))
    )
    (net (code "758") (name "unconnected-(FMC HPC1C-HB02_N-PadF23)") (class "Default")
      (node (ref "FMC HPC1") (pin "F23") (pinfunction "HB02_N_F23") (pintype "passive+no_connect"))
    )
    (net (code "759") (name "unconnected-(FMC HPC1C-HB02_P-PadF22)") (class "Default")
      (node (ref "FMC HPC1") (pin "F22") (pinfunction "HB02_P_F22") (pintype "passive+no_connect"))
    )
    (net (code "760") (name "unconnected-(FMC HPC1C-HB03_N-PadE22)") (class "Default")
      (node (ref "FMC HPC1") (pin "E22") (pinfunction "HB03_N_E22") (pintype "passive+no_connect"))
    )
    (net (code "761") (name "unconnected-(FMC HPC1C-HB03_P-PadE21)") (class "Default")
      (node (ref "FMC HPC1") (pin "E21") (pinfunction "HB03_P_E21") (pintype "passive+no_connect"))
    )
    (net (code "762") (name "unconnected-(FMC HPC1C-HB04_N-PadF26)") (class "Default")
      (node (ref "FMC HPC1") (pin "F26") (pinfunction "HB04_N_F26") (pintype "passive+no_connect"))
    )
    (net (code "763") (name "unconnected-(FMC HPC1C-HB04_P-PadF25)") (class "Default")
      (node (ref "FMC HPC1") (pin "F25") (pinfunction "HB04_P_F25") (pintype "passive+no_connect"))
    )
    (net (code "764") (name "unconnected-(FMC HPC1C-HB05_N-PadE25)") (class "Default")
      (node (ref "FMC HPC1") (pin "E25") (pinfunction "HB05_N_E25") (pintype "passive+no_connect"))
    )
    (net (code "765") (name "unconnected-(FMC HPC1C-HB05_P-PadE24)") (class "Default")
      (node (ref "FMC HPC1") (pin "E24") (pinfunction "HB05_P_E24") (pintype "passive+no_connect"))
    )
    (net (code "766") (name "unconnected-(FMC HPC1C-HB08_N-PadF29)") (class "Default")
      (node (ref "FMC HPC1") (pin "F29") (pinfunction "HB08_N_F29") (pintype "passive+no_connect"))
    )
    (net (code "767") (name "unconnected-(FMC HPC1C-HB08_P-PadF28)") (class "Default")
      (node (ref "FMC HPC1") (pin "F28") (pinfunction "HB08_P_F28") (pintype "passive+no_connect"))
    )
    (net (code "768") (name "unconnected-(FMC HPC1C-HB09_N-PadE28)") (class "Default")
      (node (ref "FMC HPC1") (pin "E28") (pinfunction "HB09_N_E28") (pintype "passive+no_connect"))
    )
    (net (code "769") (name "unconnected-(FMC HPC1C-HB09_P-PadE27)") (class "Default")
      (node (ref "FMC HPC1") (pin "E27") (pinfunction "HB09_P_E27") (pintype "passive+no_connect"))
    )
    (net (code "770") (name "unconnected-(FMC HPC1C-HB12_N-PadF32)") (class "Default")
      (node (ref "FMC HPC1") (pin "F32") (pinfunction "HB12_N_F32") (pintype "passive+no_connect"))
    )
    (net (code "771") (name "unconnected-(FMC HPC1C-HB12_P-PadF31)") (class "Default")
      (node (ref "FMC HPC1") (pin "F31") (pinfunction "HB12_P_F31") (pintype "passive+no_connect"))
    )
    (net (code "772") (name "unconnected-(FMC HPC1C-HB13_N-PadE31)") (class "Default")
      (node (ref "FMC HPC1") (pin "E31") (pinfunction "HB13_N_E31") (pintype "passive+no_connect"))
    )
    (net (code "773") (name "unconnected-(FMC HPC1C-HB13_P-PadE30)") (class "Default")
      (node (ref "FMC HPC1") (pin "E30") (pinfunction "HB13_P_E30") (pintype "passive+no_connect"))
    )
    (net (code "774") (name "unconnected-(FMC HPC1C-HB16_N-PadF35)") (class "Default")
      (node (ref "FMC HPC1") (pin "F35") (pinfunction "HB16_N_F35") (pintype "passive+no_connect"))
    )
    (net (code "775") (name "unconnected-(FMC HPC1C-HB16_P-PadF34)") (class "Default")
      (node (ref "FMC HPC1") (pin "F34") (pinfunction "HB16_P_F34") (pintype "passive+no_connect"))
    )
    (net (code "776") (name "unconnected-(FMC HPC1C-HB19_N-PadE34)") (class "Default")
      (node (ref "FMC HPC1") (pin "E34") (pinfunction "HB19_N_E34") (pintype "passive+no_connect"))
    )
    (net (code "777") (name "unconnected-(FMC HPC1C-HB19_P-PadE33)") (class "Default")
      (node (ref "FMC HPC1") (pin "E33") (pinfunction "HB19_P_E33") (pintype "passive+no_connect"))
    )
    (net (code "778") (name "unconnected-(FMC HPC1C-HB20_N-PadF38)") (class "Default")
      (node (ref "FMC HPC1") (pin "F38") (pinfunction "HB20_N_F38") (pintype "passive+no_connect"))
    )
    (net (code "779") (name "unconnected-(FMC HPC1C-HB20_P-PadF37)") (class "Default")
      (node (ref "FMC HPC1") (pin "F37") (pinfunction "HB20_P_F37") (pintype "passive+no_connect"))
    )
    (net (code "780") (name "unconnected-(FMC HPC1C-HB21_N-PadE37)") (class "Default")
      (node (ref "FMC HPC1") (pin "E37") (pinfunction "HB21_N_E37") (pintype "passive+no_connect"))
    )
    (net (code "781") (name "unconnected-(FMC HPC1C-HB21_P-PadE36)") (class "Default")
      (node (ref "FMC HPC1") (pin "E36") (pinfunction "HB21_P_E36") (pintype "passive+no_connect"))
    )
    (net (code "782") (name "unconnected-(FMC HPC1C-PG_M2C-PadF1)") (class "Default")
      (node (ref "FMC HPC1") (pin "F1") (pinfunction "PG_M2C_F1") (pintype "passive+no_connect"))
    )
    (net (code "783") (name "unconnected-(FMC HPC1C-VADJ-PadE39)") (class "Default")
      (node (ref "FMC HPC1") (pin "E39") (pinfunction "VADJ_E39") (pintype "passive+no_connect"))
    )
    (net (code "784") (name "unconnected-(FMC HPC1C-VADJ-PadF40)") (class "Default")
      (node (ref "FMC HPC1") (pin "F40") (pinfunction "VADJ_F40") (pintype "passive+no_connect"))
    )
    (net (code "785") (name "unconnected-(FMC HPC1D-CLK0_M2C_N-PadH5)") (class "Default")
      (node (ref "FMC HPC1") (pin "H5") (pinfunction "CLK0_M2C_N_H5") (pintype "passive+no_connect"))
    )
    (net (code "786") (name "unconnected-(FMC HPC1D-CLK0_M2C_P-PadH4)") (class "Default")
      (node (ref "FMC HPC1") (pin "H4") (pinfunction "CLK0_M2C_P_H4") (pintype "passive+no_connect"))
    )
    (net (code "787") (name "unconnected-(FMC HPC1D-CLK1_M2C_N-PadG3)") (class "Default")
      (node (ref "FMC HPC1") (pin "G3") (pinfunction "CLK1_M2C_N_G3") (pintype "passive+no_connect"))
    )
    (net (code "788") (name "unconnected-(FMC HPC1D-CLK1_M2C_P-PadG2)") (class "Default")
      (node (ref "FMC HPC1") (pin "G2") (pinfunction "CLK1_M2C_P_G2") (pintype "passive+no_connect"))
    )
    (net (code "789") (name "unconnected-(FMC HPC1D-PRSNT_M2C_L-PadH2)") (class "Default")
      (node (ref "FMC HPC1") (pin "H2") (pinfunction "PRSNT_M2C_L_H2") (pintype "passive+no_connect"))
    )
    (net (code "790") (name "unconnected-(FMC HPC1D-VADJ-PadG39)") (class "Default")
      (node (ref "FMC HPC1") (pin "G39") (pinfunction "VADJ_G39") (pintype "passive+no_connect"))
    )
    (net (code "791") (name "unconnected-(FMC HPC1D-VADJ-PadH40)") (class "Default")
      (node (ref "FMC HPC1") (pin "H40") (pinfunction "VADJ_H40") (pintype "passive+no_connect"))
    )
    (net (code "792") (name "unconnected-(FMC HPC1D-VREF_A_M2C-PadH1)") (class "Default")
      (node (ref "FMC HPC1") (pin "H1") (pinfunction "VREF_A_M2C_H1") (pintype "passive+no_connect"))
    )
    (net (code "793") (name "unconnected-(FMC HPC1E-CLK2_BIDIR_N-PadK5)") (class "Default")
      (node (ref "FMC HPC1") (pin "K5") (pinfunction "CLK2_BIDIR_N_K5") (pintype "passive+no_connect"))
    )
    (net (code "794") (name "unconnected-(FMC HPC1E-CLK2_BIDIR_P-PadK4)") (class "Default")
      (node (ref "FMC HPC1") (pin "K4") (pinfunction "CLK2_BIDIR_P_K4") (pintype "passive+no_connect"))
    )
    (net (code "795") (name "unconnected-(FMC HPC1E-CLK3_BIDIR_N-PadJ3)") (class "Default")
      (node (ref "FMC HPC1") (pin "J3") (pinfunction "CLK3_BIDIR_N_J3") (pintype "passive+no_connect"))
    )
    (net (code "796") (name "unconnected-(FMC HPC1E-CLK3_BIDIR_P-PadJ2)") (class "Default")
      (node (ref "FMC HPC1") (pin "J2") (pinfunction "CLK3_BIDIR_P_J2") (pintype "passive+no_connect"))
    )
    (net (code "797") (name "unconnected-(FMC HPC1E-HB00_N_CC-PadK26)") (class "Default")
      (node (ref "FMC HPC1") (pin "K26") (pinfunction "HB00_N_CC_K26") (pintype "passive+no_connect"))
    )
    (net (code "798") (name "unconnected-(FMC HPC1E-HB00_P_CC-PadK25)") (class "Default")
      (node (ref "FMC HPC1") (pin "K25") (pinfunction "HB00_P_CC_K25") (pintype "passive+no_connect"))
    )
    (net (code "799") (name "unconnected-(FMC HPC1E-HB01_N-PadJ25)") (class "Default")
      (node (ref "FMC HPC1") (pin "J25") (pinfunction "HB01_N_J25") (pintype "passive+no_connect"))
    )
    (net (code "800") (name "unconnected-(FMC HPC1E-HB01_P-PadJ24)") (class "Default")
      (node (ref "FMC HPC1") (pin "J24") (pinfunction "HB01_P_J24") (pintype "passive+no_connect"))
    )
    (net (code "801") (name "unconnected-(FMC HPC1E-HB06_N_CC-PadK29)") (class "Default")
      (node (ref "FMC HPC1") (pin "K29") (pinfunction "HB06_N_CC_K29") (pintype "passive+no_connect"))
    )
    (net (code "802") (name "unconnected-(FMC HPC1E-HB06_P_CC-PadK28)") (class "Default")
      (node (ref "FMC HPC1") (pin "K28") (pinfunction "HB06_P_CC_K28") (pintype "passive+no_connect"))
    )
    (net (code "803") (name "unconnected-(FMC HPC1E-HB07_N-PadJ28)") (class "Default")
      (node (ref "FMC HPC1") (pin "J28") (pinfunction "HB07_N_J28") (pintype "passive+no_connect"))
    )
    (net (code "804") (name "unconnected-(FMC HPC1E-HB07_P-PadJ27)") (class "Default")
      (node (ref "FMC HPC1") (pin "J27") (pinfunction "HB07_P_J27") (pintype "passive+no_connect"))
    )
    (net (code "805") (name "unconnected-(FMC HPC1E-HB10_N-PadK32)") (class "Default")
      (node (ref "FMC HPC1") (pin "K32") (pinfunction "HB10_N_K32") (pintype "passive+no_connect"))
    )
    (net (code "806") (name "unconnected-(FMC HPC1E-HB10_P-PadK31)") (class "Default")
      (node (ref "FMC HPC1") (pin "K31") (pinfunction "HB10_P_K31") (pintype "passive+no_connect"))
    )
    (net (code "807") (name "unconnected-(FMC HPC1E-HB11_N-PadJ31)") (class "Default")
      (node (ref "FMC HPC1") (pin "J31") (pinfunction "HB11_N_J31") (pintype "passive+no_connect"))
    )
    (net (code "808") (name "unconnected-(FMC HPC1E-HB11_P-PadJ30)") (class "Default")
      (node (ref "FMC HPC1") (pin "J30") (pinfunction "HB11_P_J30") (pintype "passive+no_connect"))
    )
    (net (code "809") (name "unconnected-(FMC HPC1E-HB14_N-PadK35)") (class "Default")
      (node (ref "FMC HPC1") (pin "K35") (pinfunction "HB14_N_K35") (pintype "passive+no_connect"))
    )
    (net (code "810") (name "unconnected-(FMC HPC1E-HB14_P-PadK34)") (class "Default")
      (node (ref "FMC HPC1") (pin "K34") (pinfunction "HB14_P_K34") (pintype "passive+no_connect"))
    )
    (net (code "811") (name "unconnected-(FMC HPC1E-HB15_N-PadJ34)") (class "Default")
      (node (ref "FMC HPC1") (pin "J34") (pinfunction "HB15_N_J34") (pintype "passive+no_connect"))
    )
    (net (code "812") (name "unconnected-(FMC HPC1E-HB15_P-PadJ33)") (class "Default")
      (node (ref "FMC HPC1") (pin "J33") (pinfunction "HB15_P_J33") (pintype "passive+no_connect"))
    )
    (net (code "813") (name "unconnected-(FMC HPC1E-HB17_N_CC-PadK38)") (class "Default")
      (node (ref "FMC HPC1") (pin "K38") (pinfunction "HB17_N_CC_K38") (pintype "passive+no_connect"))
    )
    (net (code "814") (name "unconnected-(FMC HPC1E-HB17_P_CC-PadK37)") (class "Default")
      (node (ref "FMC HPC1") (pin "K37") (pinfunction "HB17_P_CC_K37") (pintype "passive+no_connect"))
    )
    (net (code "815") (name "unconnected-(FMC HPC1E-HB18_N-PadJ37)") (class "Default")
      (node (ref "FMC HPC1") (pin "J37") (pinfunction "HB18_N_J37") (pintype "passive+no_connect"))
    )
    (net (code "816") (name "unconnected-(FMC HPC1E-HB18_P-PadJ36)") (class "Default")
      (node (ref "FMC HPC1") (pin "J36") (pinfunction "HB18_P_J36") (pintype "passive+no_connect"))
    )
    (net (code "817") (name "unconnected-(FMC HPC1E-VIO_B_M2C-PadJ39)") (class "Default")
      (node (ref "FMC HPC1") (pin "J39") (pinfunction "VIO_B_M2C_J39") (pintype "passive+no_connect"))
    )
    (net (code "818") (name "unconnected-(FMC HPC1E-VIO_B_M2C-PadK40)") (class "Default")
      (node (ref "FMC HPC1") (pin "K40") (pinfunction "VIO_B_M2C_K40") (pintype "passive+no_connect"))
    )
    (net (code "819") (name "unconnected-(FMC HPC1E-VREF_B_M2C-PadK1)") (class "Default")
      (node (ref "FMC HPC1") (pin "K1") (pinfunction "VREF_B_M2C_K1") (pintype "passive+no_connect"))
    )
    (net (code "820") (name "unconnected-(ICXTRAP1-PadAD30)") (class "Default")
      (node (ref "ICXTRAP1") (pin "AD30") (pintype "passive+no_connect"))
    )
    (net (code "821") (name "unconnected-(ICXTRAP1-PadAE5)") (class "Default")
      (node (ref "ICXTRAP1") (pin "AE5") (pintype "passive+no_connect"))
    )
    (net (code "822") (name "unconnected-(ICXTRAP1-PadAE7)") (class "Default")
      (node (ref "ICXTRAP1") (pin "AE7") (pintype "passive+no_connect"))
    )
    (net (code "823") (name "unconnected-(ICXTRAP1-PadAE29)") (class "Default")
      (node (ref "ICXTRAP1") (pin "AE29") (pintype "passive+no_connect"))
    )
    (net (code "824") (name "unconnected-(ICXTRAP1-PadAE31)") (class "Default")
      (node (ref "ICXTRAP1") (pin "AE31") (pintype "passive"))
    )
    (net (code "825") (name "unconnected-(ICXTRAP1-PadAF4)") (class "Default")
      (node (ref "ICXTRAP1") (pin "AF4") (pintype "passive+no_connect"))
    )
    (net (code "826") (name "unconnected-(ICXTRAP1-PadAF6)") (class "Default")
      (node (ref "ICXTRAP1") (pin "AF6") (pintype "passive+no_connect"))
    )
    (net (code "827") (name "unconnected-(ICXTRAP1-PadAF30)") (class "Default")
      (node (ref "ICXTRAP1") (pin "AF30") (pintype "passive+no_connect"))
    )
    (net (code "828") (name "unconnected-(ICXTRAP1-PadAF32)") (class "Default")
      (node (ref "ICXTRAP1") (pin "AF32") (pintype "passive+no_connect"))
    )
    (net (code "829") (name "unconnected-(ICXTRAP1-PadAG5)") (class "Default")
      (node (ref "ICXTRAP1") (pin "AG5") (pintype "passive+no_connect"))
    )
    (net (code "830") (name "unconnected-(ICXTRAP1-PadAG7)") (class "Default")
      (node (ref "ICXTRAP1") (pin "AG7") (pintype "passive+no_connect"))
    )
    (net (code "831") (name "unconnected-(ICXTRAP1-PadAG29)") (class "Default")
      (node (ref "ICXTRAP1") (pin "AG29") (pintype "passive+no_connect"))
    )
    (net (code "832") (name "unconnected-(ICXTRAP1-PadAG31)") (class "Default")
      (node (ref "ICXTRAP1") (pin "AG31") (pintype "passive+no_connect"))
    )
    (net (code "833") (name "unconnected-(ICXTRAP1-PadAH4)") (class "Default")
      (node (ref "ICXTRAP1") (pin "AH4") (pintype "passive+no_connect"))
    )
    (net (code "834") (name "unconnected-(ICXTRAP1-PadAH6)") (class "Default")
      (node (ref "ICXTRAP1") (pin "AH6") (pintype "passive+no_connect"))
    )
    (net (code "835") (name "unconnected-(ICXTRAP1-PadAH30)") (class "Default")
      (node (ref "ICXTRAP1") (pin "AH30") (pintype "passive+no_connect"))
    )
    (net (code "836") (name "unconnected-(ICXTRAP1-PadAH32)") (class "Default")
      (node (ref "ICXTRAP1") (pin "AH32") (pintype "passive"))
    )
    (net (code "837") (name "unconnected-(ICXTRAP1-PadAJ5)") (class "Default")
      (node (ref "ICXTRAP1") (pin "AJ5") (pintype "passive+no_connect"))
    )
    (net (code "838") (name "unconnected-(ICXTRAP1-PadAJ9)") (class "Default")
      (node (ref "ICXTRAP1") (pin "AJ9") (pintype "passive+no_connect"))
    )
    (net (code "839") (name "unconnected-(ICXTRAP1-PadAJ11)") (class "Default")
      (node (ref "ICXTRAP1") (pin "AJ11") (pintype "passive+no_connect"))
    )
    (net (code "840") (name "unconnected-(ICXTRAP1-PadAJ25)") (class "Default")
      (node (ref "ICXTRAP1") (pin "AJ25") (pintype "passive+no_connect"))
    )
    (net (code "841") (name "unconnected-(ICXTRAP1-PadAJ27)") (class "Default")
      (node (ref "ICXTRAP1") (pin "AJ27") (pintype "passive+no_connect"))
    )
    (net (code "842") (name "unconnected-(ICXTRAP1-PadAJ31)") (class "Default")
      (node (ref "ICXTRAP1") (pin "AJ31") (pintype "passive+no_connect"))
    )
    (net (code "843") (name "unconnected-(ICXTRAP1-PadAK4)") (class "Default")
      (node (ref "ICXTRAP1") (pin "AK4") (pintype "passive+no_connect"))
    )
    (net (code "844") (name "unconnected-(ICXTRAP1-PadAK8)") (class "Default")
      (node (ref "ICXTRAP1") (pin "AK8") (pintype "passive+no_connect"))
    )
    (net (code "845") (name "unconnected-(ICXTRAP1-PadAK10)") (class "Default")
      (node (ref "ICXTRAP1") (pin "AK10") (pintype "passive+no_connect"))
    )
    (net (code "846") (name "unconnected-(ICXTRAP1-PadAK26)") (class "Default")
      (node (ref "ICXTRAP1") (pin "AK26") (pintype "passive+no_connect"))
    )
    (net (code "847") (name "unconnected-(ICXTRAP1-PadAK28)") (class "Default")
      (node (ref "ICXTRAP1") (pin "AK28") (pintype "passive+no_connect"))
    )
    (net (code "848") (name "unconnected-(ICXTRAP1-PadAK32)") (class "Default")
      (node (ref "ICXTRAP1") (pin "AK32") (pintype "passive"))
    )
    (net (code "849") (name "unconnected-(ICXTRAP1-PadAL5)") (class "Default")
      (node (ref "ICXTRAP1") (pin "AL5") (pintype "passive+no_connect"))
    )
    (net (code "850") (name "unconnected-(ICXTRAP1-PadAL7)") (class "Default")
      (node (ref "ICXTRAP1") (pin "AL7") (pintype "passive+no_connect"))
    )
    (net (code "851") (name "unconnected-(ICXTRAP1-PadAL9)") (class "Default")
      (node (ref "ICXTRAP1") (pin "AL9") (pintype "passive+no_connect"))
    )
    (net (code "852") (name "unconnected-(ICXTRAP1-PadAL11)") (class "Default")
      (node (ref "ICXTRAP1") (pin "AL11") (pintype "passive+no_connect"))
    )
    (net (code "853") (name "unconnected-(ICXTRAP1-PadAL25)") (class "Default")
      (node (ref "ICXTRAP1") (pin "AL25") (pintype "passive+no_connect"))
    )
    (net (code "854") (name "unconnected-(ICXTRAP1-PadAL27)") (class "Default")
      (node (ref "ICXTRAP1") (pin "AL27") (pintype "passive+no_connect"))
    )
    (net (code "855") (name "unconnected-(ICXTRAP1-PadAL29)") (class "Default")
      (node (ref "ICXTRAP1") (pin "AL29") (pintype "passive+no_connect"))
    )
    (net (code "856") (name "unconnected-(ICXTRAP1-PadAL31)") (class "Default")
      (node (ref "ICXTRAP1") (pin "AL31") (pintype "passive+no_connect"))
    )
    (net (code "857") (name "unconnected-(ICXTRAP1-PadAM4)") (class "Default")
      (node (ref "ICXTRAP1") (pin "AM4") (pintype "passive+no_connect"))
    )
    (net (code "858") (name "unconnected-(ICXTRAP1-PadAM6)") (class "Default")
      (node (ref "ICXTRAP1") (pin "AM6") (pintype "passive+no_connect"))
    )
    (net (code "859") (name "unconnected-(ICXTRAP1-PadAM8)") (class "Default")
      (node (ref "ICXTRAP1") (pin "AM8") (pintype "passive+no_connect"))
    )
    (net (code "860") (name "unconnected-(ICXTRAP1-PadAM10)") (class "Default")
      (node (ref "ICXTRAP1") (pin "AM10") (pintype "passive+no_connect"))
    )
    (net (code "861") (name "unconnected-(ICXTRAP1-PadAM26)") (class "Default")
      (node (ref "ICXTRAP1") (pin "AM26") (pintype "passive+no_connect"))
    )
    (net (code "862") (name "unconnected-(ICXTRAP1-PadAM28)") (class "Default")
      (node (ref "ICXTRAP1") (pin "AM28") (pintype "passive+no_connect"))
    )
    (net (code "863") (name "unconnected-(ICXTRAP1-PadAM30)") (class "Default")
      (node (ref "ICXTRAP1") (pin "AM30") (pintype "passive+no_connect"))
    )
    (net (code "864") (name "unconnected-(ICXTRAP1-PadAM32)") (class "Default")
      (node (ref "ICXTRAP1") (pin "AM32") (pintype "passive+no_connect"))
    )
    (net (code "865") (name "unconnected-(ICXTRAP1-PadD4)") (class "Default")
      (node (ref "ICXTRAP1") (pin "D4") (pintype "passive+no_connect"))
    )
    (net (code "866") (name "unconnected-(ICXTRAP1-PadD6)") (class "Default")
      (node (ref "ICXTRAP1") (pin "D6") (pintype "passive"))
    )
    (net (code "867") (name "unconnected-(ICXTRAP1-PadD8)") (class "Default")
      (node (ref "ICXTRAP1") (pin "D8") (pintype "passive+no_connect"))
    )
    (net (code "868") (name "unconnected-(ICXTRAP1-PadD10)") (class "Default")
      (node (ref "ICXTRAP1") (pin "D10") (pintype "passive+no_connect"))
    )
    (net (code "869") (name "unconnected-(ICXTRAP1-PadD26)") (class "Default")
      (node (ref "ICXTRAP1") (pin "D26") (pintype "passive+no_connect"))
    )
    (net (code "870") (name "unconnected-(ICXTRAP1-PadD28)") (class "Default")
      (node (ref "ICXTRAP1") (pin "D28") (pintype "passive+no_connect"))
    )
    (net (code "871") (name "unconnected-(ICXTRAP1-PadD30)") (class "Default")
      (node (ref "ICXTRAP1") (pin "D30") (pintype "passive+no_connect"))
    )
    (net (code "872") (name "unconnected-(ICXTRAP1-PadD32)") (class "Default")
      (node (ref "ICXTRAP1") (pin "D32") (pintype "passive+no_connect"))
    )
    (net (code "873") (name "unconnected-(ICXTRAP1-PadE5)") (class "Default")
      (node (ref "ICXTRAP1") (pin "E5") (pintype "passive+no_connect"))
    )
    (net (code "874") (name "unconnected-(ICXTRAP1-PadE7)") (class "Default")
      (node (ref "ICXTRAP1") (pin "E7") (pintype "passive+no_connect"))
    )
    (net (code "875") (name "unconnected-(ICXTRAP1-PadE9)") (class "Default")
      (node (ref "ICXTRAP1") (pin "E9") (pintype "passive+no_connect"))
    )
    (net (code "876") (name "unconnected-(ICXTRAP1-PadE11)") (class "Default")
      (node (ref "ICXTRAP1") (pin "E11") (pintype "passive+no_connect"))
    )
    (net (code "877") (name "unconnected-(ICXTRAP1-PadE25)") (class "Default")
      (node (ref "ICXTRAP1") (pin "E25") (pintype "passive+no_connect"))
    )
    (net (code "878") (name "unconnected-(ICXTRAP1-PadE27)") (class "Default")
      (node (ref "ICXTRAP1") (pin "E27") (pintype "passive+no_connect"))
    )
    (net (code "879") (name "unconnected-(ICXTRAP1-PadE29)") (class "Default")
      (node (ref "ICXTRAP1") (pin "E29") (pintype "passive+no_connect"))
    )
    (net (code "880") (name "unconnected-(ICXTRAP1-PadE31)") (class "Default")
      (node (ref "ICXTRAP1") (pin "E31") (pintype "passive+no_connect"))
    )
    (net (code "881") (name "unconnected-(ICXTRAP1-PadF4)") (class "Default")
      (node (ref "ICXTRAP1") (pin "F4") (pintype "passive+no_connect"))
    )
    (net (code "882") (name "unconnected-(ICXTRAP1-PadF8)") (class "Default")
      (node (ref "ICXTRAP1") (pin "F8") (pintype "passive+no_connect"))
    )
    (net (code "883") (name "unconnected-(ICXTRAP1-PadF10)") (class "Default")
      (node (ref "ICXTRAP1") (pin "F10") (pintype "passive+no_connect"))
    )
    (net (code "884") (name "unconnected-(ICXTRAP1-PadF26)") (class "Default")
      (node (ref "ICXTRAP1") (pin "F26") (pintype "passive+no_connect"))
    )
    (net (code "885") (name "unconnected-(ICXTRAP1-PadF28)") (class "Default")
      (node (ref "ICXTRAP1") (pin "F28") (pintype "passive+no_connect"))
    )
    (net (code "886") (name "unconnected-(ICXTRAP1-PadF32)") (class "Default")
      (node (ref "ICXTRAP1") (pin "F32") (pintype "passive+no_connect"))
    )
    (net (code "887") (name "unconnected-(ICXTRAP1-PadG5)") (class "Default")
      (node (ref "ICXTRAP1") (pin "G5") (pintype "passive+no_connect"))
    )
    (net (code "888") (name "unconnected-(ICXTRAP1-PadG9)") (class "Default")
      (node (ref "ICXTRAP1") (pin "G9") (pintype "passive+no_connect"))
    )
    (net (code "889") (name "unconnected-(ICXTRAP1-PadG11)") (class "Default")
      (node (ref "ICXTRAP1") (pin "G11") (pintype "passive+no_connect"))
    )
    (net (code "890") (name "unconnected-(ICXTRAP1-PadG25)") (class "Default")
      (node (ref "ICXTRAP1") (pin "G25") (pintype "passive+no_connect"))
    )
    (net (code "891") (name "unconnected-(ICXTRAP1-PadG27)") (class "Default")
      (node (ref "ICXTRAP1") (pin "G27") (pintype "passive+no_connect"))
    )
    (net (code "892") (name "unconnected-(ICXTRAP1-PadG31)") (class "Default")
      (node (ref "ICXTRAP1") (pin "G31") (pintype "passive+no_connect"))
    )
    (net (code "893") (name "unconnected-(ICXTRAP1-PadH4)") (class "Default")
      (node (ref "ICXTRAP1") (pin "H4") (pintype "passive+no_connect"))
    )
    (net (code "894") (name "unconnected-(ICXTRAP1-PadH6)") (class "Default")
      (node (ref "ICXTRAP1") (pin "H6") (pintype "passive"))
    )
    (net (code "895") (name "unconnected-(ICXTRAP1-PadH30)") (class "Default")
      (node (ref "ICXTRAP1") (pin "H30") (pintype "passive+no_connect"))
    )
    (net (code "896") (name "unconnected-(ICXTRAP1-PadH32)") (class "Default")
      (node (ref "ICXTRAP1") (pin "H32") (pintype "passive+no_connect"))
    )
    (net (code "897") (name "unconnected-(ICXTRAP1-PadJ5)") (class "Default")
      (node (ref "ICXTRAP1") (pin "J5") (pintype "passive+no_connect"))
    )
    (net (code "898") (name "unconnected-(ICXTRAP1-PadJ7)") (class "Default")
      (node (ref "ICXTRAP1") (pin "J7") (pintype "passive"))
    )
    (net (code "899") (name "unconnected-(ICXTRAP1-PadJ29)") (class "Default")
      (node (ref "ICXTRAP1") (pin "J29") (pintype "passive+no_connect"))
    )
    (net (code "900") (name "unconnected-(ICXTRAP1-PadJ31)") (class "Default")
      (node (ref "ICXTRAP1") (pin "J31") (pintype "passive+no_connect"))
    )
    (net (code "901") (name "unconnected-(ICXTRAP1-PadK4)") (class "Default")
      (node (ref "ICXTRAP1") (pin "K4") (pintype "passive+no_connect"))
    )
    (net (code "902") (name "unconnected-(ICXTRAP1-PadK6)") (class "Default")
      (node (ref "ICXTRAP1") (pin "K6") (pintype "passive+no_connect"))
    )
    (net (code "903") (name "unconnected-(ICXTRAP1-PadK30)") (class "Default")
      (node (ref "ICXTRAP1") (pin "K30") (pintype "passive+no_connect"))
    )
    (net (code "904") (name "unconnected-(ICXTRAP1-PadK32)") (class "Default")
      (node (ref "ICXTRAP1") (pin "K32") (pintype "passive"))
    )
    (net (code "905") (name "unconnected-(ICXTRAP1-PadL5)") (class "Default")
      (node (ref "ICXTRAP1") (pin "L5") (pintype "passive+no_connect"))
    )
    (net (code "906") (name "unconnected-(ICXTRAP1-PadL7)") (class "Default")
      (node (ref "ICXTRAP1") (pin "L7") (pintype "passive+no_connect"))
    )
    (net (code "907") (name "unconnected-(ICXTRAP1-PadL29)") (class "Default")
      (node (ref "ICXTRAP1") (pin "L29") (pintype "passive"))
    )
  )
)
